# PX4FMUv2_4_6.net
KiCad netlist of a schematic drawn in EAGLE
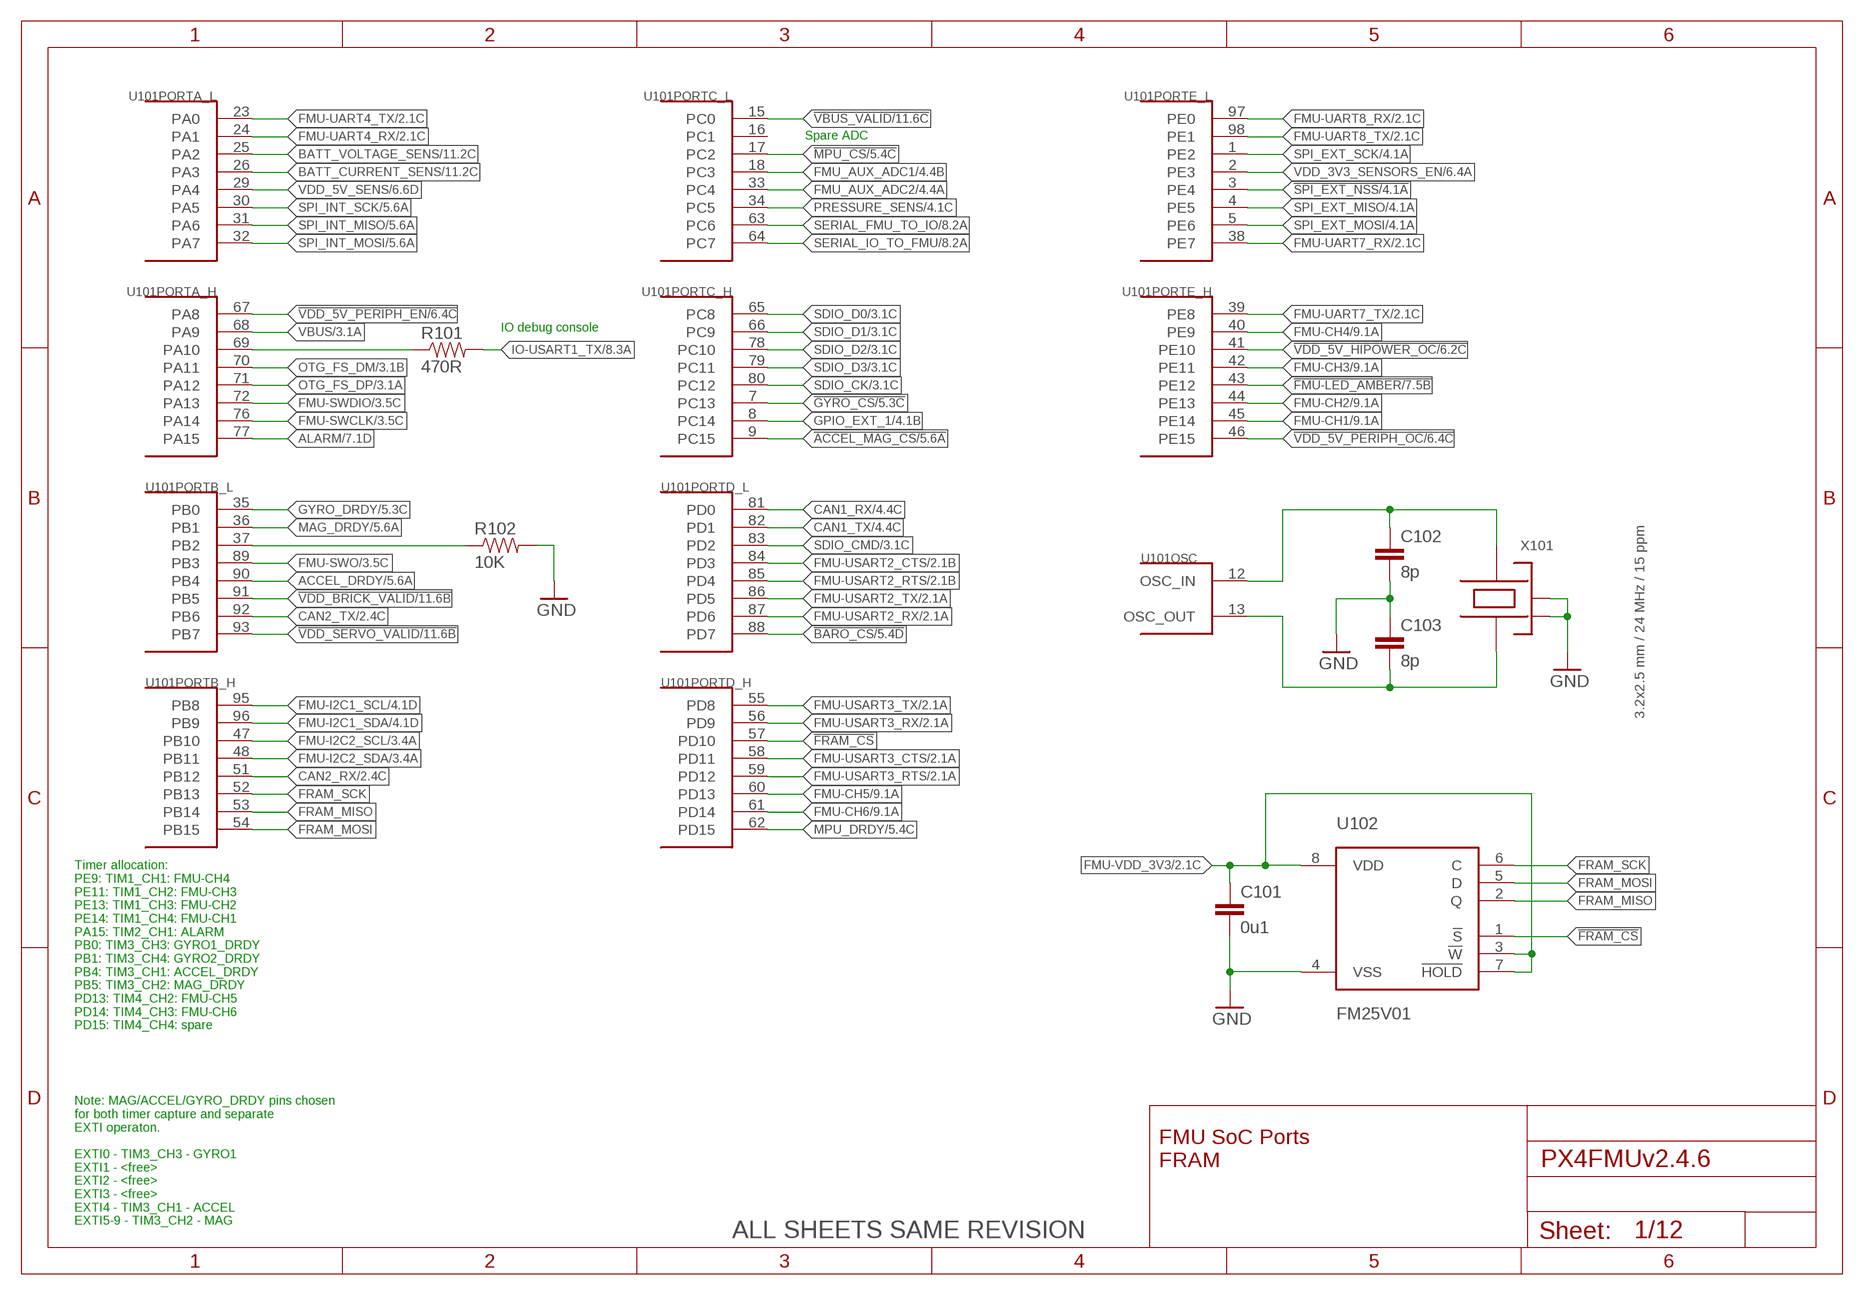
[diagram p0: schematic, sheet 1]
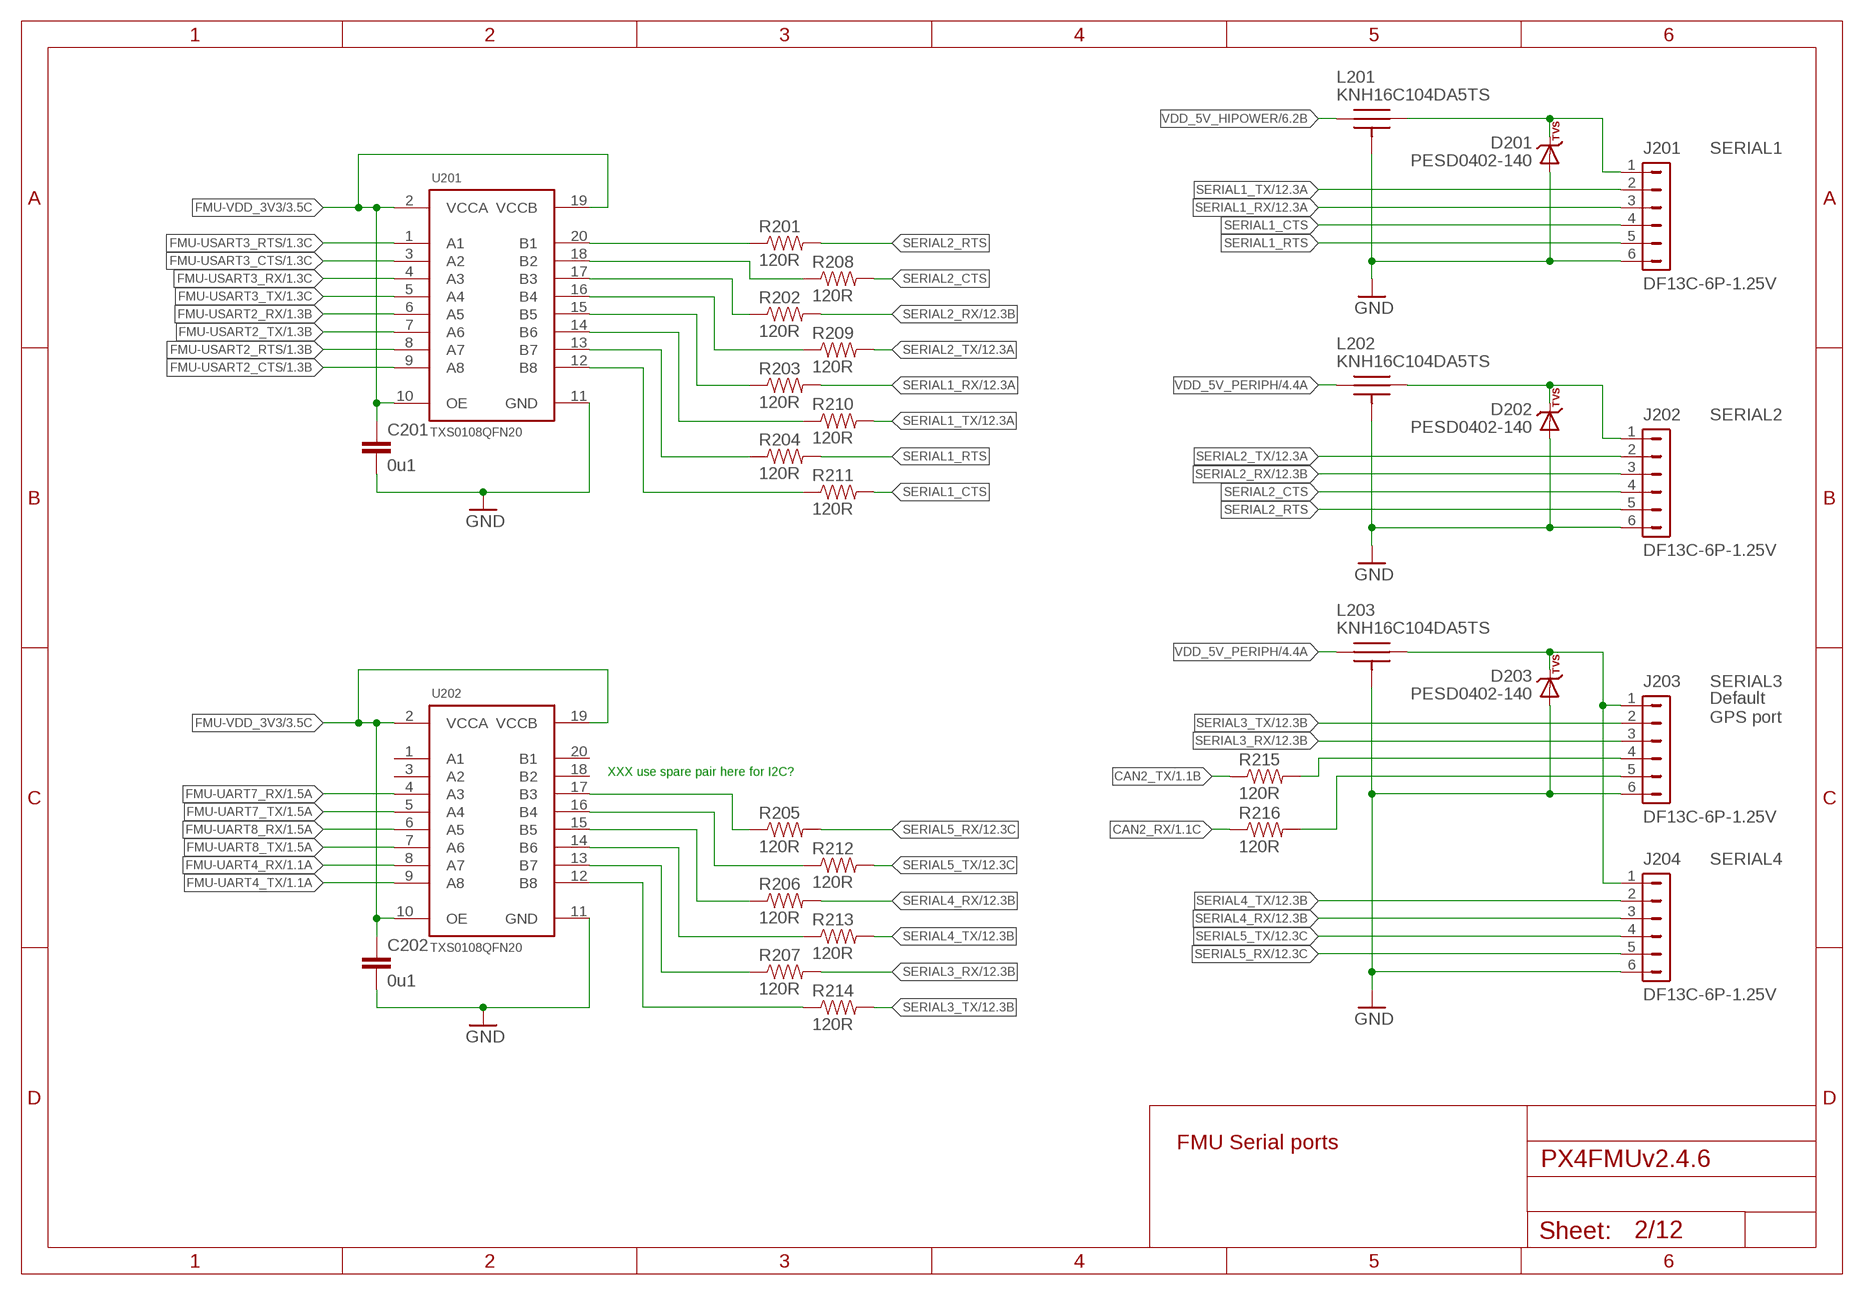
[diagram p1: schematic, sheet 2]
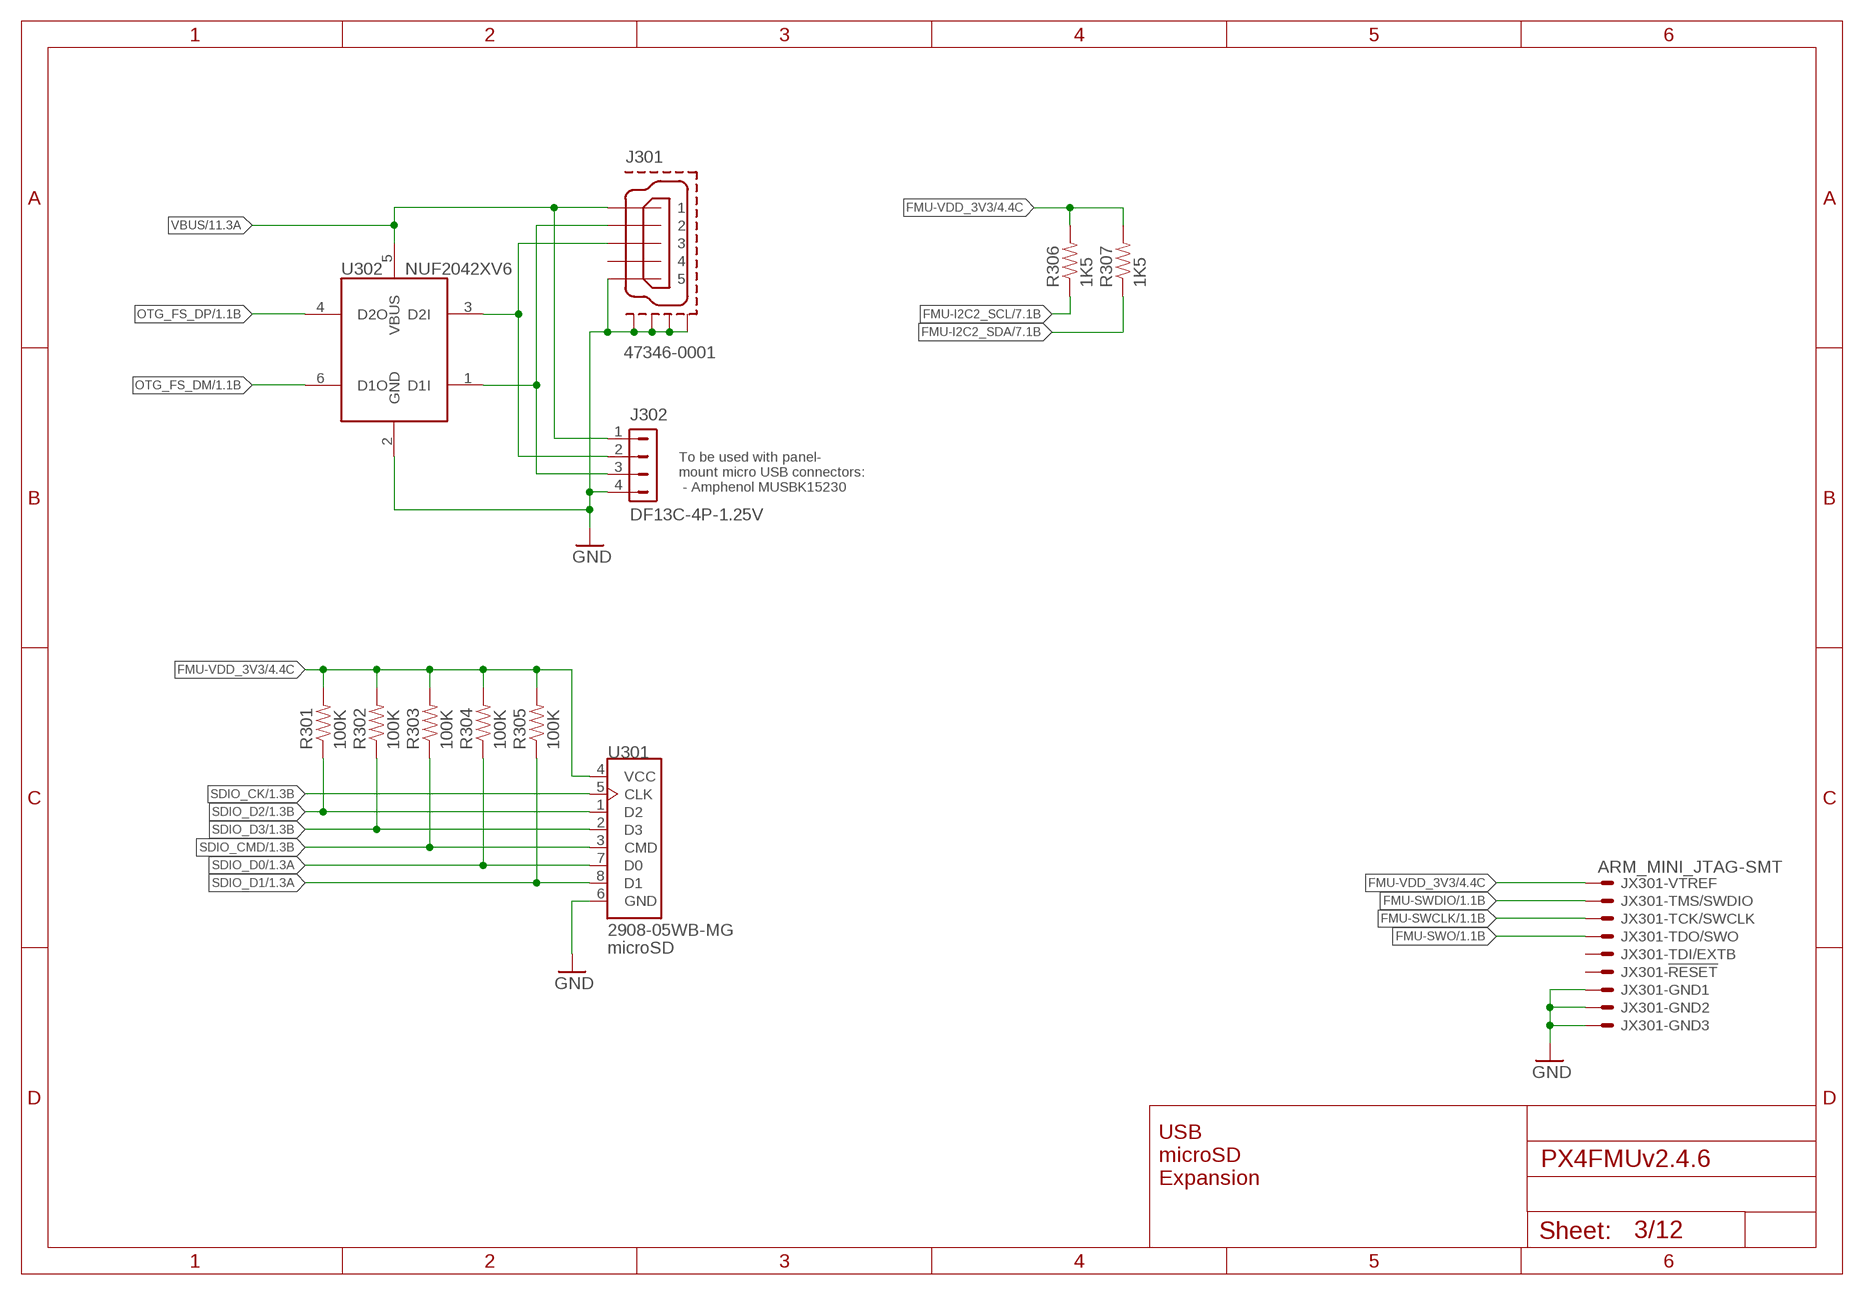
[diagram p2: schematic, sheet 3]
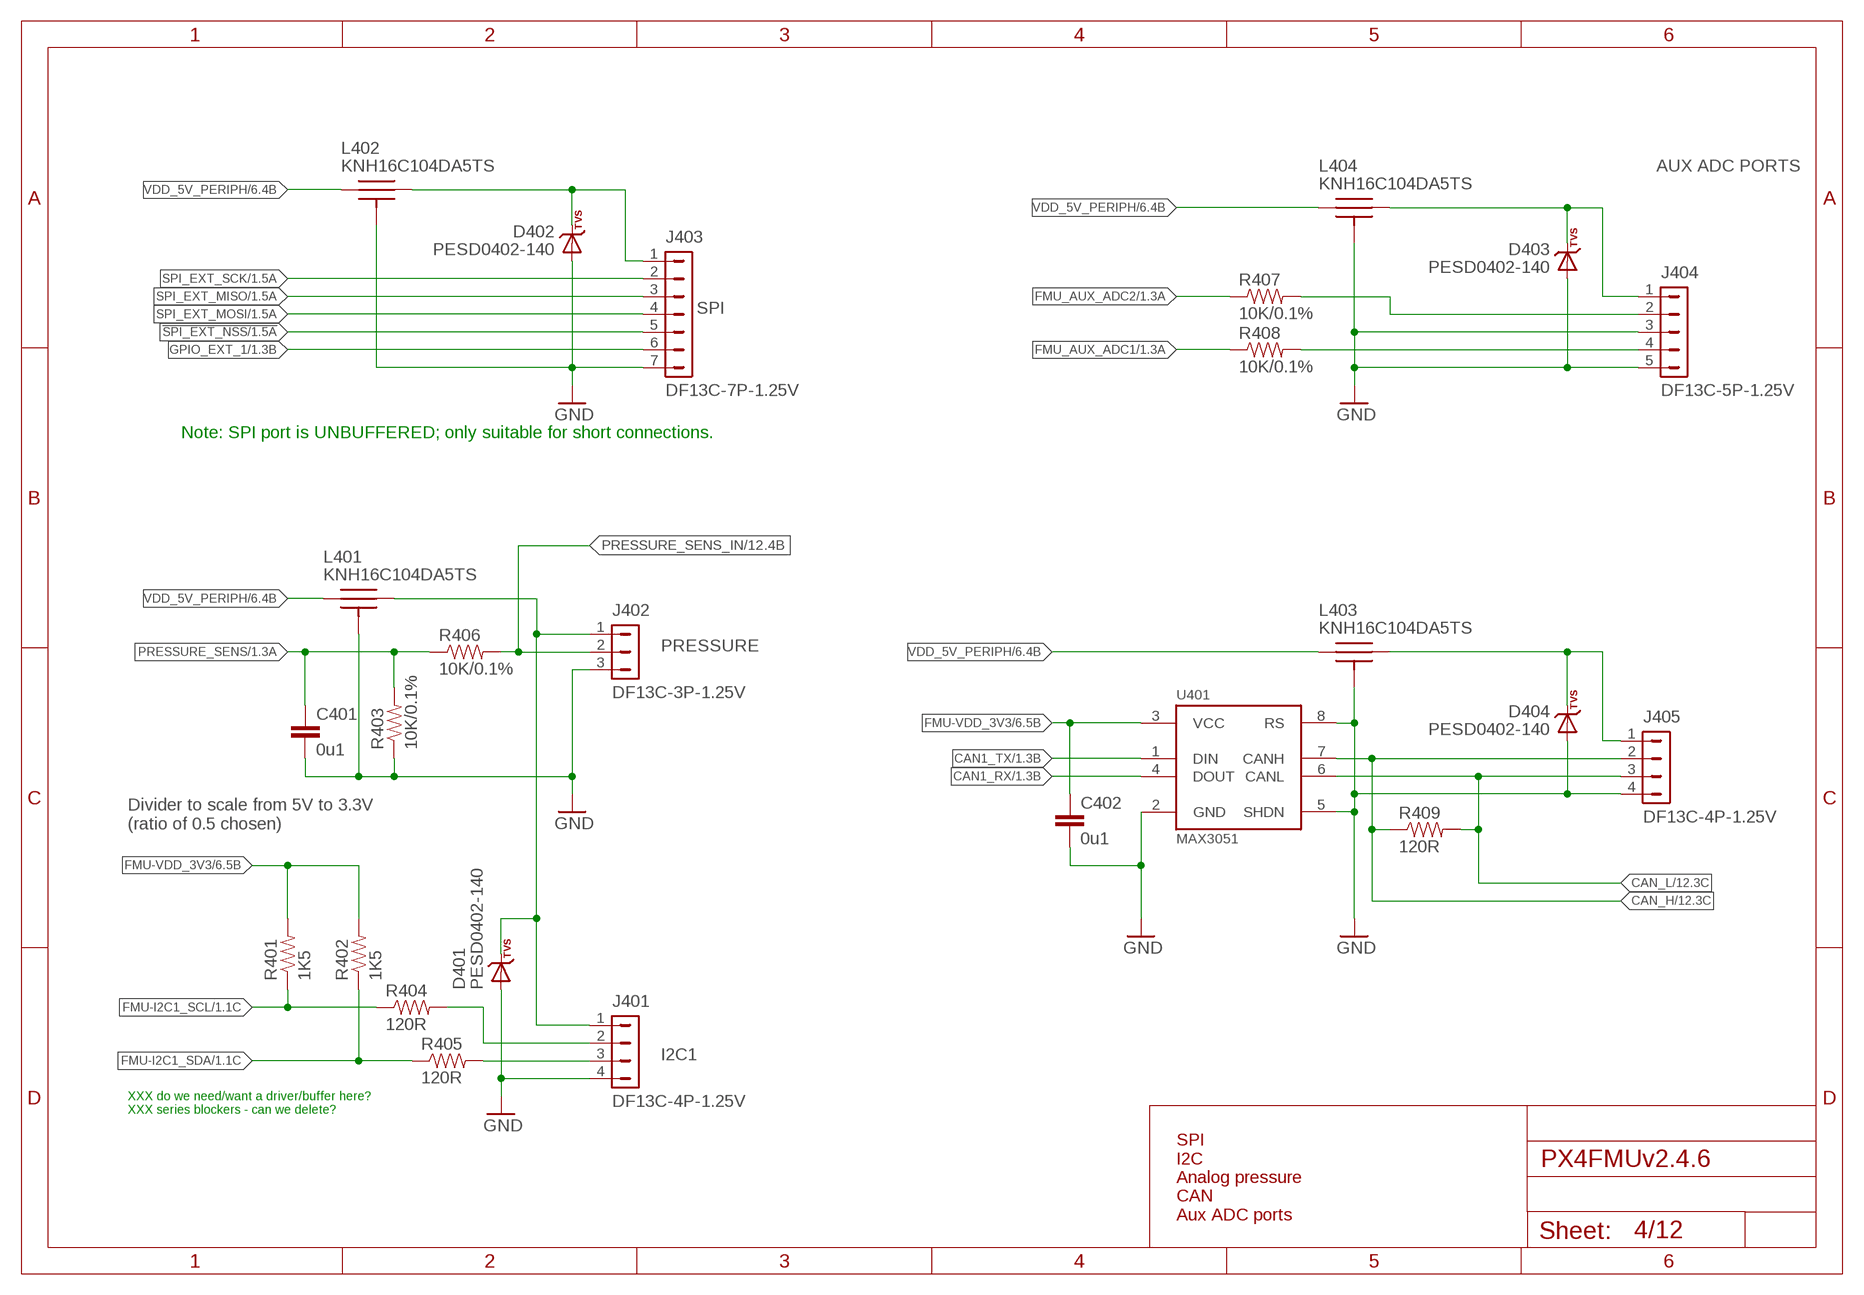
[diagram p3: schematic, sheet 4]
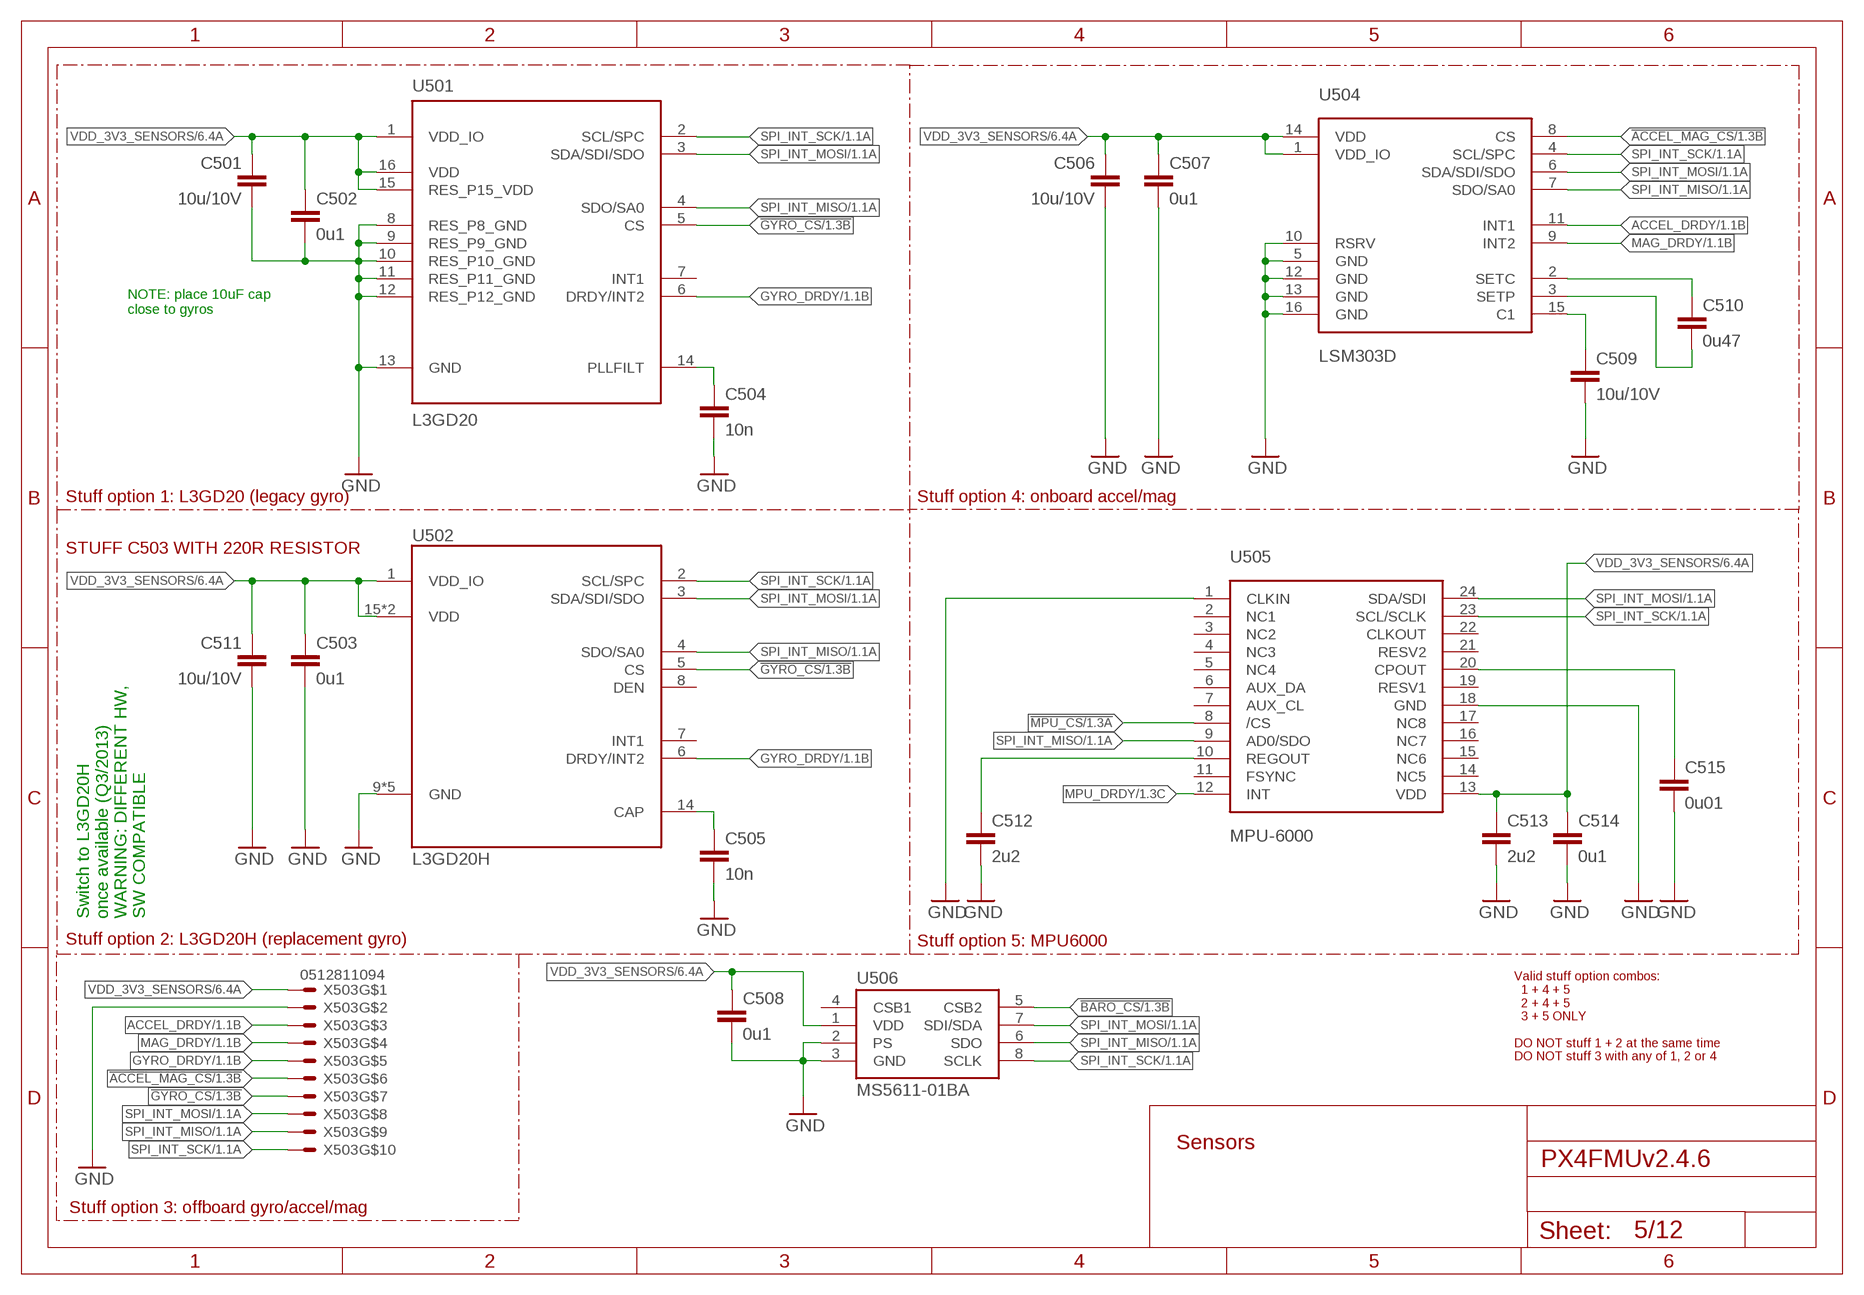
[diagram p4: schematic, sheet 5]
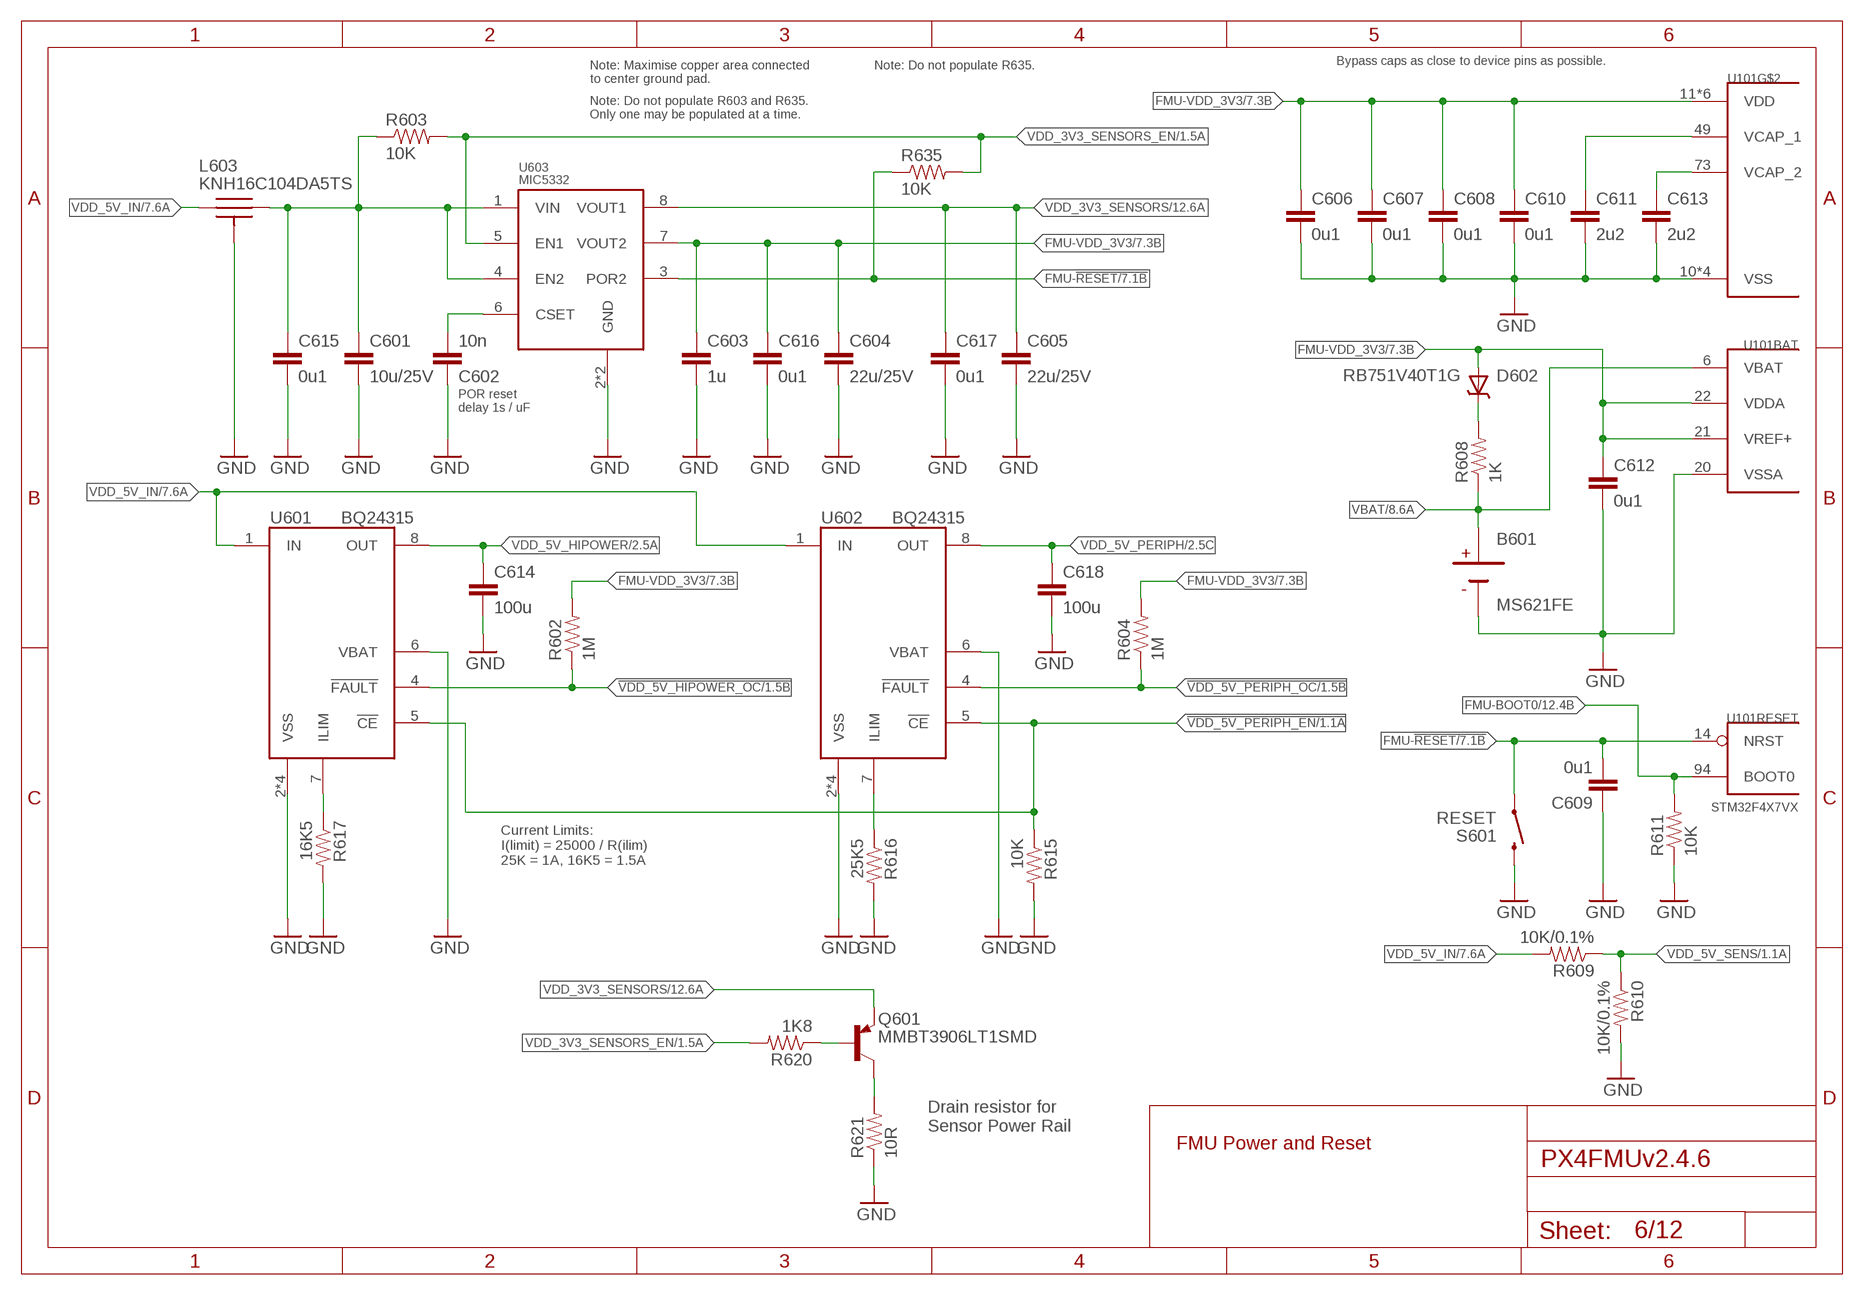
[diagram p5: schematic, sheet 6]
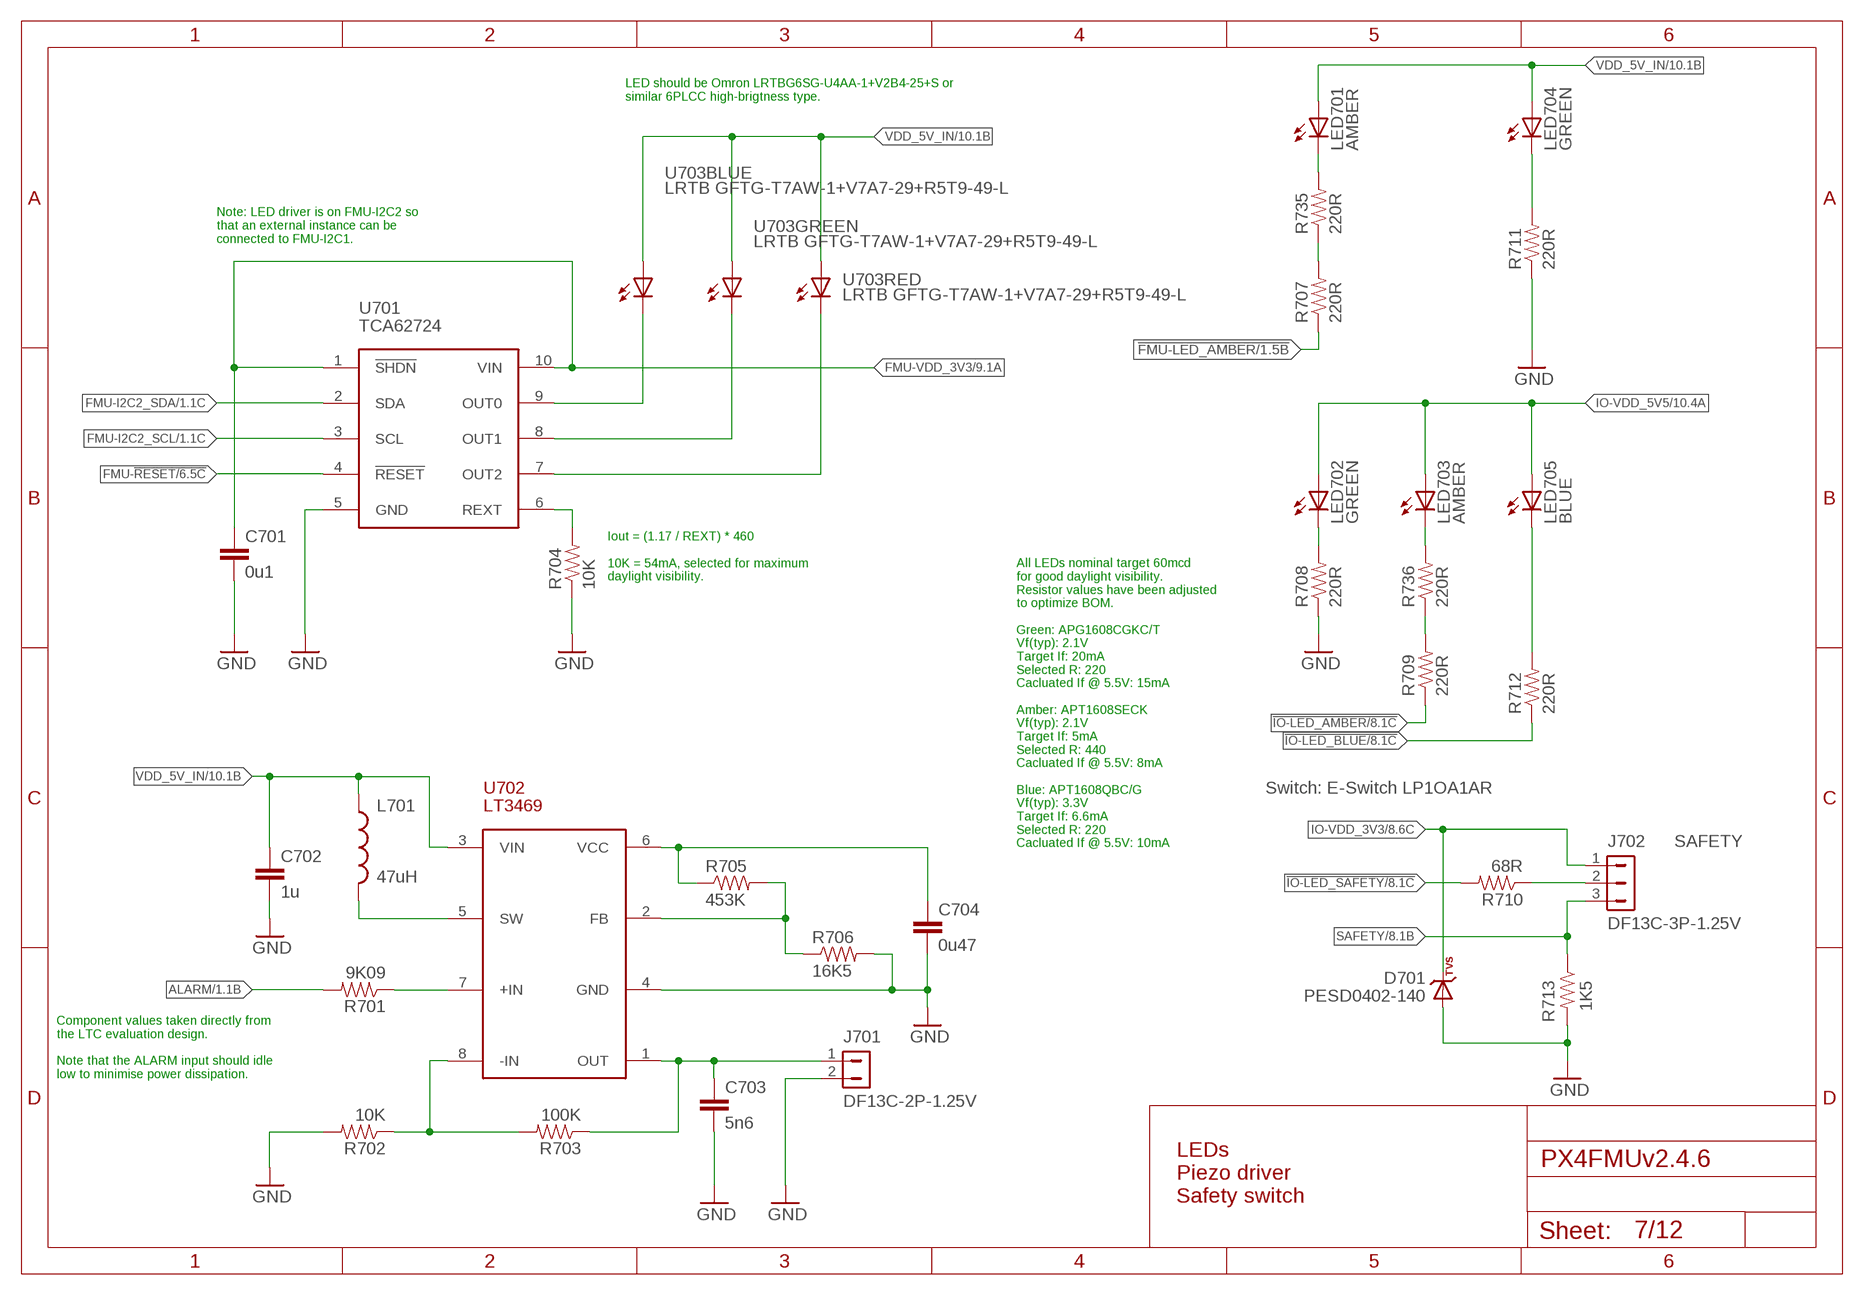
[diagram p6: schematic, sheet 7]
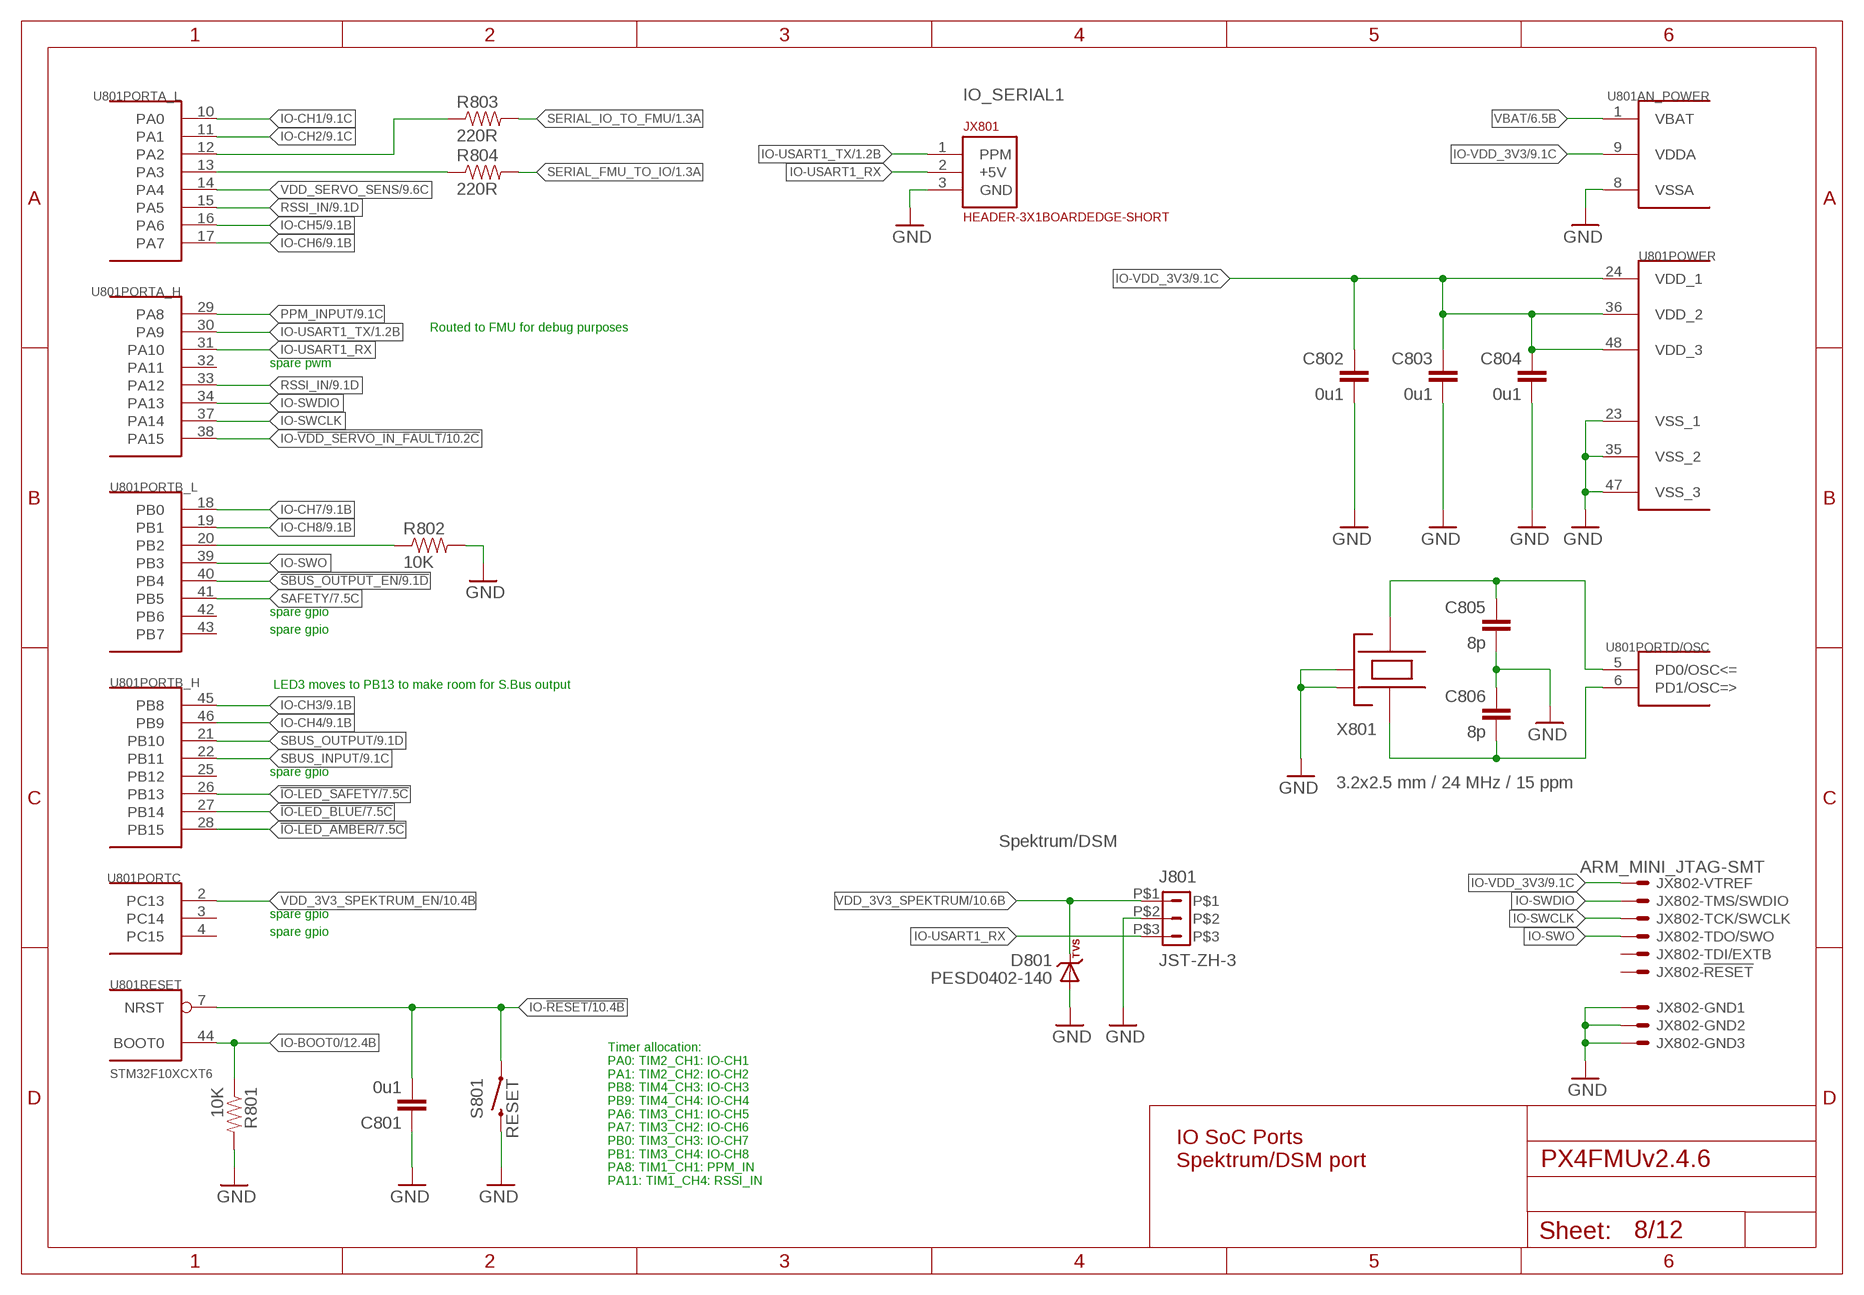
[diagram p7: schematic, sheet 8]
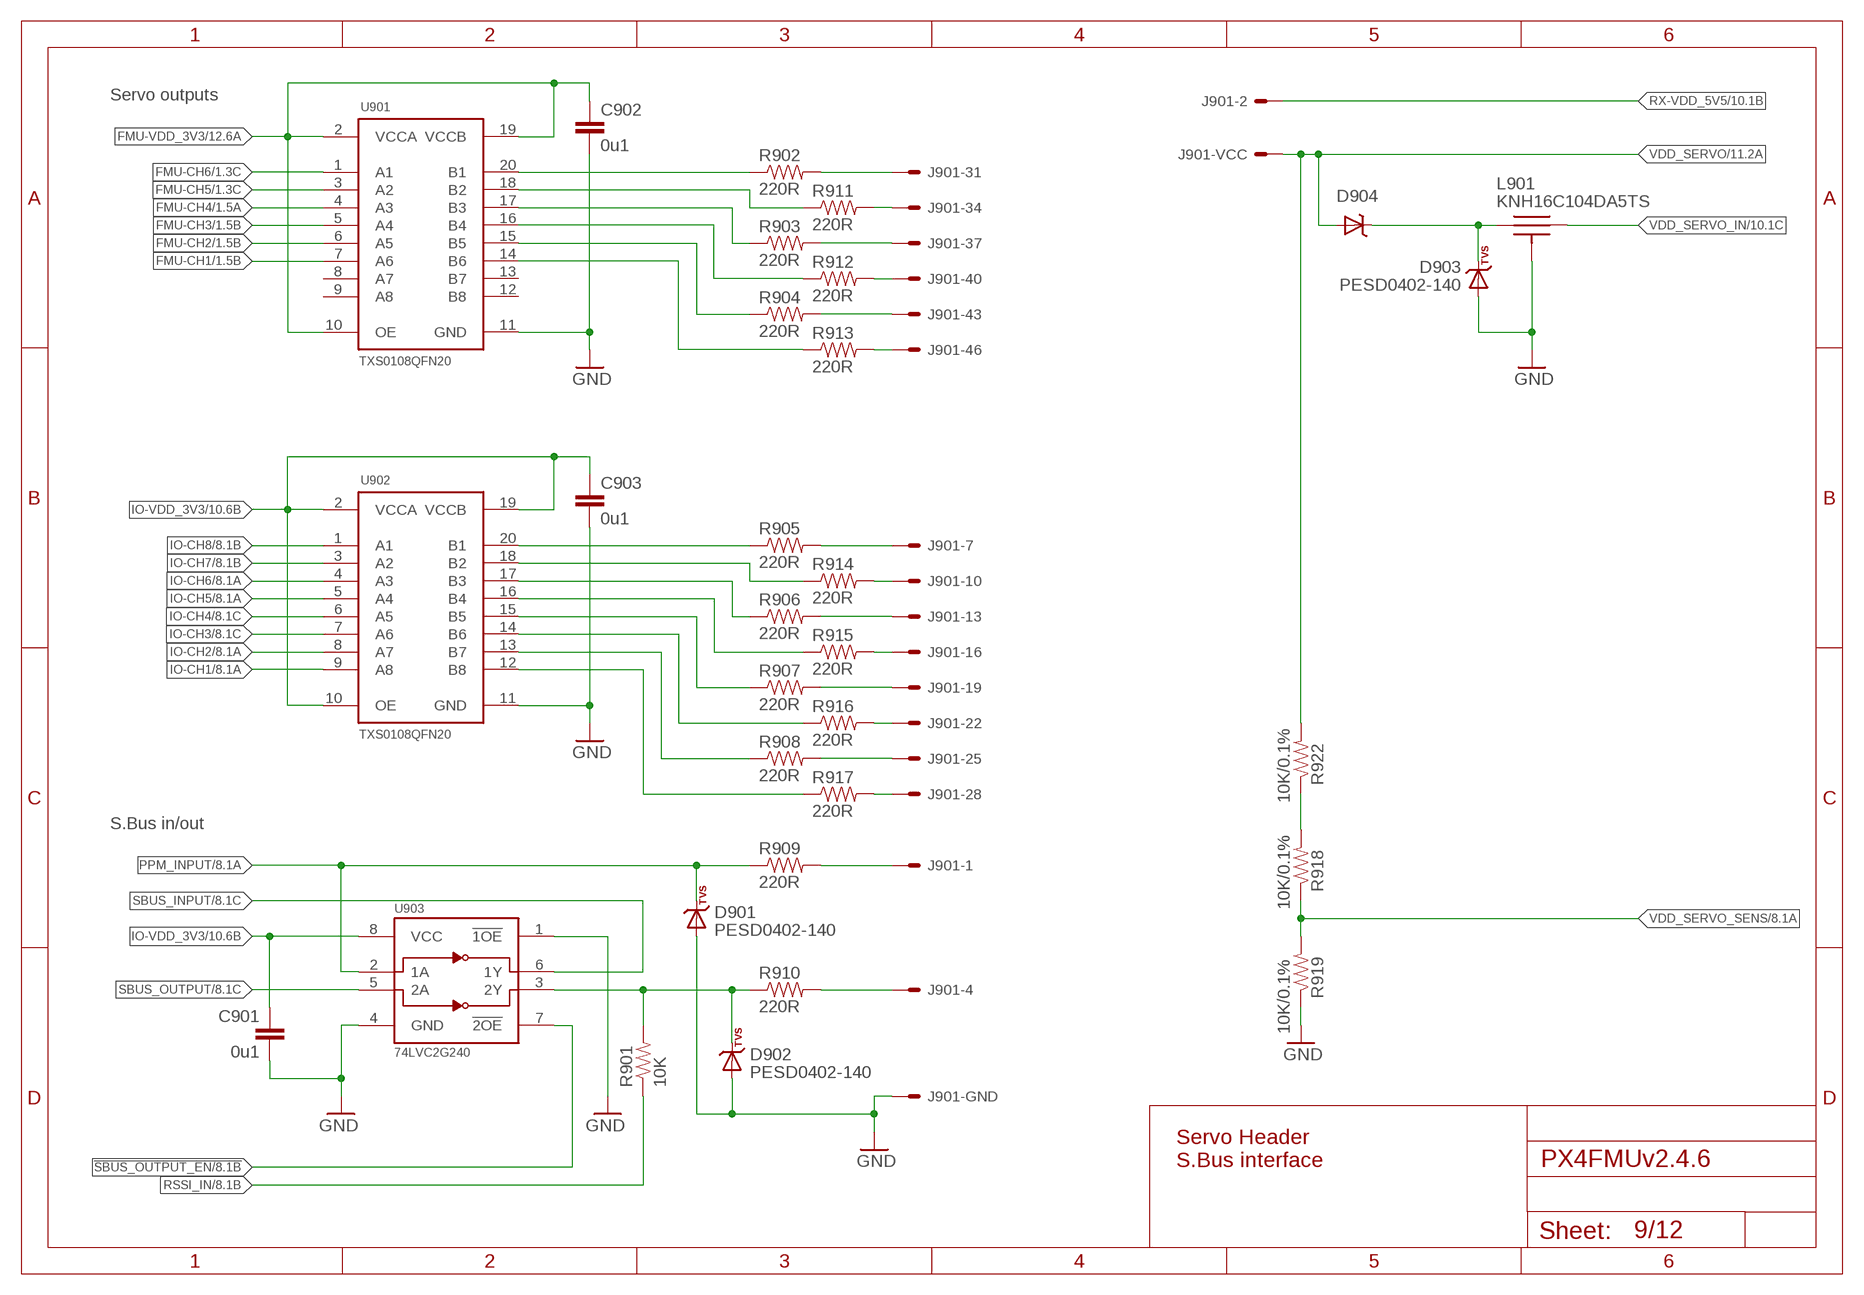
[diagram p8: schematic, sheet 9]
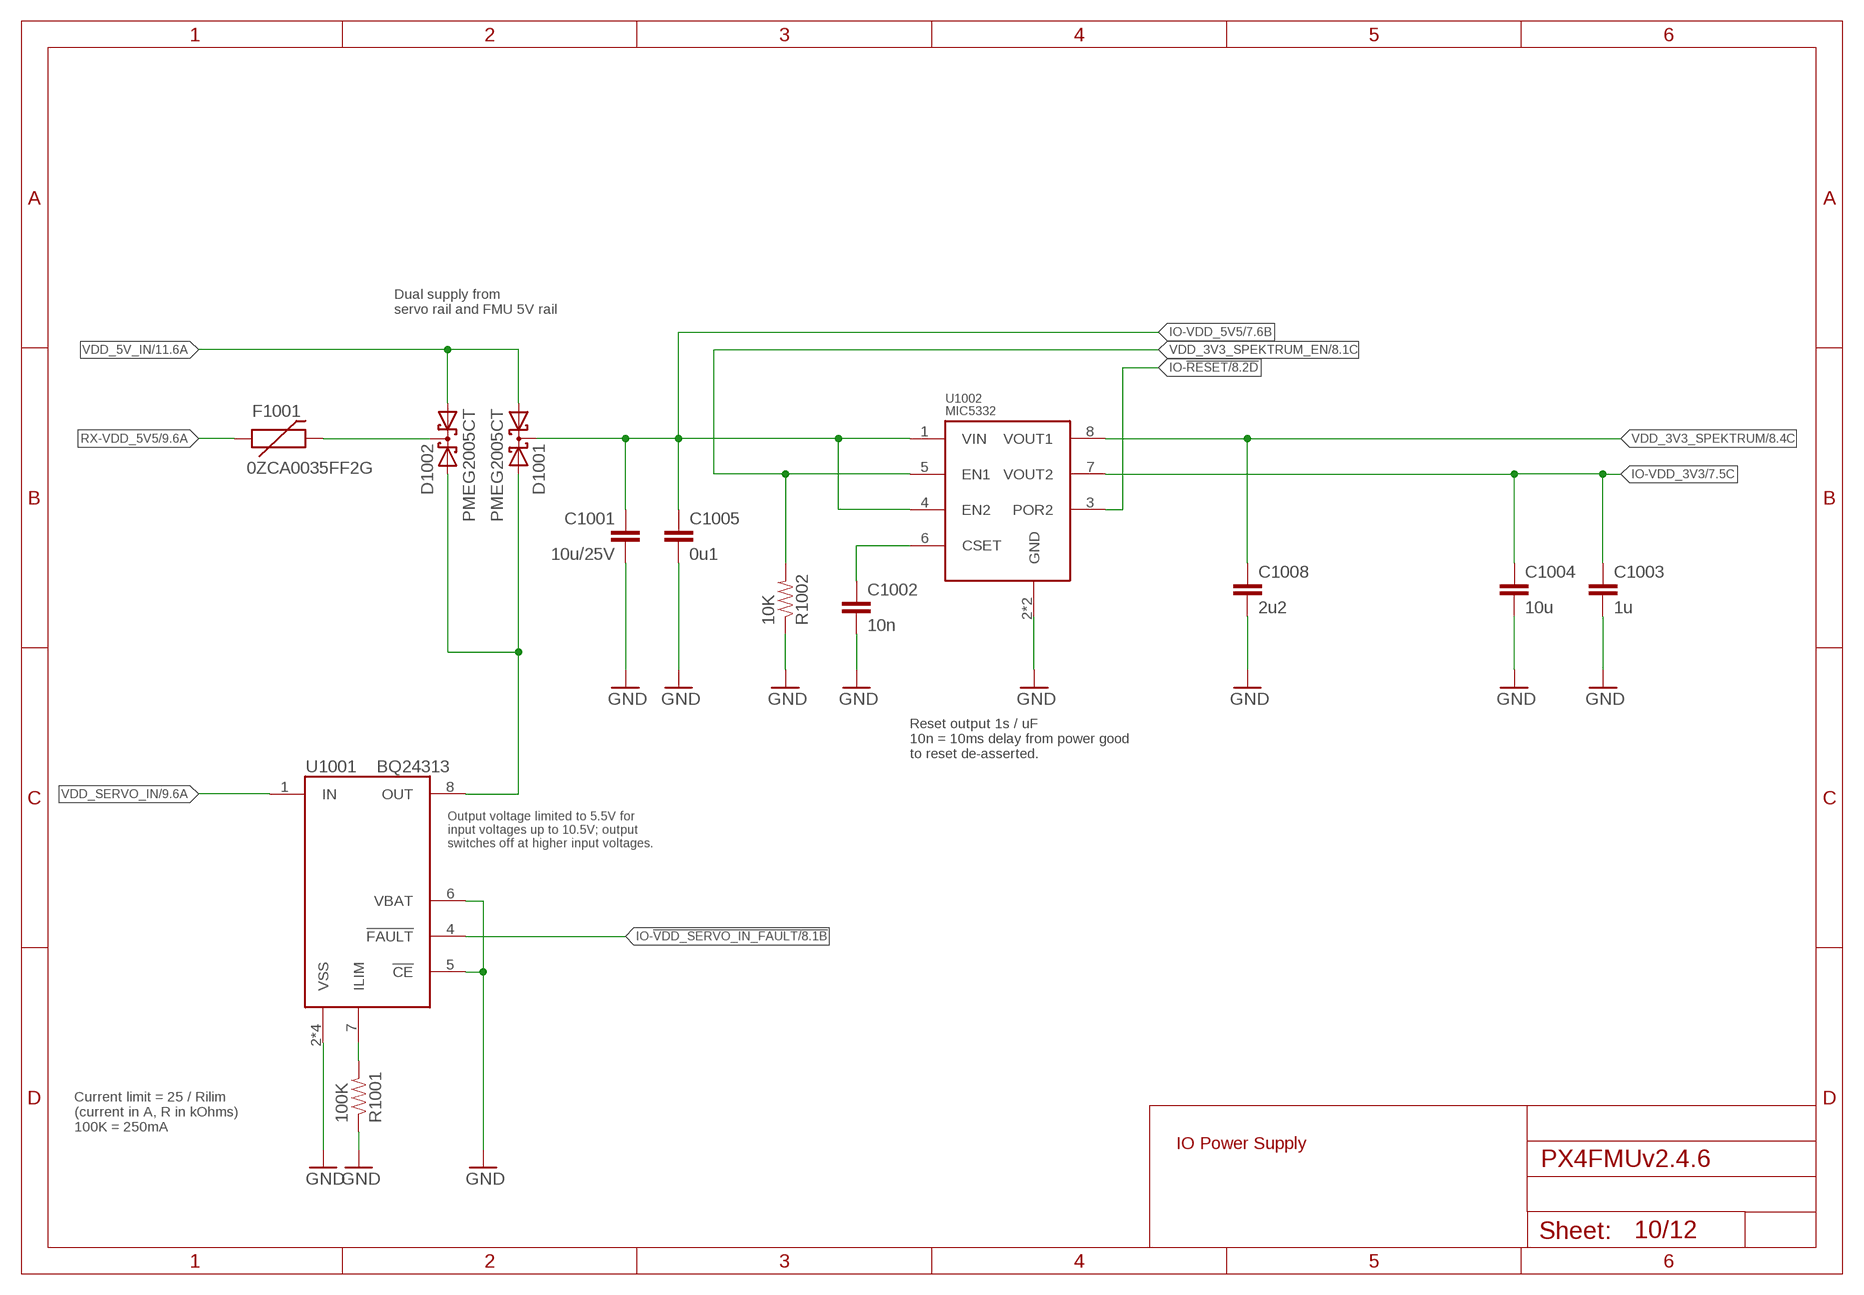
[diagram p9: schematic, sheet 10]
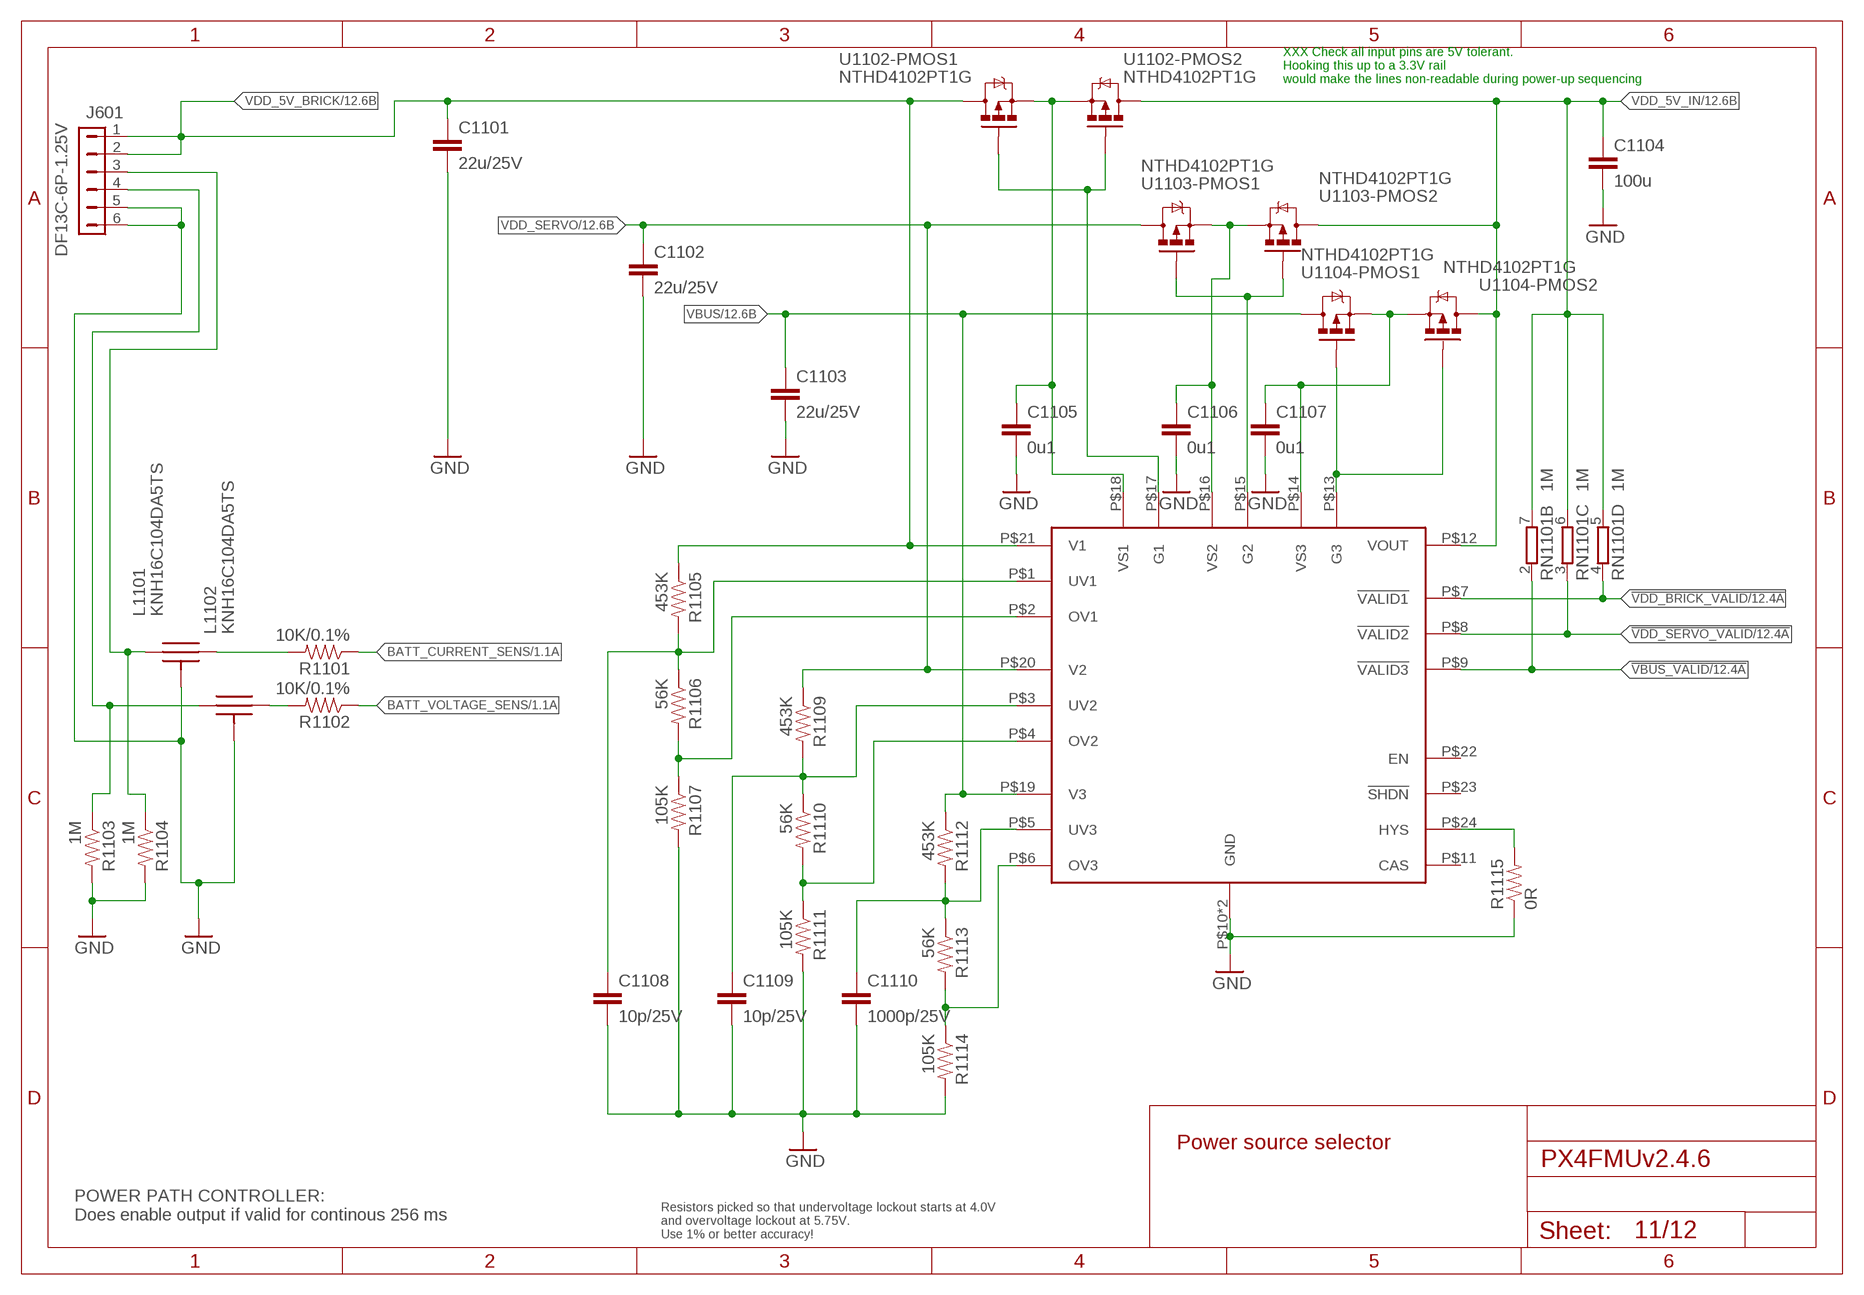
[diagram p10: schematic, sheet 11]
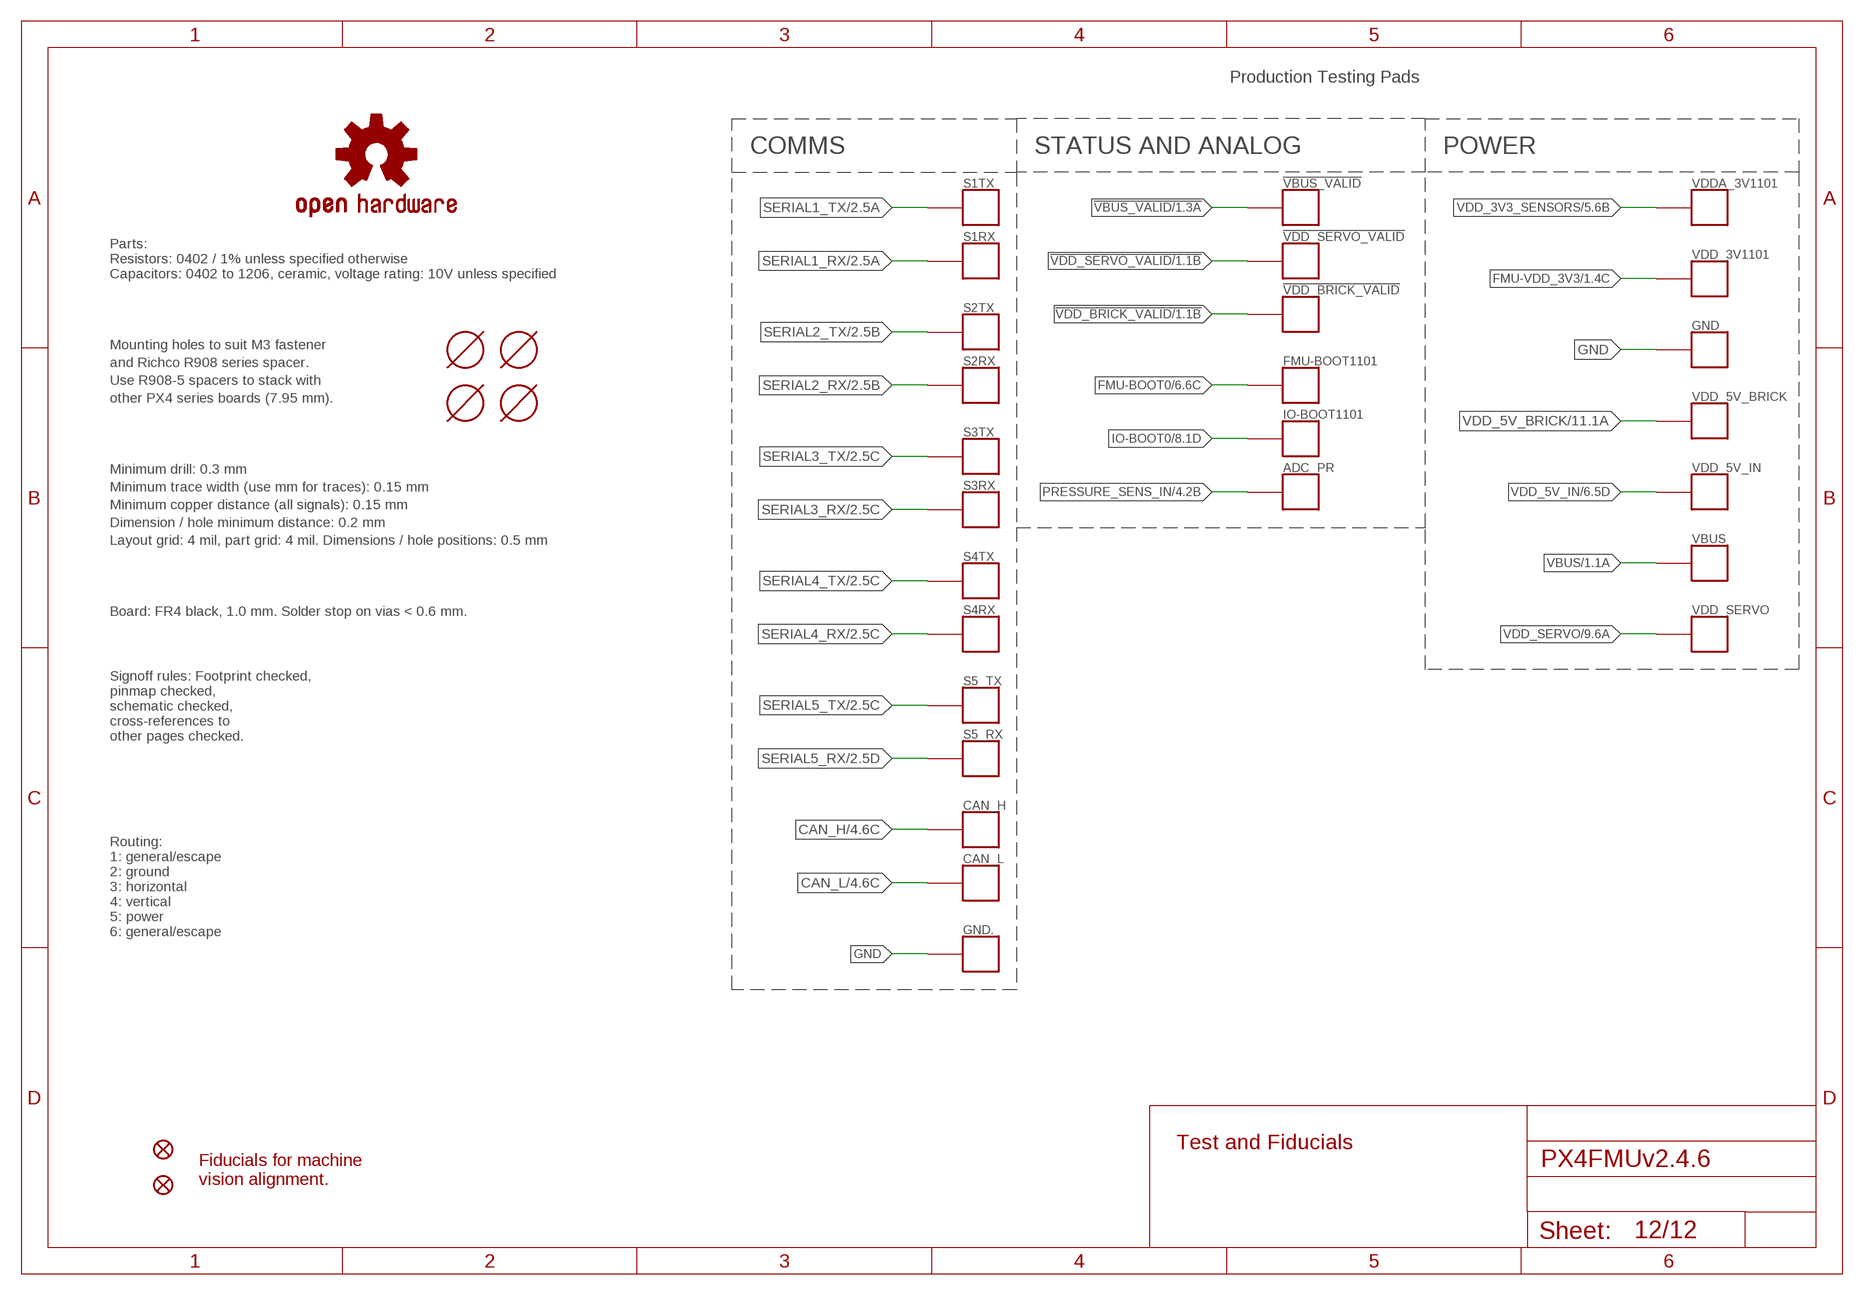
[diagram p11: schematic, sheet 12]

(export (version "E")
  (design (tool "Eeschema 10.0.6"))
  (components
    (comp (ref "B601")
      (value "MS621FE")
      (footprint "eagle-import:MS621FE")
      (fields (field (name "PARTNO") "MS621FE-FL11E"))
      (libsource (lib "eagle-import") (part "MS621FE"))
    )
    (comp (ref "C601")
      (value "10u/25V")
      (footprint "eagle-import:0805-CAP")
      (fields (field (name "PARTNO") "CL21A106KAYNNNE"))
      (libsource (lib "eagle-import") (part "CAP0805"))
    )
    (comp (ref "C602")
      (value "10n")
      (footprint "eagle-import:0402-CAP")
      (fields (field (name "PARTNO") "CC0402KRX7R7BB103"))
      (libsource (lib "eagle-import") (part "CAP0402"))
    )
    (comp (ref "C603")
      (value "1u")
      (footprint "eagle-import:0603-CAP")
      (fields (field (name "PARTNO") "CC0603ZRY5V7BB105"))
      (libsource (lib "eagle-import") (part "CAP0603"))
    )
    (comp (ref "C604")
      (value "22u/25V")
      (footprint "eagle-import:0805-CAP")
      (fields (field (name "PARTNO") "CL21A226MAQNNNE"))
      (libsource (lib "eagle-import") (part "CAP0805"))
    )
    (comp (ref "C605")
      (value "22u/25V")
      (footprint "eagle-import:0805-CAP")
      (fields (field (name "PARTNO") "CL21A226MAQNNNE"))
      (libsource (lib "eagle-import") (part "CAP0805"))
    )
    (comp (ref "C606")
      (value "0u1")
      (footprint "eagle-import:0402-CAP")
      (fields (field (name "PARTNO") "CC0402ZRY5V7BB104"))
      (libsource (lib "eagle-import") (part "CAP0402"))
    )
    (comp (ref "C607")
      (value "0u1")
      (footprint "eagle-import:0402-CAP")
      (fields (field (name "PARTNO") "CC0402ZRY5V7BB104"))
      (libsource (lib "eagle-import") (part "CAP0402"))
    )
    (comp (ref "C608")
      (value "0u1")
      (footprint "eagle-import:0402-CAP")
      (fields (field (name "PARTNO") "CC0402ZRY5V7BB104"))
      (libsource (lib "eagle-import") (part "CAP0402"))
    )
    (comp (ref "C609")
      (value "0u1")
      (footprint "eagle-import:0402-CAP")
      (fields (field (name "PARTNO") "CC0402ZRY5V7BB104"))
      (libsource (lib "eagle-import") (part "CAP0402"))
    )
    (comp (ref "C610")
      (value "0u1")
      (footprint "eagle-import:0402-CAP")
      (fields (field (name "PARTNO") "CC0402ZRY5V7BB104"))
      (libsource (lib "eagle-import") (part "CAP0402"))
    )
    (comp (ref "C611")
      (value "2u2")
      (footprint "eagle-import:0603-CAP")
      (fields (field (name "PARTNO") "C1608X6S1C225K080AC"))
      (libsource (lib "eagle-import") (part "CAP0603"))
    )
    (comp (ref "C612")
      (value "0u1")
      (footprint "eagle-import:0402-CAP")
      (fields (field (name "PARTNO") "CC0402ZRY5V7BB104"))
      (libsource (lib "eagle-import") (part "CAP0402"))
    )
    (comp (ref "C613")
      (value "2u2")
      (footprint "eagle-import:0603-CAP")
      (fields (field (name "PARTNO") "C1608X6S1C225K080AC"))
      (libsource (lib "eagle-import") (part "CAP0603"))
    )
    (comp (ref "C614")
      (value "100u")
      (footprint "eagle-import:1206-CAP")
      (fields (field (name "PARTNO") "C3216X5R1A107M160AC"))
      (libsource (lib "eagle-import") (part "CAP1206"))
    )
    (comp (ref "C615")
      (value "0u1")
      (footprint "eagle-import:0402-CAP")
      (fields (field (name "PARTNO") "CC0402ZRY5V7BB104"))
      (libsource (lib "eagle-import") (part "CAP0402"))
    )
    (comp (ref "C616")
      (value "0u1")
      (footprint "eagle-import:0402-CAP")
      (fields (field (name "PARTNO") "CC0402ZRY5V7BB104"))
      (libsource (lib "eagle-import") (part "CAP0402"))
    )
    (comp (ref "C617")
      (value "0u1")
      (footprint "eagle-import:0402-CAP")
      (fields (field (name "PARTNO") "CC0402ZRY5V7BB104"))
      (libsource (lib "eagle-import") (part "CAP0402"))
    )
    (comp (ref "C618")
      (value "100u")
      (footprint "eagle-import:1206-CAP")
      (fields (field (name "PARTNO") "C3216X5R1A107M160AC"))
      (libsource (lib "eagle-import") (part "CAP1206"))
    )
    (comp (ref "D602")
      (value "RB751V40T1G")
      (footprint "eagle-import:SOD323")
      (libsource (lib "eagle-import") (part "DIODE-SCHOTTKY_SOD323"))
    )
    (comp (ref "L603")
      (value "KNH16C104DA5TS")
      (footprint "eagle-import:KYOCERA-KNH16-DA")
      (libsource (lib "eagle-import") (part "KNH16C104DA5TS"))
    )
    (comp (ref "Q601")
      (value "MMBT3906LT1SMD")
      (footprint "eagle-import:SOT23-BEC")
      (fields (field (name "PARTNO") "MMBT 3906 LT1"))
      (libsource (lib "eagle-import") (part "MMBT3906SMDLT1"))
    )
    (comp (ref "R602")
      (value "1M")
      (footprint "eagle-import:0402-RES")
      (fields (field (name "PARTNO") "RC0402FR-071ML"))
      (libsource (lib "eagle-import") (part "RESISTOR0402-RES"))
    )
    (comp (ref "R603")
      (value "10K")
      (footprint "eagle-import:0402-RES")
      (fields (field (name "PARTNO") "RC0402FR-0710KL"))
      (libsource (lib "eagle-import") (part "RESISTOR0402-RES"))
    )
    (comp (ref "R604")
      (value "1M")
      (footprint "eagle-import:0402-RES")
      (fields (field (name "PARTNO") "RC0402FR-071ML"))
      (libsource (lib "eagle-import") (part "RESISTOR0402-RES"))
    )
    (comp (ref "R608")
      (value "1K")
      (footprint "eagle-import:0402-RES")
      (fields (field (name "PARTNO") "RC0402FR-071KL"))
      (libsource (lib "eagle-import") (part "RESISTOR0402-RES"))
    )
    (comp (ref "R609")
      (value "10K/0.1%")
      (footprint "eagle-import:0402-RES")
      (fields (field (name "PARTNO") "ERA-2AEB103X"))
      (libsource (lib "eagle-import") (part "RESISTOR0402-RES"))
    )
    (comp (ref "R610")
      (value "10K/0.1%")
      (footprint "eagle-import:0402-RES")
      (fields (field (name "PARTNO") "ERA-2AEB103X"))
      (libsource (lib "eagle-import") (part "RESISTOR0402-RES"))
    )
    (comp (ref "R611")
      (value "10K")
      (footprint "eagle-import:0402-RES")
      (fields (field (name "PARTNO") "RC0402FR-0710KL"))
      (libsource (lib "eagle-import") (part "RESISTOR0402-RES"))
    )
    (comp (ref "R615")
      (value "10K")
      (footprint "eagle-import:0402-RES")
      (fields (field (name "PARTNO") "RC0402FR-0710KL"))
      (libsource (lib "eagle-import") (part "RESISTOR0402-RES"))
    )
    (comp (ref "R616")
      (value "25K5")
      (footprint "eagle-import:0402-RES")
      (fields (field (name "PARTNO") "RMCF0402FT25K5"))
      (libsource (lib "eagle-import") (part "RESISTOR0402-RES"))
    )
    (comp (ref "R617")
      (value "16K5")
      (footprint "eagle-import:0402-RES")
      (fields (field (name "PARTNO") "RMCF0402FT16K5"))
      (libsource (lib "eagle-import") (part "RESISTOR0402-RES"))
    )
    (comp (ref "R620")
      (value "1K8")
      (footprint "eagle-import:0402-RES")
      (fields (field (name "PARTNO") "RC1005F182CS"))
      (libsource (lib "eagle-import") (part "RESISTOR0402-RES"))
    )
    (comp (ref "R621")
      (value "10R")
      (footprint "eagle-import:0603-RES")
      (fields (field (name "PARTNO") "RC1608J100CS"))
      (libsource (lib "eagle-import") (part "RESISTOR0603-RES"))
    )
    (comp (ref "R635")
      (value "10K")
      (footprint "eagle-import:0402-RES")
      (fields (field (name "PARTNO") "RC0402FR-0710KL"))
      (libsource (lib "eagle-import") (part "RESISTOR0402-RES"))
    )
    (comp (ref "S601")
      (value "RESET")
      (footprint "eagle-import:EVQP7J01K")
      (fields (field (name "PARTNO") "EVQ-P7J01P"))
      (libsource (lib "eagle-import") (part "SWITCH-MOMENTARY-2"))
    )
    (comp (ref "U101")
      (value "STM32F4X7VX")
      (footprint "eagle-import:TQFP100")
      (fields (field (name "PARTNO") "STM32F427VI"))
      (libsource (lib "eagle-import") (part "STM32F4X7VX"))
    )
    (comp (ref "U601")
      (value "BQ24315")
      (footprint "eagle-import:QFN8-DSG")
      (fields (field (name "PARTNO") "BQ24315DSGR"))
      (libsource (lib "eagle-import") (part "BQ24315"))
    )
    (comp (ref "U602")
      (value "BQ24315")
      (footprint "eagle-import:QFN8-DSG")
      (fields (field (name "PARTNO") "BQ24315DSGR"))
      (libsource (lib "eagle-import") (part "BQ24315"))
    )
    (comp (ref "U603")
      (value "MIC5332")
      (footprint "eagle-import:MLF-8-EPAD")
      (fields (field (name "PARTNO") "MIC5332-SSYMT"))
      (libsource (lib "eagle-import") (part "MIC5332"))
    )
    (comp (ref "J301")
      (value "47346-0001")
      (footprint "eagle-import:MOLEX-47346-0001")
      (libsource (lib "eagle-import") (part "MOLEX-47346-0001"))
    )
    (comp (ref "J302")
      (value "DF13C-4P-1.25V")
      (footprint "eagle-import:DF13C-4P-1.25V")
      (fields (field (name "PARTNO") "DF13C-4P-1.25V(20)"))
      (libsource (lib "eagle-import") (part "DF13-4P-1.25V"))
    )
    (comp (ref "JX301")
      (value "ARM_MINI_JTAG-SMT")
      (footprint "eagle-import:FTSH-105-01-XXX-DV-K")
      (fields (field (name "BOM") "EXCLUDE") (field (name "PARTNO") "M50-3900542"))
      (libsource (lib "eagle-import") (part "ARM_MINI_JTAG-SMT"))
    )
    (comp (ref "R301")
      (value "100K")
      (footprint "eagle-import:0402-RES")
      (fields (field (name "PARTNO") "RC0402FR-07100KL"))
      (libsource (lib "eagle-import") (part "RESISTOR0402-RES"))
    )
    (comp (ref "R302")
      (value "100K")
      (footprint "eagle-import:0402-RES")
      (fields (field (name "PARTNO") "RC0402FR-07100KL"))
      (libsource (lib "eagle-import") (part "RESISTOR0402-RES"))
    )
    (comp (ref "R303")
      (value "100K")
      (footprint "eagle-import:0402-RES")
      (fields (field (name "PARTNO") "RC0402FR-07100KL"))
      (libsource (lib "eagle-import") (part "RESISTOR0402-RES"))
    )
    (comp (ref "R304")
      (value "100K")
      (footprint "eagle-import:0402-RES")
      (fields (field (name "PARTNO") "RC0402FR-07100KL"))
      (libsource (lib "eagle-import") (part "RESISTOR0402-RES"))
    )
    (comp (ref "R305")
      (value "100K")
      (footprint "eagle-import:0402-RES")
      (fields (field (name "PARTNO") "RC0402FR-07100KL"))
      (libsource (lib "eagle-import") (part "RESISTOR0402-RES"))
    )
    (comp (ref "R306")
      (value "1K5")
      (footprint "eagle-import:0402-RES")
      (fields (field (name "PARTNO") "RC0402FR-071K5L"))
      (libsource (lib "eagle-import") (part "RESISTOR0402-RES"))
    )
    (comp (ref "R307")
      (value "1K5")
      (footprint "eagle-import:0402-RES")
      (fields (field (name "PARTNO") "RC0402FR-071K5L"))
      (libsource (lib "eagle-import") (part "RESISTOR0402-RES"))
    )
    (comp (ref "U301")
      (value "2908-05WB-MG")
      (footprint "eagle-import:MICROSD")
      (libsource (lib "eagle-import") (part "MICROSDSDI"))
    )
    (comp (ref "U302")
      (value "NUF2042XV6")
      (footprint "eagle-import:SOT563-6")
      (fields (field (name "PARTNO") "NUF2042XV6T1G"))
      (libsource (lib "eagle-import") (part "NUF2042XV6"))
    )
    (comp (ref "!VBUS_VALID")
      (value "PAD.04")
      (footprint "eagle-import:PAD.04X.04")
      (libsource (lib "eagle-import") (part "PAD.04"))
    )
    (comp (ref "!VDD_BRICK_VALID")
      (value "PAD.04")
      (footprint "eagle-import:PAD.04X.04")
      (libsource (lib "eagle-import") (part "PAD.04"))
    )
    (comp (ref "!VDD_SERVO_VALID")
      (value "PAD.04")
      (footprint "eagle-import:PAD.04X.04")
      (libsource (lib "eagle-import") (part "PAD.04"))
    )
    (comp (ref "ADC_PR")
      (value "PAD.04")
      (footprint "eagle-import:PAD.04X.04")
      (libsource (lib "eagle-import") (part "PAD.04"))
    )
    (comp (ref "CAN_H")
      (value "PAD.04")
      (footprint "eagle-import:PAD.04X.04")
      (libsource (lib "eagle-import") (part "PAD.04"))
    )
    (comp (ref "CAN_L")
      (value "PAD.04")
      (footprint "eagle-import:PAD.04X.04")
      (libsource (lib "eagle-import") (part "PAD.04"))
    )
    (comp (ref "FMU-BOOT1101")
      (value "PAD.04")
      (footprint "eagle-import:PAD.04X.04")
      (libsource (lib "eagle-import") (part "PAD.04"))
    )
    (comp (ref "GND")
      (value "PAD.04")
      (footprint "eagle-import:PAD.04X.04")
      (libsource (lib "eagle-import") (part "PAD.04"))
    )
    (comp (ref "GND.")
      (value "PAD.04")
      (footprint "eagle-import:PAD.04X.04")
      (libsource (lib "eagle-import") (part "PAD.04"))
    )
    (comp (ref "IO-BOOT1101")
      (value "PAD.04")
      (footprint "eagle-import:PAD.04X.04")
      (libsource (lib "eagle-import") (part "PAD.04"))
    )
    (comp (ref "JP1")
      (value "FIDUCIAL1.5X3")
      (footprint "eagle-import:FIDUCIAL-1.5X3")
      (libsource (lib "eagle-import") (part "FIDUCIAL1.5X3"))
    )
    (comp (ref "JP2")
      (value "FIDUCIAL1.5X3")
      (footprint "eagle-import:FIDUCIAL-1.5X3")
      (libsource (lib "eagle-import") (part "FIDUCIAL1.5X3"))
    )
    (comp (ref "M3_MOUNT1101")
      (value "MOUNT-HOLE3.1MM")
      (footprint "eagle-import:MOUNT-HOLE3.1")
      (libsource (lib "eagle-import") (part "MOUNT-HOLE3.1MM"))
    )
    (comp (ref "M3_MOUNT1102")
      (value "MOUNT-HOLE3.1MM")
      (footprint "eagle-import:MOUNT-HOLE3.1")
      (libsource (lib "eagle-import") (part "MOUNT-HOLE3.1MM"))
    )
    (comp (ref "M3_MOUNT1103")
      (value "MOUNT-HOLE3.1MM")
      (footprint "eagle-import:MOUNT-HOLE3.1")
      (libsource (lib "eagle-import") (part "MOUNT-HOLE3.1MM"))
    )
    (comp (ref "M3_MOUNT1104")
      (value "MOUNT-HOLE3.1MM")
      (footprint "eagle-import:MOUNT-HOLE3.1")
      (libsource (lib "eagle-import") (part "MOUNT-HOLE3.1MM"))
    )
    (comp (ref "OSHW_LOGO")
      (value "OSHW-LOGOS")
      (footprint "eagle-import:OSHW-LOGO-S")
      (libsource (lib "eagle-import") (part "OSHW-LOGOS"))
    )
    (comp (ref "S1RX")
      (value "PAD.04")
      (footprint "eagle-import:PAD.04X.04")
      (libsource (lib "eagle-import") (part "PAD.04"))
    )
    (comp (ref "S1TX")
      (value "PAD.04")
      (footprint "eagle-import:PAD.04X.04")
      (libsource (lib "eagle-import") (part "PAD.04"))
    )
    (comp (ref "S2RX")
      (value "PAD.04")
      (footprint "eagle-import:PAD.04X.04")
      (libsource (lib "eagle-import") (part "PAD.04"))
    )
    (comp (ref "S2TX")
      (value "PAD.04")
      (footprint "eagle-import:PAD.04X.04")
      (libsource (lib "eagle-import") (part "PAD.04"))
    )
    (comp (ref "S3RX")
      (value "PAD.04")
      (footprint "eagle-import:PAD.04X.04")
      (libsource (lib "eagle-import") (part "PAD.04"))
    )
    (comp (ref "S3TX")
      (value "PAD.04")
      (footprint "eagle-import:PAD.04X.04")
      (libsource (lib "eagle-import") (part "PAD.04"))
    )
    (comp (ref "S4RX")
      (value "PAD.04")
      (footprint "eagle-import:PAD.04X.04")
      (libsource (lib "eagle-import") (part "PAD.04"))
    )
    (comp (ref "S4TX")
      (value "PAD.04")
      (footprint "eagle-import:PAD.04X.04")
      (libsource (lib "eagle-import") (part "PAD.04"))
    )
    (comp (ref "S5_RX")
      (value "PAD.04")
      (footprint "eagle-import:PAD.04X.04")
      (libsource (lib "eagle-import") (part "PAD.04"))
    )
    (comp (ref "S5_TX")
      (value "PAD.04")
      (footprint "eagle-import:PAD.04X.04")
      (libsource (lib "eagle-import") (part "PAD.04"))
    )
    (comp (ref "VBUS")
      (value "PAD.04")
      (footprint "eagle-import:PAD.04X.04")
      (libsource (lib "eagle-import") (part "PAD.04"))
    )
    (comp (ref "VDDA_3V1101")
      (value "PAD.04")
      (footprint "eagle-import:PAD.04X.04")
      (libsource (lib "eagle-import") (part "PAD.04"))
    )
    (comp (ref "VDD_3V1101")
      (value "PAD.04")
      (footprint "eagle-import:PAD.04X.04")
      (libsource (lib "eagle-import") (part "PAD.04"))
    )
    (comp (ref "VDD_5V_BRICK")
      (value "PAD.04")
      (footprint "eagle-import:PAD.04X.04")
      (libsource (lib "eagle-import") (part "PAD.04"))
    )
    (comp (ref "VDD_5V_IN")
      (value "PAD.04")
      (footprint "eagle-import:PAD.04X.04")
      (libsource (lib "eagle-import") (part "PAD.04"))
    )
    (comp (ref "VDD_SERVO")
      (value "PAD.04")
      (footprint "eagle-import:PAD.04X.04")
      (libsource (lib "eagle-import") (part "PAD.04"))
    )
    (comp (ref "C101")
      (value "0u1")
      (footprint "eagle-import:0402-CAP")
      (fields (field (name "PARTNO") "CC0402ZRY5V7BB104"))
      (libsource (lib "eagle-import") (part "CAP0402"))
    )
    (comp (ref "C102")
      (value "8p")
      (footprint "eagle-import:0402-CAP")
      (fields (field (name "PARTNO") "C1005C0G1H080C"))
      (libsource (lib "eagle-import") (part "CAP0402"))
    )
    (comp (ref "C103")
      (value "8p")
      (footprint "eagle-import:0402-CAP")
      (fields (field (name "PARTNO") "C1005C0G1H080C"))
      (libsource (lib "eagle-import") (part "CAP0402"))
    )
    (comp (ref "R101")
      (value "470R")
      (footprint "eagle-import:0402-RES")
      (fields (field (name "PARTNO") "RC0402FR-07470RL"))
      (libsource (lib "eagle-import") (part "RESISTOR0402-RES"))
    )
    (comp (ref "R102")
      (value "10K")
      (footprint "eagle-import:0402-RES")
      (fields (field (name "PARTNO") "RC0402FR-0710KL"))
      (libsource (lib "eagle-import") (part "RESISTOR0402-RES"))
    )
    (comp (ref "U102")
      (value "FM25V01")
      (footprint "eagle-import:SO08")
      (fields (field (name "PARTNO") "FM25V01-G"))
      (libsource (lib "eagle-import") (part "FM25V01"))
    )
    (comp (ref "X101")
      (value "3.2x2.5 mm / 24 MHz / 15 ppm")
      (footprint "eagle-import:OSCILLATOR-3.2X2.5")
      (fields (field (name "PARTNO") "NX3225SA-24.000000MHZ"))
      (libsource (lib "eagle-import") (part "OSCILLATOR-3.2X2.5"))
    )
    (comp (ref "C1101")
      (value "22u/25V")
      (footprint "eagle-import:0805-CAP")
      (fields (field (name "PARTNO") "CL21A226MAQNNNE"))
      (libsource (lib "eagle-import") (part "CAP0805"))
    )
    (comp (ref "C1102")
      (value "22u/25V")
      (footprint "eagle-import:0805-CAP")
      (fields (field (name "PARTNO") "CL21A226MAQNNNE"))
      (libsource (lib "eagle-import") (part "CAP0805"))
    )
    (comp (ref "C1103")
      (value "22u/25V")
      (footprint "eagle-import:0805-CAP")
      (fields (field (name "PARTNO") "CL21A226MAQNNNE"))
      (libsource (lib "eagle-import") (part "CAP0805"))
    )
    (comp (ref "C1104")
      (value "100u")
      (footprint "eagle-import:1206-CAP")
      (fields (field (name "PARTNO") "C3216X5R1A107M160AC"))
      (libsource (lib "eagle-import") (part "CAP1206"))
    )
    (comp (ref "C1105")
      (value "0u1")
      (footprint "eagle-import:0402-CAP")
      (fields (field (name "PARTNO") "C1005X7R1E104K050BB"))
      (libsource (lib "eagle-import") (part "CAP0402"))
    )
    (comp (ref "C1106")
      (value "0u1")
      (footprint "eagle-import:0402-CAP")
      (fields (field (name "PARTNO") "C1005X7R1E104K050BB"))
      (libsource (lib "eagle-import") (part "CAP0402"))
    )
    (comp (ref "C1107")
      (value "0u1")
      (footprint "eagle-import:0402-CAP")
      (fields (field (name "PARTNO") "C1005X7R1E104K050BB"))
      (libsource (lib "eagle-import") (part "CAP0402"))
    )
    (comp (ref "C1108")
      (value "10p/25V")
      (footprint "eagle-import:0402-CAP")
      (fields (field (name "PARTNO") "C0402C100J3GACTU"))
      (libsource (lib "eagle-import") (part "CAP0402"))
    )
    (comp (ref "C1109")
      (value "10p/25V")
      (footprint "eagle-import:0402-CAP")
      (fields (field (name "PARTNO") "C0402C100J3GACTU"))
      (libsource (lib "eagle-import") (part "CAP0402"))
    )
    (comp (ref "C1110")
      (value "1000p/25V")
      (footprint "eagle-import:0402-CAP")
      (fields (field (name "PARTNO") "GRM1555C1E102JA01D"))
      (libsource (lib "eagle-import") (part "CAP0402"))
    )
    (comp (ref "J601")
      (value "DF13C-6P-1.25V")
      (footprint "eagle-import:DF13C-6P-1.25V")
      (fields (field (name "PARTNO") "DF13C-6P-1.25V(20)"))
      (libsource (lib "eagle-import") (part "DF13-6P-1.25V"))
    )
    (comp (ref "L1101")
      (value "KNH16C104DA5TS")
      (footprint "eagle-import:KYOCERA-KNH16-DA")
      (libsource (lib "eagle-import") (part "KNH16C104DA5TS"))
    )
    (comp (ref "L1102")
      (value "KNH16C104DA5TS")
      (footprint "eagle-import:KYOCERA-KNH16-DA")
      (libsource (lib "eagle-import") (part "KNH16C104DA5TS"))
    )
    (comp (ref "R1101")
      (value "10K/0.1%")
      (footprint "eagle-import:0402-RES")
      (fields (field (name "PARTNO") "ERA-2AEB103X"))
      (libsource (lib "eagle-import") (part "RESISTOR0402-RES"))
    )
    (comp (ref "R1102")
      (value "10K/0.1%")
      (footprint "eagle-import:0402-RES")
      (fields (field (name "PARTNO") "ERA-2AEB103X"))
      (libsource (lib "eagle-import") (part "RESISTOR0402-RES"))
    )
    (comp (ref "R1103")
      (value "1M")
      (footprint "eagle-import:0402-RES")
      (fields (field (name "PARTNO") "RC0402FR-071ML"))
      (libsource (lib "eagle-import") (part "RESISTOR0402-RES"))
    )
    (comp (ref "R1104")
      (value "1M")
      (footprint "eagle-import:0402-RES")
      (fields (field (name "PARTNO") "RC0402FR-071ML"))
      (libsource (lib "eagle-import") (part "RESISTOR0402-RES"))
    )
    (comp (ref "R1105")
      (value "453K")
      (footprint "eagle-import:0402-RES")
      (fields (field (name "PARTNO") "RMCF0402FT453K"))
      (libsource (lib "eagle-import") (part "RESISTOR0402-RES"))
    )
    (comp (ref "R1106")
      (value "56K")
      (footprint "eagle-import:0402-RES")
      (fields (field (name "PARTNO") "ERA-2AEB563X"))
      (libsource (lib "eagle-import") (part "RESISTOR0402-RES"))
    )
    (comp (ref "R1107")
      (value "105K")
      (footprint "eagle-import:0402-RES")
      (fields (field (name "PARTNO") "ERJ-2RKF1053X"))
      (libsource (lib "eagle-import") (part "RESISTOR0402-RES"))
    )
    (comp (ref "R1109")
      (value "453K")
      (footprint "eagle-import:0402-RES")
      (fields (field (name "PARTNO") "RMCF0402FT453K"))
      (libsource (lib "eagle-import") (part "RESISTOR0402-RES"))
    )
    (comp (ref "R1110")
      (value "56K")
      (footprint "eagle-import:0402-RES")
      (fields (field (name "PARTNO") "ERA-2AEB563X"))
      (libsource (lib "eagle-import") (part "RESISTOR0402-RES"))
    )
    (comp (ref "R1111")
      (value "105K")
      (footprint "eagle-import:0402-RES")
      (fields (field (name "PARTNO") "ERJ-2RKF1053X"))
      (libsource (lib "eagle-import") (part "RESISTOR0402-RES"))
    )
    (comp (ref "R1112")
      (value "453K")
      (footprint "eagle-import:0402-RES")
      (fields (field (name "PARTNO") "RMCF0402FT453K"))
      (libsource (lib "eagle-import") (part "RESISTOR0402-RES"))
    )
    (comp (ref "R1113")
      (value "56K")
      (footprint "eagle-import:0402-RES")
      (fields (field (name "PARTNO") "ERA-2AEB563X"))
      (libsource (lib "eagle-import") (part "RESISTOR0402-RES"))
    )
    (comp (ref "R1114")
      (value "105K")
      (footprint "eagle-import:0402-RES")
      (fields (field (name "PARTNO") "ERJ-2RKF1053X"))
      (libsource (lib "eagle-import") (part "RESISTOR0402-RES"))
    )
    (comp (ref "R1115")
      (value "0R")
      (footprint "eagle-import:0402-RES")
      (fields (field (name "PARTNO") "ERJ-2GE0R00X"))
      (libsource (lib "eagle-import") (part "RESISTOR0402-RES"))
    )
    (comp (ref "RN1101")
      (value "1M")
      (footprint "eagle-import:EXB28V")
      (fields (field (name "PARTNO") "EXB-28V105JX"))
      (libsource (lib "eagle-import") (part "4R-NEXB28V"))
    )
    (comp (ref "U1101")
      (value "LTC4417")
      (footprint "eagle-import:MO-220")
      (fields (field (name "PARTNO") "LTC4417IUF#PBF"))
      (libsource (lib "eagle-import") (part "LTC4117"))
    )
    (comp (ref "U1102")
      (value "NTHD4102PT1G")
      (footprint "eagle-import:1206-8")
      (fields (field (name "PARTNO") "NTHD4102PT1G"))
      (libsource (lib "eagle-import") (part "MOSFET-DUAL-PCHANNEL-CHIPFET"))
    )
    (comp (ref "U1103")
      (value "NTHD4102PT1G")
      (footprint "eagle-import:1206-8")
      (fields (field (name "PARTNO") "NTHD4102PT1G"))
      (libsource (lib "eagle-import") (part "MOSFET-DUAL-PCHANNEL-CHIPFET"))
    )
    (comp (ref "U1104")
      (value "NTHD4102PT1G")
      (footprint "eagle-import:1206-8")
      (fields (field (name "PARTNO") "NTHD4102PT1G"))
      (libsource (lib "eagle-import") (part "MOSFET-DUAL-PCHANNEL-CHIPFET"))
    )
    (comp (ref "C1001")
      (value "10u/25V")
      (footprint "eagle-import:0805-CAP")
      (fields (field (name "PARTNO") "CL21A106KAYNNNE"))
      (libsource (lib "eagle-import") (part "CAP0805"))
    )
    (comp (ref "C1002")
      (value "10n")
      (footprint "eagle-import:0402-CAP")
      (fields (field (name "PARTNO") "CC0402KRX7R7BB103"))
      (libsource (lib "eagle-import") (part "CAP0402"))
    )
    (comp (ref "C1003")
      (value "1u")
      (footprint "eagle-import:0603-CAP")
      (fields (field (name "PARTNO") "CC0603ZRY5V7BB105"))
      (libsource (lib "eagle-import") (part "CAP0603"))
    )
    (comp (ref "C1004")
      (value "10u")
      (footprint "eagle-import:0603-CAP")
      (fields (field (name "PARTNO") "C1608X5R1A106K080AC"))
      (libsource (lib "eagle-import") (part "CAP0603"))
    )
    (comp (ref "C1005")
      (value "0u1")
      (footprint "eagle-import:0402-CAP")
      (fields (field (name "PARTNO") "CC0402ZRY5V7BB104"))
      (libsource (lib "eagle-import") (part "CAP0402"))
    )
    (comp (ref "C1008")
      (value "2u2")
      (footprint "eagle-import:0402-CAP")
      (fields (field (name "PARTNO") "C1005X6S1C225K050BC"))
      (libsource (lib "eagle-import") (part "CAP0402"))
    )
    (comp (ref "D1001")
      (value "PMEG2005CT")
      (footprint "eagle-import:SOT23-3")
      (libsource (lib "eagle-import") (part "PMEG2005CT"))
    )
    (comp (ref "D1002")
      (value "PMEG2005CT")
      (footprint "eagle-import:SOT23-3")
      (libsource (lib "eagle-import") (part "PMEG2005CT"))
    )
    (comp (ref "F1001")
      (value "0ZCA0035FF2G")
      (footprint "eagle-import:PTC-1206")
      (libsource (lib "eagle-import") (part "PTCSMD"))
    )
    (comp (ref "R1001")
      (value "100K")
      (footprint "eagle-import:0402-RES")
      (fields (field (name "PARTNO") "RC0402FR-07100KL"))
      (libsource (lib "eagle-import") (part "RESISTOR0402-RES"))
    )
    (comp (ref "R1002")
      (value "10K")
      (footprint "eagle-import:0402-RES")
      (fields (field (name "PARTNO") "RC0402FR-0710KL"))
      (libsource (lib "eagle-import") (part "RESISTOR0402-RES"))
    )
    (comp (ref "U1001")
      (value "BQ24313")
      (footprint "eagle-import:QFN8-DSG")
      (fields (field (name "PARTNO") "BQ24313DSGT"))
      (libsource (lib "eagle-import") (part "BQ24313"))
    )
    (comp (ref "U1002")
      (value "MIC5332")
      (footprint "eagle-import:MLF-8-EPAD")
      (fields (field (name "PARTNO") "MIC5332-SSYMT"))
      (libsource (lib "eagle-import") (part "MIC5332"))
    )
    (comp (ref "C401")
      (value "0u1")
      (footprint "eagle-import:0402-CAP")
      (fields (field (name "PARTNO") "CC0402ZRY5V7BB104"))
      (libsource (lib "eagle-import") (part "CAP0402"))
    )
    (comp (ref "C402")
      (value "0u1")
      (footprint "eagle-import:0402-CAP")
      (fields (field (name "PARTNO") "CC0402ZRY5V7BB104"))
      (libsource (lib "eagle-import") (part "CAP0402"))
    )
    (comp (ref "D401")
      (value "PESD0402-140")
      (footprint "eagle-import:0402-TVS")
      (libsource (lib "eagle-import") (part "DIODE-TVS"))
    )
    (comp (ref "D402")
      (value "PESD0402-140")
      (footprint "eagle-import:0402-TVS")
      (libsource (lib "eagle-import") (part "DIODE-TVS"))
    )
    (comp (ref "D403")
      (value "PESD0402-140")
      (footprint "eagle-import:0402-TVS")
      (libsource (lib "eagle-import") (part "DIODE-TVS"))
    )
    (comp (ref "D404")
      (value "PESD0402-140")
      (footprint "eagle-import:0402-TVS")
      (libsource (lib "eagle-import") (part "DIODE-TVS"))
    )
    (comp (ref "J401")
      (value "DF13C-4P-1.25V")
      (footprint "eagle-import:DF13C-4P-1.25V")
      (fields (field (name "PARTNO") "DF13C-4P-1.25V(20)"))
      (libsource (lib "eagle-import") (part "DF13-4P-1.25V"))
    )
    (comp (ref "J402")
      (value "DF13C-3P-1.25V")
      (footprint "eagle-import:DF13C-3P-1.25V")
      (fields (field (name "PARTNO") "DF13C-3P-1.25V(20)"))
      (libsource (lib "eagle-import") (part "DF13-3P-1.25V"))
    )
    (comp (ref "J403")
      (value "DF13C-7P-1.25V")
      (footprint "eagle-import:DF13C-7P-1.25V")
      (fields (field (name "PARTNO") "DF13C-7P-1.25V(20)"))
      (libsource (lib "eagle-import") (part "DF13-7P-1.25V"))
    )
    (comp (ref "J404")
      (value "DF13C-5P-1.25V")
      (footprint "eagle-import:DF13C-5P-1.25V")
      (fields (field (name "PARTNO") "DF13C-5P-1.25V(20)"))
      (libsource (lib "eagle-import") (part "DF13-5P-1.25V"))
    )
    (comp (ref "J405")
      (value "DF13C-4P-1.25V")
      (footprint "eagle-import:DF13C-4P-1.25V")
      (fields (field (name "PARTNO") "DF13C-4P-1.25V(20)"))
      (libsource (lib "eagle-import") (part "DF13-4P-1.25V"))
    )
    (comp (ref "L401")
      (value "KNH16C104DA5TS")
      (footprint "eagle-import:KYOCERA-KNH16-DA")
      (libsource (lib "eagle-import") (part "KNH16C104DA5TS"))
    )
    (comp (ref "L402")
      (value "KNH16C104DA5TS")
      (footprint "eagle-import:KYOCERA-KNH16-DA")
      (libsource (lib "eagle-import") (part "KNH16C104DA5TS"))
    )
    (comp (ref "L403")
      (value "KNH16C104DA5TS")
      (footprint "eagle-import:KYOCERA-KNH16-DA")
      (libsource (lib "eagle-import") (part "KNH16C104DA5TS"))
    )
    (comp (ref "L404")
      (value "KNH16C104DA5TS")
      (footprint "eagle-import:KYOCERA-KNH16-DA")
      (libsource (lib "eagle-import") (part "KNH16C104DA5TS"))
    )
    (comp (ref "R401")
      (value "1K5")
      (footprint "eagle-import:0402-RES")
      (fields (field (name "PARTNO") "RC0402FR-071K5L"))
      (libsource (lib "eagle-import") (part "RESISTOR0402-RES"))
    )
    (comp (ref "R402")
      (value "1K5")
      (footprint "eagle-import:0402-RES")
      (fields (field (name "PARTNO") "RC0402FR-071K5L"))
      (libsource (lib "eagle-import") (part "RESISTOR0402-RES"))
    )
    (comp (ref "R403")
      (value "10K/0.1%")
      (footprint "eagle-import:0402-RES")
      (fields (field (name "PARTNO") "ERA-2AEB103X"))
      (libsource (lib "eagle-import") (part "RESISTOR0402-RES"))
    )
    (comp (ref "R404")
      (value "120R")
      (footprint "eagle-import:0402-RES")
      (fields (field (name "PARTNO") "RC0402FR-07120RL"))
      (libsource (lib "eagle-import") (part "RESISTOR0402-RES"))
    )
    (comp (ref "R405")
      (value "120R")
      (footprint "eagle-import:0402-RES")
      (fields (field (name "PARTNO") "RC0402FR-07120RL"))
      (libsource (lib "eagle-import") (part "RESISTOR0402-RES"))
    )
    (comp (ref "R406")
      (value "10K/0.1%")
      (footprint "eagle-import:0402-RES")
      (fields (field (name "PARTNO") "ERA-2AEB103X"))
      (libsource (lib "eagle-import") (part "RESISTOR0402-RES"))
    )
    (comp (ref "R407")
      (value "10K/0.1%")
      (footprint "eagle-import:0402-RES")
      (fields (field (name "PARTNO") "ERA-2AEB103X"))
      (libsource (lib "eagle-import") (part "RESISTOR0402-RES"))
    )
    (comp (ref "R408")
      (value "10K/0.1%")
      (footprint "eagle-import:0402-RES")
      (fields (field (name "PARTNO") "ERA-2AEB103X"))
      (libsource (lib "eagle-import") (part "RESISTOR0402-RES"))
    )
    (comp (ref "R409")
      (value "120R")
      (footprint "eagle-import:0402-RES")
      (fields (field (name "PARTNO") "RC0402FR-07120RL"))
      (libsource (lib "eagle-import") (part "RESISTOR0402-RES"))
    )
    (comp (ref "U401")
      (value "MAX3051")
      (footprint "eagle-import:SOT23-8")
      (fields (field (name "PARTNO") "MAX3051EKA"))
      (libsource (lib "eagle-import") (part "MAX3051MAX3051EKA"))
    )
    (comp (ref "C201")
      (value "0u1")
      (footprint "eagle-import:0402-CAP")
      (fields (field (name "PARTNO") "CC0402ZRY5V7BB104"))
      (libsource (lib "eagle-import") (part "CAP0402"))
    )
    (comp (ref "C202")
      (value "0u1")
      (footprint "eagle-import:0402-CAP")
      (fields (field (name "PARTNO") "CC0402ZRY5V7BB104"))
      (libsource (lib "eagle-import") (part "CAP0402"))
    )
    (comp (ref "D201")
      (value "PESD0402-140")
      (footprint "eagle-import:0402-TVS")
      (libsource (lib "eagle-import") (part "DIODE-TVS"))
    )
    (comp (ref "D202")
      (value "PESD0402-140")
      (footprint "eagle-import:0402-TVS")
      (libsource (lib "eagle-import") (part "DIODE-TVS"))
    )
    (comp (ref "D203")
      (value "PESD0402-140")
      (footprint "eagle-import:0402-TVS")
      (libsource (lib "eagle-import") (part "DIODE-TVS"))
    )
    (comp (ref "J201")
      (value "DF13C-6P-1.25V")
      (footprint "eagle-import:DF13C-6P-1.25V")
      (fields (field (name "PARTNO") "DF13C-6P-1.25V(20)"))
      (libsource (lib "eagle-import") (part "DF13-6P-1.25V"))
    )
    (comp (ref "J202")
      (value "DF13C-6P-1.25V")
      (footprint "eagle-import:DF13C-6P-1.25V")
      (fields (field (name "PARTNO") "DF13C-6P-1.25V(20)"))
      (libsource (lib "eagle-import") (part "DF13-6P-1.25V"))
    )
    (comp (ref "J203")
      (value "DF13C-6P-1.25V")
      (footprint "eagle-import:DF13C-6P-1.25V")
      (fields (field (name "PARTNO") "DF13C-6P-1.25V(20)"))
      (libsource (lib "eagle-import") (part "DF13-6P-1.25V"))
    )
    (comp (ref "J204")
      (value "DF13C-6P-1.25V")
      (footprint "eagle-import:DF13C-6P-1.25V")
      (fields (field (name "PARTNO") "DF13C-6P-1.25V(20)"))
      (libsource (lib "eagle-import") (part "DF13-6P-1.25V"))
    )
    (comp (ref "L201")
      (value "KNH16C104DA5TS")
      (footprint "eagle-import:KYOCERA-KNH16-DA")
      (libsource (lib "eagle-import") (part "KNH16C104DA5TS"))
    )
    (comp (ref "L202")
      (value "KNH16C104DA5TS")
      (footprint "eagle-import:KYOCERA-KNH16-DA")
      (libsource (lib "eagle-import") (part "KNH16C104DA5TS"))
    )
    (comp (ref "L203")
      (value "KNH16C104DA5TS")
      (footprint "eagle-import:KYOCERA-KNH16-DA")
      (libsource (lib "eagle-import") (part "KNH16C104DA5TS"))
    )
    (comp (ref "R201")
      (value "120R")
      (footprint "eagle-import:0402-RES")
      (fields (field (name "PARTNO") "RC0402FR-07120RL"))
      (libsource (lib "eagle-import") (part "RESISTOR0402-RES"))
    )
    (comp (ref "R202")
      (value "120R")
      (footprint "eagle-import:0402-RES")
      (fields (field (name "PARTNO") "RC0402FR-07120RL"))
      (libsource (lib "eagle-import") (part "RESISTOR0402-RES"))
    )
    (comp (ref "R203")
      (value "120R")
      (footprint "eagle-import:0402-RES")
      (fields (field (name "PARTNO") "RC0402FR-07120RL"))
      (libsource (lib "eagle-import") (part "RESISTOR0402-RES"))
    )
    (comp (ref "R204")
      (value "120R")
      (footprint "eagle-import:0402-RES")
      (fields (field (name "PARTNO") "RC0402FR-07120RL"))
      (libsource (lib "eagle-import") (part "RESISTOR0402-RES"))
    )
    (comp (ref "R205")
      (value "120R")
      (footprint "eagle-import:0402-RES")
      (fields (field (name "PARTNO") "RC0402FR-07120RL"))
      (libsource (lib "eagle-import") (part "RESISTOR0402-RES"))
    )
    (comp (ref "R206")
      (value "120R")
      (footprint "eagle-import:0402-RES")
      (fields (field (name "PARTNO") "RC0402FR-07120RL"))
      (libsource (lib "eagle-import") (part "RESISTOR0402-RES"))
    )
    (comp (ref "R207")
      (value "120R")
      (footprint "eagle-import:0402-RES")
      (fields (field (name "PARTNO") "RC0402FR-07120RL"))
      (libsource (lib "eagle-import") (part "RESISTOR0402-RES"))
    )
    (comp (ref "R208")
      (value "120R")
      (footprint "eagle-import:0402-RES")
      (fields (field (name "PARTNO") "RC0402FR-07120RL"))
      (libsource (lib "eagle-import") (part "RESISTOR0402-RES"))
    )
    (comp (ref "R209")
      (value "120R")
      (footprint "eagle-import:0402-RES")
      (fields (field (name "PARTNO") "RC0402FR-07120RL"))
      (libsource (lib "eagle-import") (part "RESISTOR0402-RES"))
    )
    (comp (ref "R210")
      (value "120R")
      (footprint "eagle-import:0402-RES")
      (fields (field (name "PARTNO") "RC0402FR-07120RL"))
      (libsource (lib "eagle-import") (part "RESISTOR0402-RES"))
    )
    (comp (ref "R211")
      (value "120R")
      (footprint "eagle-import:0402-RES")
      (fields (field (name "PARTNO") "RC0402FR-07120RL"))
      (libsource (lib "eagle-import") (part "RESISTOR0402-RES"))
    )
    (comp (ref "R212")
      (value "120R")
      (footprint "eagle-import:0402-RES")
      (fields (field (name "PARTNO") "RC0402FR-07120RL"))
      (libsource (lib "eagle-import") (part "RESISTOR0402-RES"))
    )
    (comp (ref "R213")
      (value "120R")
      (footprint "eagle-import:0402-RES")
      (fields (field (name "PARTNO") "RC0402FR-07120RL"))
      (libsource (lib "eagle-import") (part "RESISTOR0402-RES"))
    )
    (comp (ref "R214")
      (value "120R")
      (footprint "eagle-import:0402-RES")
      (fields (field (name "PARTNO") "RC0402FR-07120RL"))
      (libsource (lib "eagle-import") (part "RESISTOR0402-RES"))
    )
    (comp (ref "R215")
      (value "120R")
      (footprint "eagle-import:0402-RES")
      (fields (field (name "PARTNO") "RC0402FR-07120RL"))
      (libsource (lib "eagle-import") (part "RESISTOR0402-RES"))
    )
    (comp (ref "R216")
      (value "120R")
      (footprint "eagle-import:0402-RES")
      (fields (field (name "PARTNO") "RC0402FR-07120RL"))
      (libsource (lib "eagle-import") (part "RESISTOR0402-RES"))
    )
    (comp (ref "U201")
      (value "TXS0108QFN20")
      (footprint "eagle-import:QFN20-RGY")
      (fields (field (name "PARTNO") "TXS0108ERGYR"))
      (libsource (lib "eagle-import") (part "TXS0108QFN20"))
    )
    (comp (ref "U202")
      (value "TXS0108QFN20")
      (footprint "eagle-import:QFN20-RGY")
      (fields (field (name "PARTNO") "TXS0108ERGYR"))
      (libsource (lib "eagle-import") (part "TXS0108QFN20"))
    )
    (comp (ref "C901")
      (value "0u1")
      (footprint "eagle-import:0402-CAP")
      (fields (field (name "PARTNO") "CC0402ZRY5V7BB104"))
      (libsource (lib "eagle-import") (part "CAP0402"))
    )
    (comp (ref "C902")
      (value "0u1")
      (footprint "eagle-import:0402-CAP")
      (fields (field (name "PARTNO") "CC0402ZRY5V7BB104"))
      (libsource (lib "eagle-import") (part "CAP0402"))
    )
    (comp (ref "C903")
      (value "0u1")
      (footprint "eagle-import:0402-CAP")
      (fields (field (name "PARTNO") "CC0402ZRY5V7BB104"))
      (libsource (lib "eagle-import") (part "CAP0402"))
    )
    (comp (ref "D901")
      (value "PESD0402-140")
      (footprint "eagle-import:0402-TVS")
      (libsource (lib "eagle-import") (part "DIODE-TVS"))
    )
    (comp (ref "D902")
      (value "PESD0402-140")
      (footprint "eagle-import:0402-TVS")
      (libsource (lib "eagle-import") (part "DIODE-TVS"))
    )
    (comp (ref "D903")
      (value "PESD0402-140")
      (footprint "eagle-import:0402-TVS")
      (libsource (lib "eagle-import") (part "DIODE-TVS"))
    )
    (comp (ref "D904")
      (value "MSS1P4-M3")
      (footprint "eagle-import:MICROSMP")
      (fields (field (name "PARTNO") "MSS1P4-M3/89A"))
      (libsource (lib "eagle-import") (part "DIODE-SCHOTTKY_MSMP"))
    )
    (comp (ref "J901")
      (value "HEADER-3X163X16RA")
      (footprint "eagle-import:3X16RA")
      (fields (field (name "BOM") "EXCLUDE"))
      (libsource (lib "eagle-import") (part "HEADER-3X163X16RA"))
    )
    (comp (ref "L901")
      (value "KNH16C104DA5TS")
      (footprint "eagle-import:KYOCERA-KNH16-DA")
      (libsource (lib "eagle-import") (part "KNH16C104DA5TS"))
    )
    (comp (ref "R901")
      (value "10K")
      (footprint "eagle-import:0402-RES")
      (fields (field (name "PARTNO") "RC0402FR-0710KL"))
      (libsource (lib "eagle-import") (part "RESISTOR0402-RES"))
    )
    (comp (ref "R902")
      (value "220R")
      (footprint "eagle-import:0402-RES")
      (fields (field (name "PARTNO") "RC0402FR-07220RL"))
      (libsource (lib "eagle-import") (part "RESISTOR0402-RES"))
    )
    (comp (ref "R903")
      (value "220R")
      (footprint "eagle-import:0402-RES")
      (fields (field (name "PARTNO") "RC0402FR-07220RL"))
      (libsource (lib "eagle-import") (part "RESISTOR0402-RES"))
    )
    (comp (ref "R904")
      (value "220R")
      (footprint "eagle-import:0402-RES")
      (fields (field (name "PARTNO") "RC0402FR-07220RL"))
      (libsource (lib "eagle-import") (part "RESISTOR0402-RES"))
    )
    (comp (ref "R905")
      (value "220R")
      (footprint "eagle-import:0402-RES")
      (fields (field (name "PARTNO") "RC0402FR-07220RL"))
      (libsource (lib "eagle-import") (part "RESISTOR0402-RES"))
    )
    (comp (ref "R906")
      (value "220R")
      (footprint "eagle-import:0402-RES")
      (fields (field (name "PARTNO") "RC0402FR-07220RL"))
      (libsource (lib "eagle-import") (part "RESISTOR0402-RES"))
    )
    (comp (ref "R907")
      (value "220R")
      (footprint "eagle-import:0402-RES")
      (fields (field (name "PARTNO") "RC0402FR-07220RL"))
      (libsource (lib "eagle-import") (part "RESISTOR0402-RES"))
    )
    (comp (ref "R908")
      (value "220R")
      (footprint "eagle-import:0402-RES")
      (fields (field (name "PARTNO") "RC0402FR-07220RL"))
      (libsource (lib "eagle-import") (part "RESISTOR0402-RES"))
    )
    (comp (ref "R909")
      (value "220R")
      (footprint "eagle-import:0402-RES")
      (fields (field (name "PARTNO") "RC0402FR-07220RL"))
      (libsource (lib "eagle-import") (part "RESISTOR0402-RES"))
    )
    (comp (ref "R910")
      (value "220R")
      (footprint "eagle-import:0402-RES")
      (fields (field (name "PARTNO") "RC0402FR-07220RL"))
      (libsource (lib "eagle-import") (part "RESISTOR0402-RES"))
    )
    (comp (ref "R911")
      (value "220R")
      (footprint "eagle-import:0402-RES")
      (fields (field (name "PARTNO") "RC0402FR-07220RL"))
      (libsource (lib "eagle-import") (part "RESISTOR0402-RES"))
    )
    (comp (ref "R912")
      (value "220R")
      (footprint "eagle-import:0402-RES")
      (fields (field (name "PARTNO") "RC0402FR-07220RL"))
      (libsource (lib "eagle-import") (part "RESISTOR0402-RES"))
    )
    (comp (ref "R913")
      (value "220R")
      (footprint "eagle-import:0402-RES")
      (fields (field (name "PARTNO") "RC0402FR-07220RL"))
      (libsource (lib "eagle-import") (part "RESISTOR0402-RES"))
    )
    (comp (ref "R914")
      (value "220R")
      (footprint "eagle-import:0402-RES")
      (fields (field (name "PARTNO") "RC0402FR-07220RL"))
      (libsource (lib "eagle-import") (part "RESISTOR0402-RES"))
    )
    (comp (ref "R915")
      (value "220R")
      (footprint "eagle-import:0402-RES")
      (fields (field (name "PARTNO") "RC0402FR-07220RL"))
      (libsource (lib "eagle-import") (part "RESISTOR0402-RES"))
    )
    (comp (ref "R916")
      (value "220R")
      (footprint "eagle-import:0402-RES")
      (fields (field (name "PARTNO") "RC0402FR-07220RL"))
      (libsource (lib "eagle-import") (part "RESISTOR0402-RES"))
    )
    (comp (ref "R917")
      (value "220R")
      (footprint "eagle-import:0402-RES")
      (fields (field (name "PARTNO") "RC0402FR-07220RL"))
      (libsource (lib "eagle-import") (part "RESISTOR0402-RES"))
    )
    (comp (ref "R918")
      (value "10K/0.1%")
      (footprint "eagle-import:0402-RES")
      (fields (field (name "PARTNO") "ERA-2AEB103X"))
      (libsource (lib "eagle-import") (part "RESISTOR0402-RES"))
    )
    (comp (ref "R919")
      (value "10K/0.1%")
      (footprint "eagle-import:0402-RES")
      (fields (field (name "PARTNO") "ERA-2AEB103X"))
      (libsource (lib "eagle-import") (part "RESISTOR0402-RES"))
    )
    (comp (ref "R922")
      (value "10K/0.1%")
      (footprint "eagle-import:0402-RES")
      (fields (field (name "PARTNO") "ERA-2AEB103X"))
      (libsource (lib "eagle-import") (part "RESISTOR0402-RES"))
    )
    (comp (ref "U901")
      (value "TXS0108QFN20")
      (footprint "eagle-import:QFN20-RGY")
      (fields (field (name "PARTNO") "TXS0108ERGYR"))
      (libsource (lib "eagle-import") (part "TXS0108QFN20"))
    )
    (comp (ref "U902")
      (value "TXS0108QFN20")
      (footprint "eagle-import:QFN20-RGY")
      (fields (field (name "PARTNO") "TXS0108ERGYR"))
      (libsource (lib "eagle-import") (part "TXS0108QFN20"))
    )
    (comp (ref "U903")
      (value "74LVC2G240")
      (footprint "eagle-import:TSSOP8_SOT505-2")
      (fields (field (name "PARTNO") "74LVC2G240DP,125"))
      (libsource (lib "eagle-import") (part "74LVC2G240-TSSOP-8"))
    )
    (comp (ref "C801")
      (value "0u1")
      (footprint "eagle-import:0402-CAP")
      (fields (field (name "PARTNO") "CC0402ZRY5V7BB104"))
      (libsource (lib "eagle-import") (part "CAP0402"))
    )
    (comp (ref "C802")
      (value "0u1")
      (footprint "eagle-import:0402-CAP")
      (fields (field (name "PARTNO") "CC0402ZRY5V7BB104"))
      (libsource (lib "eagle-import") (part "CAP0402"))
    )
    (comp (ref "C803")
      (value "0u1")
      (footprint "eagle-import:0402-CAP")
      (fields (field (name "PARTNO") "CC0402ZRY5V7BB104"))
      (libsource (lib "eagle-import") (part "CAP0402"))
    )
    (comp (ref "C804")
      (value "0u1")
      (footprint "eagle-import:0402-CAP")
      (fields (field (name "PARTNO") "CC0402ZRY5V7BB104"))
      (libsource (lib "eagle-import") (part "CAP0402"))
    )
    (comp (ref "C805")
      (value "8p")
      (footprint "eagle-import:0402-CAP")
      (fields (field (name "PARTNO") "C1005C0G1H080C"))
      (libsource (lib "eagle-import") (part "CAP0402"))
    )
    (comp (ref "C806")
      (value "8p")
      (footprint "eagle-import:0402-CAP")
      (fields (field (name "PARTNO") "C1005C0G1H080C"))
      (libsource (lib "eagle-import") (part "CAP0402"))
    )
    (comp (ref "D801")
      (value "PESD0402-140")
      (footprint "eagle-import:0402-TVS")
      (libsource (lib "eagle-import") (part "DIODE-TVS"))
    )
    (comp (ref "J801")
      (value "JST-ZH-3")
      (footprint "eagle-import:JST-ZH-SMT-VERTICAL")
      (fields (field (name "PARTNO") "B3B-ZR-SM4-TF (LF)(SN)(P)"))
      (libsource (lib "eagle-import") (part "JST-ZH-3"))
    )
    (comp (ref "JX801")
      (value "HEADER-3X1BOARDEDGE-SHORT")
      (footprint "eagle-import:HEADER_3X01_SMD_H_BOARD_EDGE_SHORT")
      (libsource (lib "eagle-import") (part "HEADER-3X1BOARDEDGE-SHORT"))
    )
    (comp (ref "JX802")
      (value "ARM_MINI_JTAG-SMT")
      (footprint "eagle-import:FTSH-105-01-XXX-DV-K")
      (fields (field (name "BOM") "EXCLUDE") (field (name "PARTNO") "M50-3900542"))
      (libsource (lib "eagle-import") (part "ARM_MINI_JTAG-SMT"))
    )
    (comp (ref "R801")
      (value "10K")
      (footprint "eagle-import:0402-RES")
      (fields (field (name "PARTNO") "RC0402FR-0710KL"))
      (libsource (lib "eagle-import") (part "RESISTOR0402-RES"))
    )
    (comp (ref "R802")
      (value "10K")
      (footprint "eagle-import:0402-RES")
      (fields (field (name "PARTNO") "RC0402FR-0710KL"))
      (libsource (lib "eagle-import") (part "RESISTOR0402-RES"))
    )
    (comp (ref "R803")
      (value "220R")
      (footprint "eagle-import:0402-RES")
      (fields (field (name "PARTNO") "RC0402FR-07220RL"))
      (libsource (lib "eagle-import") (part "RESISTOR0402-RES"))
    )
    (comp (ref "R804")
      (value "220R")
      (footprint "eagle-import:0402-RES")
      (fields (field (name "PARTNO") "RC0402FR-07220RL"))
      (libsource (lib "eagle-import") (part "RESISTOR0402-RES"))
    )
    (comp (ref "S801")
      (value "RESET")
      (footprint "eagle-import:EVQP7J01K")
      (fields (field (name "PARTNO") "EVQ-P7J01P"))
      (libsource (lib "eagle-import") (part "SWITCH-MOMENTARY-2"))
    )
    (comp (ref "U801")
      (value "STM32F10XCXT6")
      (footprint "eagle-import:TQFP48")
      (fields (field (name "PARTNO") "STM32F100C8T6B"))
      (libsource (lib "eagle-import") (part "STM32F10XCXT6"))
    )
    (comp (ref "X801")
      (value "3.2x2.5 mm / 24 MHz / 15 ppm")
      (footprint "eagle-import:OSCILLATOR-3.2X2.5")
      (fields (field (name "PARTNO") "NX3225SA-24.000000MHZ"))
      (libsource (lib "eagle-import") (part "OSCILLATOR-3.2X2.5"))
    )
    (comp (ref "C501")
      (value "10u/10V")
      (footprint "eagle-import:0805-CAP")
      (fields (field (name "PARTNO") "CC0805ZKY5V6BB106"))
      (libsource (lib "eagle-import") (part "CAP0805"))
    )
    (comp (ref "C502")
      (value "0u1")
      (footprint "eagle-import:0402-CAP")
      (fields (field (name "PARTNO") "CC0402ZRY5V7BB104"))
      (libsource (lib "eagle-import") (part "CAP0402"))
    )
    (comp (ref "C503")
      (value "0u1")
      (footprint "eagle-import:0402-CAP")
      (fields (field (name "PARTNO") "CC0402ZRY5V7BB104"))
      (libsource (lib "eagle-import") (part "CAP0402"))
    )
    (comp (ref "C504")
      (value "10n")
      (footprint "eagle-import:0402-CAP")
      (fields (field (name "PARTNO") "CC0402KRX7R7BB103"))
      (libsource (lib "eagle-import") (part "CAP0402"))
    )
    (comp (ref "C505")
      (value "10n")
      (footprint "eagle-import:0402-CAP")
      (fields (field (name "PARTNO") "CC0402KRX7R7BB103"))
      (libsource (lib "eagle-import") (part "CAP0402"))
    )
    (comp (ref "C506")
      (value "10u/10V")
      (footprint "eagle-import:0805-CAP")
      (fields (field (name "PARTNO") "CC0805ZKY5V6BB106"))
      (libsource (lib "eagle-import") (part "CAP0805"))
    )
    (comp (ref "C507")
      (value "0u1")
      (footprint "eagle-import:0402-CAP")
      (fields (field (name "PARTNO") "CC0402ZRY5V7BB104"))
      (libsource (lib "eagle-import") (part "CAP0402"))
    )
    (comp (ref "C508")
      (value "0u1")
      (footprint "eagle-import:0402-CAP")
      (fields (field (name "PARTNO") "CC0402ZRY5V7BB104"))
      (libsource (lib "eagle-import") (part "CAP0402"))
    )
    (comp (ref "C509")
      (value "10u/10V")
      (footprint "eagle-import:0805-CAP")
      (fields (field (name "PARTNO") "CC0805ZKY5V6BB106"))
      (libsource (lib "eagle-import") (part "CAP0805"))
    )
    (comp (ref "C510")
      (value "0u47")
      (footprint "eagle-import:0402-CAP")
      (fields (field (name "PARTNO") "C1005X5R1C474K050BC"))
      (libsource (lib "eagle-import") (part "CAP0402"))
    )
    (comp (ref "C511")
      (value "10u/10V")
      (footprint "eagle-import:0805-CAP")
      (fields (field (name "PARTNO") "CC0805ZKY5V6BB106"))
      (libsource (lib "eagle-import") (part "CAP0805"))
    )
    (comp (ref "C512")
      (value "2u2")
      (footprint "eagle-import:0603-CAP")
      (fields (field (name "PARTNO") "C1608X6S1C225K080AC"))
      (libsource (lib "eagle-import") (part "CAP0603"))
    )
    (comp (ref "C513")
      (value "2u2")
      (footprint "eagle-import:0603-CAP")
      (fields (field (name "PARTNO") "C1608X6S1C225K080AC"))
      (libsource (lib "eagle-import") (part "CAP0603"))
    )
    (comp (ref "C514")
      (value "0u1")
      (footprint "eagle-import:0402-CAP")
      (fields (field (name "PARTNO") "CC0402ZRY5V7BB104"))
      (libsource (lib "eagle-import") (part "CAP0402"))
    )
    (comp (ref "C515")
      (value "0u01")
      (footprint "eagle-import:0603-CAP")
      (fields (field (name "PARTNO") "06033C103JAT2A"))
      (libsource (lib "eagle-import") (part "CAP0603"))
    )
    (comp (ref "U501")
      (value "L3GD20")
      (footprint "eagle-import:L3G4200DH-MAN")
      (libsource (lib "eagle-import") (part "L3G4200DH-LL"))
    )
    (comp (ref "U502")
      (value "L3GD20H")
      (footprint "eagle-import:LGA-16L")
      (libsource (lib "eagle-import") (part "L3GD20H"))
    )
    (comp (ref "U504")
      (value "LSM303D")
      (footprint "eagle-import:LGA-16L")
      (libsource (lib "eagle-import") (part "LSM303D"))
    )
    (comp (ref "U505")
      (value "MPU-6000")
      (footprint "eagle-import:QFN-24")
      (libsource (lib "eagle-import") (part "MPU-6000"))
    )
    (comp (ref "U506")
      (value "MS5611-01BA")
      (footprint "eagle-import:MS5611-01BA")
      (libsource (lib "eagle-import") (part "MS5611-01BA"))
    )
    (comp (ref "X503")
      (value "0512811094")
      (footprint "eagle-import:51281-1094")
      (fields (field (name "BOM") "EXCLUDE") (field (name "PARTNO") "0781191109"))
      (libsource (lib "eagle-import") (part "CONN_FPC_10RA"))
    )
    (comp (ref "C701")
      (value "0u1")
      (footprint "eagle-import:0402-CAP")
      (fields (field (name "PARTNO") "CC0402ZRY5V7BB104"))
      (libsource (lib "eagle-import") (part "CAP0402"))
    )
    (comp (ref "C702")
      (value "1u")
      (footprint "eagle-import:0603-CAP")
      (fields (field (name "PARTNO") "CC0603ZRY5V7BB105"))
      (libsource (lib "eagle-import") (part "CAP0603"))
    )
    (comp (ref "C703")
      (value "5n6")
      (footprint "eagle-import:0402-CAP")
      (fields (field (name "PARTNO") "C0402C562K5RACTU"))
      (libsource (lib "eagle-import") (part "CAP0402"))
    )
    (comp (ref "C704")
      (value "0u47")
      (footprint "eagle-import:0402-CAP")
      (fields (field (name "PARTNO") "C1005X5R1C474K050BC"))
      (libsource (lib "eagle-import") (part "CAP0402"))
    )
    (comp (ref "D701")
      (value "PESD0402-140")
      (footprint "eagle-import:0402-TVS")
      (libsource (lib "eagle-import") (part "DIODE-TVS"))
    )
    (comp (ref "J701")
      (value "DF13C-2P-1.25V")
      (footprint "eagle-import:DF13C-2P-1.25V")
      (fields (field (name "PARTNO") "DF13C-2P-1.25V(20)"))
      (libsource (lib "eagle-import") (part "DF13-2P-1.25V"))
    )
    (comp (ref "J702")
      (value "DF13C-3P-1.25V")
      (footprint "eagle-import:DF13C-3P-1.25V")
      (fields (field (name "PARTNO") "DF13C-3P-1.25V(20)"))
      (libsource (lib "eagle-import") (part "DF13-3P-1.25V"))
    )
    (comp (ref "L701")
      (value "47uH")
      (footprint "eagle-import:0805-IND")
      (fields (field (name "PARTNO") "MLZ2012M470W"))
      (libsource (lib "eagle-import") (part "INDUCTOR0805"))
    )
    (comp (ref "LED701")
      (value "AMBER")
      (footprint "eagle-import:0603-LED")
      (fields (field (name "PARTNO") "APTD1608SECK"))
      (libsource (lib "eagle-import") (part "LED0603"))
    )
    (comp (ref "LED702")
      (value "GREEN")
      (footprint "eagle-import:0603-LED")
      (fields (field (name "PARTNO") "APTD1608CGCK"))
      (libsource (lib "eagle-import") (part "LED0603"))
    )
    (comp (ref "LED703")
      (value "AMBER")
      (footprint "eagle-import:0603-LED")
      (fields (field (name "PARTNO") "APTD1608SECK"))
      (libsource (lib "eagle-import") (part "LED0603"))
    )
    (comp (ref "LED704")
      (value "GREEN")
      (footprint "eagle-import:0603-LED")
      (fields (field (name "PARTNO") "APTD1608CGCK"))
      (libsource (lib "eagle-import") (part "LED0603"))
    )
    (comp (ref "LED705")
      (value "BLUE")
      (footprint "eagle-import:0603-LED")
      (fields (field (name "PARTNO") "APTD1608QBC/D"))
      (libsource (lib "eagle-import") (part "LED0603"))
    )
    (comp (ref "R701")
      (value "9K09")
      (footprint "eagle-import:0402-RES")
      (fields (field (name "PARTNO") "RMCF0402FT9K09"))
      (libsource (lib "eagle-import") (part "RESISTOR0402-RES"))
    )
    (comp (ref "R702")
      (value "10K")
      (footprint "eagle-import:0402-RES")
      (fields (field (name "PARTNO") "RC0402FR-0710KL"))
      (libsource (lib "eagle-import") (part "RESISTOR0402-RES"))
    )
    (comp (ref "R703")
      (value "100K")
      (footprint "eagle-import:0402-RES")
      (fields (field (name "PARTNO") "RC0402FR-07100KL"))
      (libsource (lib "eagle-import") (part "RESISTOR0402-RES"))
    )
    (comp (ref "R704")
      (value "10K")
      (footprint "eagle-import:0402-RES")
      (fields (field (name "PARTNO") "RC0402FR-0710KL"))
      (libsource (lib "eagle-import") (part "RESISTOR0402-RES"))
    )
    (comp (ref "R705")
      (value "453K")
      (footprint "eagle-import:0402-RES")
      (fields (field (name "PARTNO") "RMCF0402FT453K"))
      (libsource (lib "eagle-import") (part "RESISTOR0402-RES"))
    )
    (comp (ref "R706")
      (value "16K5")
      (footprint "eagle-import:0402-RES")
      (fields (field (name "PARTNO") "RMCF0402FT16K5"))
      (libsource (lib "eagle-import") (part "RESISTOR0402-RES"))
    )
    (comp (ref "R707")
      (value "220R")
      (footprint "eagle-import:0402-RES")
      (fields (field (name "PARTNO") "RC0402FR-07220RL"))
      (libsource (lib "eagle-import") (part "RESISTOR0402-RES"))
    )
    (comp (ref "R708")
      (value "220R")
      (footprint "eagle-import:0402-RES")
      (fields (field (name "PARTNO") "RC0402FR-07220RL"))
      (libsource (lib "eagle-import") (part "RESISTOR0402-RES"))
    )
    (comp (ref "R709")
      (value "220R")
      (footprint "eagle-import:0402-RES")
      (fields (field (name "PARTNO") "RC0402FR-07220RL"))
      (libsource (lib "eagle-import") (part "RESISTOR0402-RES"))
    )
    (comp (ref "R710")
      (value "68R")
      (footprint "eagle-import:0402-RES")
      (fields (field (name "PARTNO") "ERJ-2GEJ680X"))
      (libsource (lib "eagle-import") (part "RESISTOR0402-RES"))
    )
    (comp (ref "R711")
      (value "220R")
      (footprint "eagle-import:0402-RES")
      (fields (field (name "PARTNO") "RC0402FR-07220RL"))
      (libsource (lib "eagle-import") (part "RESISTOR0402-RES"))
    )
    (comp (ref "R712")
      (value "220R")
      (footprint "eagle-import:0402-RES")
      (fields (field (name "PARTNO") "RC0402FR-07220RL"))
      (libsource (lib "eagle-import") (part "RESISTOR0402-RES"))
    )
    (comp (ref "R713")
      (value "1K5")
      (footprint "eagle-import:0402-RES")
      (fields (field (name "PARTNO") "RC0402FR-071K5L"))
      (libsource (lib "eagle-import") (part "RESISTOR0402-RES"))
    )
    (comp (ref "R735")
      (value "220R")
      (footprint "eagle-import:0402-RES")
      (fields (field (name "PARTNO") "RC0402FR-07220RL"))
      (libsource (lib "eagle-import") (part "RESISTOR0402-RES"))
    )
    (comp (ref "R736")
      (value "220R")
      (footprint "eagle-import:0402-RES")
      (fields (field (name "PARTNO") "RC0402FR-07220RL"))
      (libsource (lib "eagle-import") (part "RESISTOR0402-RES"))
    )
    (comp (ref "U701")
      (value "TCA62724FMG")
      (footprint "eagle-import:SON10")
      (libsource (lib "eagle-import") (part "TCA62724FMG"))
    )
    (comp (ref "U702")
      (value "LT3469")
      (footprint "eagle-import:SOT23-8")
      (fields (field (name "PARTNO") "LT3469ETS8"))
      (libsource (lib "eagle-import") (part "LT3469"))
    )
    (comp (ref "U703")
      (value "LRTB GFTG-T7AW-1+V7A7-29+R5T9-49-L")
      (footprint "eagle-import:6-PLCC")
      (fields (field (name "PARTNO") "LRTB GFTG-T7AW-1+V7A7-29+R5T9-49-L"))
      (libsource (lib "eagle-import") (part "RGB-LED6-PLCC"))
    )
  )
  (nets
    (net (code "1") (name "ACCEL_DRDY") (class "Default")
      (node (ref "U101") (pin "90") (pinfunction "PB4_90") (pintype "bidirectional"))
      (node (ref "U504") (pin "11") (pinfunction "INT1_11") (pintype "bidirectional"))
      (node (ref "X503") (pin "3") (pinfunction "S_3") (pintype "passive"))
    )
    (net (code "2") (name "ALARM") (class "Default")
      (node (ref "R701") (pin "P$2") (pinfunction "2_P$2") (pintype "passive"))
      (node (ref "U101") (pin "77") (pinfunction "PA15_77") (pintype "bidirectional"))
    )
    (net (code "3") (name "BATT_CURRENT_SENS") (class "Default")
      (node (ref "R1101") (pin "P$1") (pinfunction "1_P$1") (pintype "passive"))
      (node (ref "U101") (pin "26") (pinfunction "PA3_26") (pintype "bidirectional"))
    )
    (net (code "4") (name "BATT_VOLTAGE_SENS") (class "Default")
      (node (ref "R1102") (pin "P$1") (pinfunction "1_P$1") (pintype "passive"))
      (node (ref "U101") (pin "25") (pinfunction "PA2_25") (pintype "bidirectional"))
    )
    (net (code "5") (name "CAN1_RX") (class "Default")
      (node (ref "U101") (pin "81") (pinfunction "PD0_81") (pintype "bidirectional"))
      (node (ref "U401") (pin "4") (pinfunction "DOUT_4") (pintype "output"))
    )
    (net (code "6") (name "CAN1_TX") (class "Default")
      (node (ref "U101") (pin "82") (pinfunction "PD1_82") (pintype "bidirectional"))
      (node (ref "U401") (pin "1") (pinfunction "DIN_1") (pintype "input"))
    )
    (net (code "7") (name "CAN2_RX") (class "Default")
      (node (ref "R216") (pin "P$1") (pinfunction "1_P$1") (pintype "passive"))
      (node (ref "U101") (pin "51") (pinfunction "PB12_51") (pintype "bidirectional"))
    )
    (net (code "8") (name "CAN2_TX") (class "Default")
      (node (ref "R215") (pin "P$1") (pinfunction "1_P$1") (pintype "passive"))
      (node (ref "U101") (pin "92") (pinfunction "PB6_92") (pintype "bidirectional"))
    )
    (net (code "9") (name "CAN_H") (class "Default")
      (node (ref "CAN_H") (pin "P$1") (pinfunction "P$1_P$1") (pintype "passive"))
      (node (ref "J405") (pin "2") (pinfunction "2_2") (pintype "passive"))
      (node (ref "R409") (pin "P$1") (pinfunction "1_P$1") (pintype "passive"))
      (node (ref "U401") (pin "7") (pinfunction "CANH_7") (pintype "bidirectional"))
    )
    (net (code "10") (name "CAN_L") (class "Default")
      (node (ref "CAN_L") (pin "P$1") (pinfunction "P$1_P$1") (pintype "passive"))
      (node (ref "J405") (pin "3") (pinfunction "3_3") (pintype "passive"))
      (node (ref "R409") (pin "P$2") (pinfunction "2_P$2") (pintype "passive"))
      (node (ref "U401") (pin "6") (pinfunction "CANL_6") (pintype "bidirectional"))
    )
    (net (code "11") (name "FMU-BOOT0") (class "Default")
      (node (ref "FMU-BOOT1101") (pin "P$1") (pinfunction "P$1_P$1") (pintype "passive"))
      (node (ref "R611") (pin "P$2") (pinfunction "2_P$2") (pintype "passive"))
      (node (ref "U101") (pin "94") (pinfunction "BOOT0_94") (pintype "input"))
    )
    (net (code "12") (name "FMU-CH1") (class "Default")
      (node (ref "U101") (pin "45") (pinfunction "PE14_45") (pintype "bidirectional"))
      (node (ref "U901") (pin "7") (pinfunction "A6_7") (pintype "bidirectional"))
    )
    (net (code "13") (name "FMU-CH2") (class "Default")
      (node (ref "U101") (pin "44") (pinfunction "PE13_44") (pintype "bidirectional"))
      (node (ref "U901") (pin "6") (pinfunction "A5_6") (pintype "bidirectional"))
    )
    (net (code "14") (name "FMU-CH3") (class "Default")
      (node (ref "U101") (pin "42") (pinfunction "PE11_42") (pintype "bidirectional"))
      (node (ref "U901") (pin "5") (pinfunction "A4_5") (pintype "bidirectional"))
    )
    (net (code "15") (name "FMU-CH4") (class "Default")
      (node (ref "U101") (pin "40") (pinfunction "PE9_40") (pintype "bidirectional"))
      (node (ref "U901") (pin "4") (pinfunction "A3_4") (pintype "bidirectional"))
    )
    (net (code "16") (name "FMU-CH5") (class "Default")
      (node (ref "U101") (pin "60") (pinfunction "PD13_60") (pintype "bidirectional"))
      (node (ref "U901") (pin "3") (pinfunction "A2_3") (pintype "bidirectional"))
    )
    (net (code "17") (name "FMU-CH6") (class "Default")
      (node (ref "U101") (pin "61") (pinfunction "PD14_61") (pintype "bidirectional"))
      (node (ref "U901") (pin "1") (pinfunction "A1_1") (pintype "bidirectional"))
    )
    (net (code "18") (name "FMU-I2C1_SCL") (class "Default")
      (node (ref "R401") (pin "P$1") (pinfunction "1_P$1") (pintype "passive"))
      (node (ref "R404") (pin "P$1") (pinfunction "1_P$1") (pintype "passive"))
      (node (ref "U101") (pin "95") (pinfunction "PB8_95") (pintype "bidirectional"))
    )
    (net (code "19") (name "FMU-I2C1_SDA") (class "Default")
      (node (ref "R402") (pin "P$1") (pinfunction "1_P$1") (pintype "passive"))
      (node (ref "R405") (pin "P$1") (pinfunction "1_P$1") (pintype "passive"))
      (node (ref "U101") (pin "96") (pinfunction "PB9_96") (pintype "bidirectional"))
    )
    (net (code "20") (name "FMU-I2C2_SCL") (class "Default")
      (node (ref "R306") (pin "P$1") (pinfunction "1_P$1") (pintype "passive"))
      (node (ref "U101") (pin "47") (pinfunction "PB10_47") (pintype "bidirectional"))
      (node (ref "U701") (pin "3") (pinfunction "SCL_3") (pintype "bidirectional"))
    )
    (net (code "21") (name "FMU-I2C2_SDA") (class "Default")
      (node (ref "R307") (pin "P$1") (pinfunction "1_P$1") (pintype "passive"))
      (node (ref "U101") (pin "48") (pinfunction "PB11_48") (pintype "bidirectional"))
      (node (ref "U701") (pin "2") (pinfunction "SDA_2") (pintype "bidirectional"))
    )
    (net (code "22") (name "FMU-SWCLK") (class "Default")
      (node (ref "JX301") (pin "4") (pinfunction "S_4") (pintype "passive"))
      (node (ref "U101") (pin "76") (pinfunction "PA14_76") (pintype "bidirectional"))
    )
    (net (code "23") (name "FMU-SWDIO") (class "Default")
      (node (ref "JX301") (pin "2") (pinfunction "S_2") (pintype "passive"))
      (node (ref "U101") (pin "72") (pinfunction "PA13_72") (pintype "bidirectional"))
    )
    (net (code "24") (name "FMU-SWO") (class "Default")
      (node (ref "JX301") (pin "6") (pinfunction "S_6") (pintype "passive"))
      (node (ref "U101") (pin "89") (pinfunction "PB3_89") (pintype "bidirectional"))
    )
    (net (code "25") (name "FMU-UART4_RX") (class "Default")
      (node (ref "U101") (pin "24") (pinfunction "PA1_24") (pintype "bidirectional"))
      (node (ref "U202") (pin "8") (pinfunction "A7_8") (pintype "bidirectional"))
    )
    (net (code "26") (name "FMU-UART4_TX") (class "Default")
      (node (ref "U101") (pin "23") (pinfunction "PA0_23") (pintype "bidirectional"))
      (node (ref "U202") (pin "9") (pinfunction "A8_9") (pintype "bidirectional"))
    )
    (net (code "27") (name "FMU-UART7_RX") (class "Default")
      (node (ref "U101") (pin "38") (pinfunction "PE7_38") (pintype "bidirectional"))
      (node (ref "U202") (pin "4") (pinfunction "A3_4") (pintype "bidirectional"))
    )
    (net (code "28") (name "FMU-UART7_TX") (class "Default")
      (node (ref "U101") (pin "39") (pinfunction "PE8_39") (pintype "bidirectional"))
      (node (ref "U202") (pin "5") (pinfunction "A4_5") (pintype "bidirectional"))
    )
    (net (code "29") (name "FMU-UART8_RX") (class "Default")
      (node (ref "U101") (pin "97") (pinfunction "PE0_97") (pintype "bidirectional"))
      (node (ref "U202") (pin "6") (pinfunction "A5_6") (pintype "bidirectional"))
    )
    (net (code "30") (name "FMU-UART8_TX") (class "Default")
      (node (ref "U101") (pin "98") (pinfunction "PE1_98") (pintype "bidirectional"))
      (node (ref "U202") (pin "7") (pinfunction "A6_7") (pintype "bidirectional"))
    )
    (net (code "31") (name "FMU-USART2_CTS") (class "Default")
      (node (ref "U101") (pin "84") (pinfunction "PD3_84") (pintype "bidirectional"))
      (node (ref "U201") (pin "9") (pinfunction "A8_9") (pintype "bidirectional"))
    )
    (net (code "32") (name "FMU-USART2_RTS") (class "Default")
      (node (ref "U101") (pin "85") (pinfunction "PD4_85") (pintype "bidirectional"))
      (node (ref "U201") (pin "8") (pinfunction "A7_8") (pintype "bidirectional"))
    )
    (net (code "33") (name "FMU-USART2_RX") (class "Default")
      (node (ref "U101") (pin "87") (pinfunction "PD6_87") (pintype "bidirectional"))
      (node (ref "U201") (pin "6") (pinfunction "A5_6") (pintype "bidirectional"))
    )
    (net (code "34") (name "FMU-USART2_TX") (class "Default")
      (node (ref "U101") (pin "86") (pinfunction "PD5_86") (pintype "bidirectional"))
      (node (ref "U201") (pin "7") (pinfunction "A6_7") (pintype "bidirectional"))
    )
    (net (code "35") (name "FMU-USART3_CTS") (class "Default")
      (node (ref "U101") (pin "58") (pinfunction "PD11_58") (pintype "bidirectional"))
      (node (ref "U201") (pin "3") (pinfunction "A2_3") (pintype "bidirectional"))
    )
    (net (code "36") (name "FMU-USART3_RTS") (class "Default")
      (node (ref "U101") (pin "59") (pinfunction "PD12_59") (pintype "bidirectional"))
      (node (ref "U201") (pin "1") (pinfunction "A1_1") (pintype "bidirectional"))
    )
    (net (code "37") (name "FMU-USART3_RX") (class "Default")
      (node (ref "U101") (pin "56") (pinfunction "PD9_56") (pintype "bidirectional"))
      (node (ref "U201") (pin "4") (pinfunction "A3_4") (pintype "bidirectional"))
    )
    (net (code "38") (name "FMU-USART3_TX") (class "Default")
      (node (ref "U101") (pin "55") (pinfunction "PD8_55") (pintype "bidirectional"))
      (node (ref "U201") (pin "5") (pinfunction "A4_5") (pintype "bidirectional"))
    )
    (net (code "39") (name "FMU-VDD_3V3") (class "Default")
      (node (ref "C101") (pin "P$1") (pinfunction "1_P$1") (pintype "passive"))
      (node (ref "C201") (pin "P$1") (pinfunction "1_P$1") (pintype "passive"))
      (node (ref "C202") (pin "P$1") (pinfunction "1_P$1") (pintype "passive"))
      (node (ref "C402") (pin "P$1") (pinfunction "1_P$1") (pintype "passive"))
      (node (ref "C603") (pin "P$1") (pinfunction "1_P$1") (pintype "passive"))
      (node (ref "C604") (pin "P$1") (pinfunction "1_P$1") (pintype "passive"))
      (node (ref "C606") (pin "P$1") (pinfunction "1_P$1") (pintype "passive"))
      (node (ref "C607") (pin "P$1") (pinfunction "1_P$1") (pintype "passive"))
      (node (ref "C608") (pin "P$1") (pinfunction "1_P$1") (pintype "passive"))
      (node (ref "C610") (pin "P$1") (pinfunction "1_P$1") (pintype "passive"))
      (node (ref "C612") (pin "P$1") (pinfunction "1_P$1") (pintype "passive"))
      (node (ref "C616") (pin "P$1") (pinfunction "1_P$1") (pintype "passive"))
      (node (ref "C701") (pin "P$1") (pinfunction "1_P$1") (pintype "passive"))
      (node (ref "C902") (pin "P$1") (pinfunction "1_P$1") (pintype "passive"))
      (node (ref "D602") (pin "A") (pinfunction "A_A") (pintype "passive"))
      (node (ref "JX301") (pin "1") (pinfunction "S_1") (pintype "passive"))
      (node (ref "R301") (pin "P$2") (pinfunction "2_P$2") (pintype "passive"))
      (node (ref "R302") (pin "P$2") (pinfunction "2_P$2") (pintype "passive"))
      (node (ref "R303") (pin "P$2") (pinfunction "2_P$2") (pintype "passive"))
      (node (ref "R304") (pin "P$2") (pinfunction "2_P$2") (pintype "passive"))
      (node (ref "R305") (pin "P$2") (pinfunction "2_P$2") (pintype "passive"))
      (node (ref "R306") (pin "P$2") (pinfunction "2_P$2") (pintype "passive"))
      (node (ref "R307") (pin "P$2") (pinfunction "2_P$2") (pintype "passive"))
      (node (ref "R401") (pin "P$2") (pinfunction "2_P$2") (pintype "passive"))
      (node (ref "R402") (pin "P$2") (pinfunction "2_P$2") (pintype "passive"))
      (node (ref "R602") (pin "P$2") (pinfunction "2_P$2") (pintype "passive"))
      (node (ref "R604") (pin "P$2") (pinfunction "2_P$2") (pintype "passive"))
      (node (ref "U101") (pin "100") (pinfunction "VDD_100") (pintype "power_in"))
      (node (ref "U101") (pin "11") (pinfunction "VDD_11") (pintype "power_in"))
      (node (ref "U101") (pin "19") (pinfunction "VDD_19") (pintype "power_in"))
      (node (ref "U101") (pin "21") (pinfunction "VREF+_21") (pintype "input"))
      (node (ref "U101") (pin "22") (pinfunction "VDDA_22") (pintype "power_in"))
      (node (ref "U101") (pin "28") (pinfunction "VDD_28") (pintype "power_in"))
      (node (ref "U101") (pin "50") (pinfunction "VDD_50") (pintype "power_in"))
      (node (ref "U101") (pin "75") (pinfunction "VDD_75") (pintype "power_in"))
      (node (ref "U102") (pin "3") (pinfunction "~{W}_3") (pintype "bidirectional"))
      (node (ref "U102") (pin "7") (pinfunction "~{HOLD}_7") (pintype "bidirectional"))
      (node (ref "U102") (pin "8") (pinfunction "VDD_8") (pintype "bidirectional"))
      (node (ref "U201") (pin "10") (pinfunction "OE_10") (pintype "input"))
      (node (ref "U201") (pin "19") (pinfunction "VCCB_19") (pintype "input"))
      (node (ref "U201") (pin "2") (pinfunction "VCCA_2") (pintype "input"))
      (node (ref "U202") (pin "10") (pinfunction "OE_10") (pintype "input"))
      (node (ref "U202") (pin "19") (pinfunction "VCCB_19") (pintype "input"))
      (node (ref "U202") (pin "2") (pinfunction "VCCA_2") (pintype "input"))
      (node (ref "U301") (pin "4") (pinfunction "VCC_4") (pintype "passive"))
      (node (ref "U401") (pin "3") (pinfunction "VCC_3") (pintype "input"))
      (node (ref "U603") (pin "7") (pinfunction "VOUT2_7") (pintype "bidirectional"))
      (node (ref "U701") (pin "1") (pinfunction "~{SHDN}_1") (pintype "input"))
      (node (ref "U701") (pin "10") (pinfunction "VIN_10") (pintype "power_in"))
      (node (ref "U901") (pin "10") (pinfunction "OE_10") (pintype "input"))
      (node (ref "U901") (pin "19") (pinfunction "VCCB_19") (pintype "input"))
      (node (ref "U901") (pin "2") (pinfunction "VCCA_2") (pintype "input"))
      (node (ref "VDD_3V1101") (pin "P$1") (pinfunction "P$1_P$1") (pintype "passive"))
    )
    (net (code "40") (name "FMU-~{RESET}") (class "Default")
      (node (ref "C609") (pin "P$2") (pinfunction "2_P$2") (pintype "passive"))
      (node (ref "R635") (pin "P$1") (pinfunction "1_P$1") (pintype "passive"))
      (node (ref "S601") (pin "A1") (pinfunction "1_A1") (pintype "passive"))
      (node (ref "U101") (pin "14") (pinfunction "NRST_14") (pintype "input"))
      (node (ref "U603") (pin "3") (pinfunction "POR2_3") (pintype "bidirectional"))
      (node (ref "U701") (pin "4") (pinfunction "~{RESET}_4") (pintype "input"))
    )
    (net (code "41") (name "FMU_AUX_ADC1") (class "Default")
      (node (ref "R408") (pin "P$1") (pinfunction "1_P$1") (pintype "passive"))
      (node (ref "U101") (pin "18") (pinfunction "PC3_18") (pintype "bidirectional"))
    )
    (net (code "42") (name "FMU_AUX_ADC2") (class "Default")
      (node (ref "R407") (pin "P$1") (pinfunction "1_P$1") (pintype "passive"))
      (node (ref "U101") (pin "33") (pinfunction "PC4_33") (pintype "bidirectional"))
    )
    (net (code "43") (name "FRAM_MISO") (class "Default")
      (node (ref "U101") (pin "53") (pinfunction "PB14_53") (pintype "bidirectional"))
      (node (ref "U102") (pin "2") (pinfunction "Q_2") (pintype "bidirectional"))
    )
    (net (code "44") (name "FRAM_MOSI") (class "Default")
      (node (ref "U101") (pin "54") (pinfunction "PB15_54") (pintype "bidirectional"))
      (node (ref "U102") (pin "5") (pinfunction "D_5") (pintype "bidirectional"))
    )
    (net (code "45") (name "FRAM_SCK") (class "Default")
      (node (ref "U101") (pin "52") (pinfunction "PB13_52") (pintype "bidirectional"))
      (node (ref "U102") (pin "6") (pinfunction "C_6") (pintype "bidirectional"))
    )
    (net (code "46") (name "GND") (class "Default")
      (node (ref "B601") (pin "2") (pinfunction "NEG_2") (pintype "bidirectional"))
      (node (ref "C1001") (pin "P$2") (pinfunction "2_P$2") (pintype "passive"))
      (node (ref "C1002") (pin "P$2") (pinfunction "2_P$2") (pintype "passive"))
      (node (ref "C1003") (pin "P$2") (pinfunction "2_P$2") (pintype "passive"))
      (node (ref "C1004") (pin "P$2") (pinfunction "2_P$2") (pintype "passive"))
      (node (ref "C1005") (pin "P$2") (pinfunction "2_P$2") (pintype "passive"))
      (node (ref "C1008") (pin "P$2") (pinfunction "2_P$2") (pintype "passive"))
      (node (ref "C101") (pin "P$2") (pinfunction "2_P$2") (pintype "passive"))
      (node (ref "C102") (pin "P$2") (pinfunction "2_P$2") (pintype "passive"))
      (node (ref "C103") (pin "P$1") (pinfunction "1_P$1") (pintype "passive"))
      (node (ref "C1101") (pin "P$2") (pinfunction "2_P$2") (pintype "passive"))
      (node (ref "C1102") (pin "P$2") (pinfunction "2_P$2") (pintype "passive"))
      (node (ref "C1103") (pin "P$2") (pinfunction "2_P$2") (pintype "passive"))
      (node (ref "C1104") (pin "P$2") (pinfunction "2_P$2") (pintype "passive"))
      (node (ref "C1105") (pin "P$2") (pinfunction "2_P$2") (pintype "passive"))
      (node (ref "C1106") (pin "P$2") (pinfunction "2_P$2") (pintype "passive"))
      (node (ref "C1107") (pin "P$2") (pinfunction "2_P$2") (pintype "passive"))
      (node (ref "C1108") (pin "P$2") (pinfunction "2_P$2") (pintype "passive"))
      (node (ref "C1109") (pin "P$2") (pinfunction "2_P$2") (pintype "passive"))
      (node (ref "C1110") (pin "P$2") (pinfunction "2_P$2") (pintype "passive"))
      (node (ref "C201") (pin "P$2") (pinfunction "2_P$2") (pintype "passive"))
      (node (ref "C202") (pin "P$2") (pinfunction "2_P$2") (pintype "passive"))
      (node (ref "C401") (pin "P$2") (pinfunction "2_P$2") (pintype "passive"))
      (node (ref "C402") (pin "P$2") (pinfunction "2_P$2") (pintype "passive"))
      (node (ref "C501") (pin "P$2") (pinfunction "2_P$2") (pintype "passive"))
      (node (ref "C502") (pin "P$2") (pinfunction "2_P$2") (pintype "passive"))
      (node (ref "C503") (pin "P$2") (pinfunction "2_P$2") (pintype "passive"))
      (node (ref "C504") (pin "P$2") (pinfunction "2_P$2") (pintype "passive"))
      (node (ref "C505") (pin "P$2") (pinfunction "2_P$2") (pintype "passive"))
      (node (ref "C506") (pin "P$2") (pinfunction "2_P$2") (pintype "passive"))
      (node (ref "C507") (pin "P$2") (pinfunction "2_P$2") (pintype "passive"))
      (node (ref "C508") (pin "P$2") (pinfunction "2_P$2") (pintype "passive"))
      (node (ref "C509") (pin "P$2") (pinfunction "2_P$2") (pintype "passive"))
      (node (ref "C511") (pin "P$2") (pinfunction "2_P$2") (pintype "passive"))
      (node (ref "C512") (pin "P$2") (pinfunction "2_P$2") (pintype "passive"))
      (node (ref "C513") (pin "P$2") (pinfunction "2_P$2") (pintype "passive"))
      (node (ref "C514") (pin "P$2") (pinfunction "2_P$2") (pintype "passive"))
      (node (ref "C515") (pin "P$2") (pinfunction "2_P$2") (pintype "passive"))
      (node (ref "C601") (pin "P$2") (pinfunction "2_P$2") (pintype "passive"))
      (node (ref "C602") (pin "P$1") (pinfunction "1_P$1") (pintype "passive"))
      (node (ref "C603") (pin "P$2") (pinfunction "2_P$2") (pintype "passive"))
      (node (ref "C604") (pin "P$2") (pinfunction "2_P$2") (pintype "passive"))
      (node (ref "C605") (pin "P$2") (pinfunction "2_P$2") (pintype "passive"))
      (node (ref "C606") (pin "P$2") (pinfunction "2_P$2") (pintype "passive"))
      (node (ref "C607") (pin "P$2") (pinfunction "2_P$2") (pintype "passive"))
      (node (ref "C608") (pin "P$2") (pinfunction "2_P$2") (pintype "passive"))
      (node (ref "C609") (pin "P$1") (pinfunction "1_P$1") (pintype "passive"))
      (node (ref "C610") (pin "P$2") (pinfunction "2_P$2") (pintype "passive"))
      (node (ref "C611") (pin "P$2") (pinfunction "2_P$2") (pintype "passive"))
      (node (ref "C612") (pin "P$2") (pinfunction "2_P$2") (pintype "passive"))
      (node (ref "C613") (pin "P$2") (pinfunction "2_P$2") (pintype "passive"))
      (node (ref "C614") (pin "P$2") (pinfunction "2_P$2") (pintype "passive"))
      (node (ref "C615") (pin "P$2") (pinfunction "2_P$2") (pintype "passive"))
      (node (ref "C616") (pin "P$2") (pinfunction "2_P$2") (pintype "passive"))
      (node (ref "C617") (pin "P$2") (pinfunction "2_P$2") (pintype "passive"))
      (node (ref "C618") (pin "P$2") (pinfunction "2_P$2") (pintype "passive"))
      (node (ref "C701") (pin "P$2") (pinfunction "2_P$2") (pintype "passive"))
      (node (ref "C702") (pin "P$2") (pinfunction "2_P$2") (pintype "passive"))
      (node (ref "C703") (pin "P$2") (pinfunction "2_P$2") (pintype "passive"))
      (node (ref "C704") (pin "P$2") (pinfunction "2_P$2") (pintype "passive"))
      (node (ref "C801") (pin "P$1") (pinfunction "1_P$1") (pintype "passive"))
      (node (ref "C802") (pin "P$2") (pinfunction "2_P$2") (pintype "passive"))
      (node (ref "C803") (pin "P$2") (pinfunction "2_P$2") (pintype "passive"))
      (node (ref "C804") (pin "P$2") (pinfunction "2_P$2") (pintype "passive"))
      (node (ref "C805") (pin "P$2") (pinfunction "2_P$2") (pintype "passive"))
      (node (ref "C806") (pin "P$1") (pinfunction "1_P$1") (pintype "passive"))
      (node (ref "C901") (pin "P$2") (pinfunction "2_P$2") (pintype "passive"))
      (node (ref "C902") (pin "P$2") (pinfunction "2_P$2") (pintype "passive"))
      (node (ref "C903") (pin "P$2") (pinfunction "2_P$2") (pintype "passive"))
      (node (ref "D201") (pin "A") (pinfunction "A_A") (pintype "passive"))
      (node (ref "D202") (pin "A") (pinfunction "A_A") (pintype "passive"))
      (node (ref "D203") (pin "A") (pinfunction "A_A") (pintype "passive"))
      (node (ref "D401") (pin "A") (pinfunction "A_A") (pintype "passive"))
      (node (ref "D402") (pin "A") (pinfunction "A_A") (pintype "passive"))
      (node (ref "D403") (pin "A") (pinfunction "A_A") (pintype "passive"))
      (node (ref "D404") (pin "A") (pinfunction "A_A") (pintype "passive"))
      (node (ref "D701") (pin "A") (pinfunction "A_A") (pintype "passive"))
      (node (ref "D801") (pin "A") (pinfunction "A_A") (pintype "passive"))
      (node (ref "D901") (pin "A") (pinfunction "A_A") (pintype "passive"))
      (node (ref "D902") (pin "A") (pinfunction "A_A") (pintype "passive"))
      (node (ref "D903") (pin "A") (pinfunction "A_A") (pintype "passive"))
      (node (ref "GND") (pin "P$1") (pinfunction "P$1_P$1") (pintype "passive"))
      (node (ref "GND.") (pin "P$1") (pinfunction "P$1_P$1") (pintype "passive"))
      (node (ref "J201") (pin "6") (pinfunction "6_6") (pintype "passive"))
      (node (ref "J202") (pin "6") (pinfunction "6_6") (pintype "passive"))
      (node (ref "J203") (pin "6") (pinfunction "6_6") (pintype "passive"))
      (node (ref "J204") (pin "6") (pinfunction "6_6") (pintype "passive"))
      (node (ref "J301") (pin "GND") (pinfunction "5_GND") (pintype "power_in"))
      (node (ref "J301") (pin "GND1") (pinfunction "GND1_GND1") (pintype "bidirectional"))
      (node (ref "J301") (pin "GND2") (pinfunction "GND2_GND2") (pintype "bidirectional"))
      (node (ref "J301") (pin "GND3") (pinfunction "GND3_GND3") (pintype "bidirectional"))
      (node (ref "J301") (pin "GND4") (pinfunction "GND4_GND4") (pintype "bidirectional"))
      (node (ref "J302") (pin "4") (pinfunction "4_4") (pintype "passive"))
      (node (ref "J401") (pin "4") (pinfunction "4_4") (pintype "passive"))
      (node (ref "J402") (pin "3") (pinfunction "3_3") (pintype "passive"))
      (node (ref "J403") (pin "7") (pinfunction "7_7") (pintype "passive"))
      (node (ref "J404") (pin "3") (pinfunction "3_3") (pintype "passive"))
      (node (ref "J404") (pin "5") (pinfunction "5_5") (pintype "passive"))
      (node (ref "J405") (pin "4") (pinfunction "4_4") (pintype "passive"))
      (node (ref "J601") (pin "5") (pinfunction "5_5") (pintype "passive"))
      (node (ref "J601") (pin "6") (pinfunction "6_6") (pintype "passive"))
      (node (ref "J701") (pin "2") (pinfunction "2_2") (pintype "passive"))
      (node (ref "J801") (pin "P$2") (pinfunction "P$2_P$2") (pintype "bidirectional"))
      (node (ref "J901") (pin "12") (pinfunction "S_12") (pintype "passive"))
      (node (ref "J901") (pin "15") (pinfunction "S_15") (pintype "passive"))
      (node (ref "J901") (pin "18") (pinfunction "S_18") (pintype "passive"))
      (node (ref "J901") (pin "21") (pinfunction "S_21") (pintype "passive"))
      (node (ref "J901") (pin "24") (pinfunction "S_24") (pintype "passive"))
      (node (ref "J901") (pin "27") (pinfunction "S_27") (pintype "passive"))
      (node (ref "J901") (pin "3") (pinfunction "S_3") (pintype "passive"))
      (node (ref "J901") (pin "30") (pinfunction "S_30") (pintype "passive"))
      (node (ref "J901") (pin "33") (pinfunction "S_33") (pintype "passive"))
      (node (ref "J901") (pin "36") (pinfunction "S_36") (pintype "passive"))
      (node (ref "J901") (pin "39") (pinfunction "S_39") (pintype "passive"))
      (node (ref "J901") (pin "42") (pinfunction "S_42") (pintype "passive"))
      (node (ref "J901") (pin "45") (pinfunction "S_45") (pintype "passive"))
      (node (ref "J901") (pin "48") (pinfunction "S_48") (pintype "passive"))
      (node (ref "J901") (pin "6") (pinfunction "S_6") (pintype "passive"))
      (node (ref "J901") (pin "9") (pinfunction "S_9") (pintype "passive"))
      (node (ref "JX301") (pin "3") (pinfunction "S_3") (pintype "passive"))
      (node (ref "JX301") (pin "5") (pinfunction "S_5") (pintype "passive"))
      (node (ref "JX301") (pin "9") (pinfunction "S_9") (pintype "passive"))
      (node (ref "JX801") (pin "3") (pinfunction "GND_3") (pintype "bidirectional"))
      (node (ref "JX802") (pin "3") (pinfunction "S_3") (pintype "passive"))
      (node (ref "JX802") (pin "5") (pinfunction "S_5") (pintype "passive"))
      (node (ref "JX802") (pin "9") (pinfunction "S_9") (pintype "passive"))
      (node (ref "L1101") (pin "P$3") (pinfunction "P$3_P$3") (pintype "bidirectional"))
      (node (ref "L1101") (pin "P$4") (pinfunction "P$3_P$4") (pintype "bidirectional"))
      (node (ref "L1101") (pin "P$5") (pinfunction "P$3_P$5") (pintype "bidirectional"))
      (node (ref "L1102") (pin "P$3") (pinfunction "P$3_P$3") (pintype "bidirectional"))
      (node (ref "L1102") (pin "P$4") (pinfunction "P$3_P$4") (pintype "bidirectional"))
      (node (ref "L1102") (pin "P$5") (pinfunction "P$3_P$5") (pintype "bidirectional"))
      (node (ref "L201") (pin "P$3") (pinfunction "P$3_P$3") (pintype "bidirectional"))
      (node (ref "L201") (pin "P$4") (pinfunction "P$3_P$4") (pintype "bidirectional"))
      (node (ref "L201") (pin "P$5") (pinfunction "P$3_P$5") (pintype "bidirectional"))
      (node (ref "L202") (pin "P$3") (pinfunction "P$3_P$3") (pintype "bidirectional"))
      (node (ref "L202") (pin "P$4") (pinfunction "P$3_P$4") (pintype "bidirectional"))
      (node (ref "L202") (pin "P$5") (pinfunction "P$3_P$5") (pintype "bidirectional"))
      (node (ref "L203") (pin "P$3") (pinfunction "P$3_P$3") (pintype "bidirectional"))
      (node (ref "L203") (pin "P$4") (pinfunction "P$3_P$4") (pintype "bidirectional"))
      (node (ref "L203") (pin "P$5") (pinfunction "P$3_P$5") (pintype "bidirectional"))
      (node (ref "L401") (pin "P$3") (pinfunction "P$3_P$3") (pintype "bidirectional"))
      (node (ref "L401") (pin "P$4") (pinfunction "P$3_P$4") (pintype "bidirectional"))
      (node (ref "L401") (pin "P$5") (pinfunction "P$3_P$5") (pintype "bidirectional"))
      (node (ref "L402") (pin "P$3") (pinfunction "P$3_P$3") (pintype "bidirectional"))
      (node (ref "L402") (pin "P$4") (pinfunction "P$3_P$4") (pintype "bidirectional"))
      (node (ref "L402") (pin "P$5") (pinfunction "P$3_P$5") (pintype "bidirectional"))
      (node (ref "L403") (pin "P$3") (pinfunction "P$3_P$3") (pintype "bidirectional"))
      (node (ref "L403") (pin "P$4") (pinfunction "P$3_P$4") (pintype "bidirectional"))
      (node (ref "L403") (pin "P$5") (pinfunction "P$3_P$5") (pintype "bidirectional"))
      (node (ref "L404") (pin "P$3") (pinfunction "P$3_P$3") (pintype "bidirectional"))
      (node (ref "L404") (pin "P$4") (pinfunction "P$3_P$4") (pintype "bidirectional"))
      (node (ref "L404") (pin "P$5") (pinfunction "P$3_P$5") (pintype "bidirectional"))
      (node (ref "L603") (pin "P$3") (pinfunction "P$3_P$3") (pintype "bidirectional"))
      (node (ref "L603") (pin "P$4") (pinfunction "P$3_P$4") (pintype "bidirectional"))
      (node (ref "L603") (pin "P$5") (pinfunction "P$3_P$5") (pintype "bidirectional"))
      (node (ref "L901") (pin "P$3") (pinfunction "P$3_P$3") (pintype "bidirectional"))
      (node (ref "L901") (pin "P$4") (pinfunction "P$3_P$4") (pintype "bidirectional"))
      (node (ref "L901") (pin "P$5") (pinfunction "P$3_P$5") (pintype "bidirectional"))
      (node (ref "R1001") (pin "P$1") (pinfunction "1_P$1") (pintype "passive"))
      (node (ref "R1002") (pin "P$1") (pinfunction "1_P$1") (pintype "passive"))
      (node (ref "R102") (pin "P$2") (pinfunction "2_P$2") (pintype "passive"))
      (node (ref "R1103") (pin "P$2") (pinfunction "2_P$2") (pintype "passive"))
      (node (ref "R1104") (pin "P$2") (pinfunction "2_P$2") (pintype "passive"))
      (node (ref "R1107") (pin "P$2") (pinfunction "2_P$2") (pintype "passive"))
      (node (ref "R1111") (pin "P$2") (pinfunction "2_P$2") (pintype "passive"))
      (node (ref "R1114") (pin "P$2") (pinfunction "2_P$2") (pintype "passive"))
      (node (ref "R1115") (pin "P$1") (pinfunction "1_P$1") (pintype "passive"))
      (node (ref "R403") (pin "P$1") (pinfunction "1_P$1") (pintype "passive"))
      (node (ref "R610") (pin "P$2") (pinfunction "2_P$2") (pintype "passive"))
      (node (ref "R611") (pin "P$1") (pinfunction "1_P$1") (pintype "passive"))
      (node (ref "R615") (pin "P$2") (pinfunction "2_P$2") (pintype "passive"))
      (node (ref "R616") (pin "P$2") (pinfunction "2_P$2") (pintype "passive"))
      (node (ref "R617") (pin "P$2") (pinfunction "2_P$2") (pintype "passive"))
      (node (ref "R621") (pin "1") (pinfunction "1_1") (pintype "passive"))
      (node (ref "R702") (pin "P$2") (pinfunction "2_P$2") (pintype "passive"))
      (node (ref "R704") (pin "P$1") (pinfunction "1_P$1") (pintype "passive"))
      (node (ref "R706") (pin "P$2") (pinfunction "2_P$2") (pintype "passive"))
      (node (ref "R708") (pin "P$1") (pinfunction "1_P$1") (pintype "passive"))
      (node (ref "R711") (pin "P$1") (pinfunction "1_P$1") (pintype "passive"))
      (node (ref "R713") (pin "P$2") (pinfunction "2_P$2") (pintype "passive"))
      (node (ref "R801") (pin "P$2") (pinfunction "2_P$2") (pintype "passive"))
      (node (ref "R802") (pin "P$2") (pinfunction "2_P$2") (pintype "passive"))
      (node (ref "R919") (pin "P$1") (pinfunction "1_P$1") (pintype "passive"))
      (node (ref "S601") (pin "B3") (pinfunction "2_B3") (pintype "passive"))
      (node (ref "S801") (pin "B3") (pinfunction "2_B3") (pintype "passive"))
      (node (ref "U1001") (pin "2") (pinfunction "VSS_2") (pintype "bidirectional"))
      (node (ref "U1001") (pin "5") (pinfunction "~{CE}_5") (pintype "bidirectional"))
      (node (ref "U1001") (pin "6") (pinfunction "VBAT_6") (pintype "bidirectional"))
      (node (ref "U1001") (pin "GND") (pinfunction "VSS_GND") (pintype "bidirectional"))
      (node (ref "U1001") (pin "P$2") (pinfunction "VSS_P$2") (pintype "bidirectional"))
      (node (ref "U1001") (pin "P$3") (pinfunction "VSS_P$3") (pintype "bidirectional"))
      (node (ref "U1002") (pin "2") (pinfunction "GND_2") (pintype "bidirectional"))
      (node (ref "U1002") (pin "GND") (pinfunction "GND_GND") (pintype "bidirectional"))
      (node (ref "U101") (pin "10") (pinfunction "VSS_10") (pintype "power_in"))
      (node (ref "U101") (pin "20") (pinfunction "VSSA_20") (pintype "power_in"))
      (node (ref "U101") (pin "27") (pinfunction "VSS_27") (pintype "power_in"))
      (node (ref "U101") (pin "74") (pinfunction "VSS_74") (pintype "power_in"))
      (node (ref "U101") (pin "99") (pinfunction "VSS_99") (pintype "power_in"))
      (node (ref "U102") (pin "4") (pinfunction "VSS_4") (pintype "bidirectional"))
      (node (ref "U1101") (pin "P$10") (pinfunction "GND_P$10") (pintype "bidirectional"))
      (node (ref "U1101") (pin "P$25") (pinfunction "GND_P$25") (pintype "bidirectional"))
      (node (ref "U201") (pin "11") (pinfunction "GND_11") (pintype "power_in"))
      (node (ref "U202") (pin "11") (pinfunction "GND_11") (pintype "power_in"))
      (node (ref "U301") (pin "6") (pinfunction "GND_6") (pintype "power_in"))
      (node (ref "U302") (pin "2") (pinfunction "GND_2") (pintype "bidirectional"))
      (node (ref "U401") (pin "2") (pinfunction "GND_2") (pintype "power_in"))
      (node (ref "U401") (pin "5") (pinfunction "SHDN_5") (pintype "input"))
      (node (ref "U401") (pin "8") (pinfunction "RS_8") (pintype "input"))
      (node (ref "U501") (pin "10") (pinfunction "RES_P10_GND_10") (pintype "bidirectional"))
      (node (ref "U501") (pin "11") (pinfunction "RES_P11_GND_11") (pintype "bidirectional"))
      (node (ref "U501") (pin "12") (pinfunction "RES_P12_GND_12") (pintype "bidirectional"))
      (node (ref "U501") (pin "13") (pinfunction "GND_13") (pintype "bidirectional"))
      (node (ref "U501") (pin "8") (pinfunction "RES_P8_GND_8") (pintype "bidirectional"))
      (node (ref "U501") (pin "9") (pinfunction "RES_P9_GND_9") (pintype "bidirectional"))
      (node (ref "U502") (pin "10") (pinfunction "GND_10") (pintype "bidirectional"))
      (node (ref "U502") (pin "11") (pinfunction "GND_11") (pintype "bidirectional"))
      (node (ref "U502") (pin "12") (pinfunction "GND_12") (pintype "bidirectional"))
      (node (ref "U502") (pin "13") (pinfunction "GND_13") (pintype "bidirectional"))
      (node (ref "U502") (pin "9") (pinfunction "GND_9") (pintype "bidirectional"))
      (node (ref "U504") (pin "10") (pinfunction "RSRV_10") (pintype "bidirectional"))
      (node (ref "U504") (pin "12") (pinfunction "GND_12") (pintype "bidirectional"))
      (node (ref "U504") (pin "13") (pinfunction "GND_13") (pintype "bidirectional"))
      (node (ref "U504") (pin "16") (pinfunction "GND_16") (pintype "bidirectional"))
      (node (ref "U504") (pin "5") (pinfunction "GND_5") (pintype "bidirectional"))
      (node (ref "U505") (pin "1") (pinfunction "CLKIN_1") (pintype "bidirectional"))
      (node (ref "U505") (pin "18") (pinfunction "GND_18") (pintype "bidirectional"))
      (node (ref "U506") (pin "2") (pinfunction "PS_2") (pintype "bidirectional"))
      (node (ref "U506") (pin "3") (pinfunction "GND_3") (pintype "bidirectional"))
      (node (ref "U601") (pin "2") (pinfunction "VSS_2") (pintype "bidirectional"))
      (node (ref "U601") (pin "6") (pinfunction "VBAT_6") (pintype "bidirectional"))
      (node (ref "U601") (pin "GND") (pinfunction "VSS_GND") (pintype "bidirectional"))
      (node (ref "U601") (pin "P$2") (pinfunction "VSS_P$2") (pintype "bidirectional"))
      (node (ref "U601") (pin "P$3") (pinfunction "VSS_P$3") (pintype "bidirectional"))
      (node (ref "U602") (pin "2") (pinfunction "VSS_2") (pintype "bidirectional"))
      (node (ref "U602") (pin "6") (pinfunction "VBAT_6") (pintype "bidirectional"))
      (node (ref "U602") (pin "GND") (pinfunction "VSS_GND") (pintype "bidirectional"))
      (node (ref "U602") (pin "P$2") (pinfunction "VSS_P$2") (pintype "bidirectional"))
      (node (ref "U602") (pin "P$3") (pinfunction "VSS_P$3") (pintype "bidirectional"))
      (node (ref "U603") (pin "2") (pinfunction "GND_2") (pintype "bidirectional"))
      (node (ref "U603") (pin "GND") (pinfunction "GND_GND") (pintype "bidirectional"))
      (node (ref "U701") (pin "5") (pinfunction "GND_5") (pintype "power_in"))
      (node (ref "U702") (pin "4") (pinfunction "GND_4") (pintype "power_in"))
      (node (ref "U801") (pin "23") (pinfunction "VSS_1_23") (pintype "power_in"))
      (node (ref "U801") (pin "35") (pinfunction "VSS_2_35") (pintype "power_in"))
      (node (ref "U801") (pin "47") (pinfunction "VSS_3_47") (pintype "power_in"))
      (node (ref "U801") (pin "8") (pinfunction "VSSA_8") (pintype "power_in"))
      (node (ref "U901") (pin "11") (pinfunction "GND_11") (pintype "power_in"))
      (node (ref "U902") (pin "11") (pinfunction "GND_11") (pintype "power_in"))
      (node (ref "U903") (pin "1") (pinfunction "~{1OE}_1") (pintype "input"))
      (node (ref "U903") (pin "4") (pinfunction "GND_4") (pintype "power_in"))
      (node (ref "X101") (pin "2") (pinfunction "NC_2_2") (pintype "power_in"))
      (node (ref "X101") (pin "4") (pinfunction "NC_4_4") (pintype "power_in"))
      (node (ref "X503") (pin "2") (pinfunction "S_2") (pintype "passive"))
      (node (ref "X801") (pin "2") (pinfunction "NC_2_2") (pintype "power_in"))
      (node (ref "X801") (pin "4") (pinfunction "NC_4_4") (pintype "power_in"))
    )
    (net (code "47") (name "GPIO_EXT_1") (class "Default")
      (node (ref "J403") (pin "6") (pinfunction "6_6") (pintype "passive"))
      (node (ref "U101") (pin "8") (pinfunction "PC14_8") (pintype "bidirectional"))
    )
    (net (code "48") (name "GYRO_DRDY") (class "Default")
      (node (ref "U101") (pin "35") (pinfunction "PB0_35") (pintype "bidirectional"))
      (node (ref "U501") (pin "6") (pinfunction "DRDY/INT2_6") (pintype "output"))
      (node (ref "U502") (pin "6") (pinfunction "DRDY/INT2_6") (pintype "bidirectional"))
      (node (ref "X503") (pin "5") (pinfunction "S_5") (pintype "passive"))
    )
    (net (code "49") (name "IO-BOOT0") (class "Default")
      (node (ref "IO-BOOT1101") (pin "P$1") (pinfunction "P$1_P$1") (pintype "passive"))
      (node (ref "R801") (pin "P$1") (pinfunction "1_P$1") (pintype "passive"))
      (node (ref "U801") (pin "44") (pinfunction "BOOT0_44") (pintype "input"))
    )
    (net (code "50") (name "IO-CH1") (class "Default")
      (node (ref "U801") (pin "10") (pinfunction "PA0_10") (pintype "bidirectional"))
      (node (ref "U902") (pin "9") (pinfunction "A8_9") (pintype "bidirectional"))
    )
    (net (code "51") (name "IO-CH2") (class "Default")
      (node (ref "U801") (pin "11") (pinfunction "PA1_11") (pintype "bidirectional"))
      (node (ref "U902") (pin "8") (pinfunction "A7_8") (pintype "bidirectional"))
    )
    (net (code "52") (name "IO-CH3") (class "Default")
      (node (ref "U801") (pin "45") (pinfunction "PB8_45") (pintype "bidirectional"))
      (node (ref "U902") (pin "7") (pinfunction "A6_7") (pintype "bidirectional"))
    )
    (net (code "53") (name "IO-CH4") (class "Default")
      (node (ref "U801") (pin "46") (pinfunction "PB9_46") (pintype "bidirectional"))
      (node (ref "U902") (pin "6") (pinfunction "A5_6") (pintype "bidirectional"))
    )
    (net (code "54") (name "IO-CH5") (class "Default")
      (node (ref "U801") (pin "16") (pinfunction "PA6_16") (pintype "bidirectional"))
      (node (ref "U902") (pin "5") (pinfunction "A4_5") (pintype "bidirectional"))
    )
    (net (code "55") (name "IO-CH6") (class "Default")
      (node (ref "U801") (pin "17") (pinfunction "PA7_17") (pintype "bidirectional"))
      (node (ref "U902") (pin "4") (pinfunction "A3_4") (pintype "bidirectional"))
    )
    (net (code "56") (name "IO-CH7") (class "Default")
      (node (ref "U801") (pin "18") (pinfunction "PB0_18") (pintype "bidirectional"))
      (node (ref "U902") (pin "3") (pinfunction "A2_3") (pintype "bidirectional"))
    )
    (net (code "57") (name "IO-CH8") (class "Default")
      (node (ref "U801") (pin "19") (pinfunction "PB1_19") (pintype "bidirectional"))
      (node (ref "U902") (pin "1") (pinfunction "A1_1") (pintype "bidirectional"))
    )
    (net (code "58") (name "IO-SWCLK") (class "Default")
      (node (ref "JX802") (pin "4") (pinfunction "S_4") (pintype "passive"))
      (node (ref "U801") (pin "37") (pinfunction "PA14_37") (pintype "bidirectional"))
    )
    (net (code "59") (name "IO-SWDIO") (class "Default")
      (node (ref "JX802") (pin "2") (pinfunction "S_2") (pintype "passive"))
      (node (ref "U801") (pin "34") (pinfunction "PA13_34") (pintype "bidirectional"))
    )
    (net (code "60") (name "IO-SWO") (class "Default")
      (node (ref "JX802") (pin "6") (pinfunction "S_6") (pintype "passive"))
      (node (ref "U801") (pin "39") (pinfunction "PB3_39") (pintype "bidirectional"))
    )
    (net (code "61") (name "IO-USART1_RX") (class "Default")
      (node (ref "J801") (pin "P$3") (pinfunction "P$3_P$3") (pintype "bidirectional"))
      (node (ref "JX801") (pin "2") (pinfunction "+5V_2") (pintype "bidirectional"))
      (node (ref "U801") (pin "31") (pinfunction "PA10_31") (pintype "bidirectional"))
    )
    (net (code "62") (name "IO-USART1_TX") (class "Default")
      (node (ref "JX801") (pin "1") (pinfunction "PPM_1") (pintype "bidirectional"))
      (node (ref "R101") (pin "P$2") (pinfunction "2_P$2") (pintype "passive"))
      (node (ref "U801") (pin "30") (pinfunction "PA9_30") (pintype "bidirectional"))
    )
    (net (code "63") (name "IO-VDD_3V3") (class "Default")
      (node (ref "C1003") (pin "P$1") (pinfunction "1_P$1") (pintype "passive"))
      (node (ref "C1004") (pin "P$1") (pinfunction "1_P$1") (pintype "passive"))
      (node (ref "C802") (pin "P$1") (pinfunction "1_P$1") (pintype "passive"))
      (node (ref "C803") (pin "P$1") (pinfunction "1_P$1") (pintype "passive"))
      (node (ref "C804") (pin "P$1") (pinfunction "1_P$1") (pintype "passive"))
      (node (ref "C901") (pin "P$1") (pinfunction "1_P$1") (pintype "passive"))
      (node (ref "C903") (pin "P$1") (pinfunction "1_P$1") (pintype "passive"))
      (node (ref "D701") (pin "C") (pinfunction "C_C") (pintype "passive"))
      (node (ref "J702") (pin "1") (pinfunction "1_1") (pintype "passive"))
      (node (ref "JX802") (pin "1") (pinfunction "S_1") (pintype "passive"))
      (node (ref "U1002") (pin "7") (pinfunction "VOUT2_7") (pintype "bidirectional"))
      (node (ref "U801") (pin "24") (pinfunction "VDD_1_24") (pintype "power_in"))
      (node (ref "U801") (pin "36") (pinfunction "VDD_2_36") (pintype "power_in"))
      (node (ref "U801") (pin "48") (pinfunction "VDD_3_48") (pintype "power_in"))
      (node (ref "U801") (pin "9") (pinfunction "VDDA_9") (pintype "power_in"))
      (node (ref "U902") (pin "10") (pinfunction "OE_10") (pintype "input"))
      (node (ref "U902") (pin "19") (pinfunction "VCCB_19") (pintype "input"))
      (node (ref "U902") (pin "2") (pinfunction "VCCA_2") (pintype "input"))
      (node (ref "U903") (pin "8") (pinfunction "VCC_8") (pintype "power_in"))
    )
    (net (code "64") (name "IO-VDD_5V5") (class "Default")
      (node (ref "C1001") (pin "P$1") (pinfunction "1_P$1") (pintype "passive"))
      (node (ref "C1005") (pin "P$1") (pinfunction "1_P$1") (pintype "passive"))
      (node (ref "D1001") (pin "3") (pinfunction "CC_3") (pintype "passive"))
      (node (ref "LED702") (pin "A") (pinfunction "A_A") (pintype "passive"))
      (node (ref "LED703") (pin "A") (pinfunction "A_A") (pintype "passive"))
      (node (ref "LED705") (pin "A") (pinfunction "A_A") (pintype "passive"))
      (node (ref "U1002") (pin "1") (pinfunction "VIN_1") (pintype "bidirectional"))
      (node (ref "U1002") (pin "4") (pinfunction "EN2_4") (pintype "bidirectional"))
    )
    (net (code "65") (name "IO-~{RESET}") (class "Default")
      (node (ref "C801") (pin "P$2") (pinfunction "2_P$2") (pintype "passive"))
      (node (ref "S801") (pin "A1") (pinfunction "1_A1") (pintype "passive"))
      (node (ref "U1002") (pin "3") (pinfunction "POR2_3") (pintype "bidirectional"))
      (node (ref "U801") (pin "7") (pinfunction "NRST_7") (pintype "input"))
    )
    (net (code "66") (name "IO-~{VDD_SERVO_IN_FAULT}") (class "Default")
      (node (ref "U1001") (pin "4") (pinfunction "~{FAULT}_4") (pintype "bidirectional"))
      (node (ref "U801") (pin "38") (pinfunction "PA15_38") (pintype "bidirectional"))
    )
    (net (code "67") (name "MAG_DRDY") (class "Default")
      (node (ref "U101") (pin "36") (pinfunction "PB1_36") (pintype "bidirectional"))
      (node (ref "U504") (pin "9") (pinfunction "INT2_9") (pintype "bidirectional"))
      (node (ref "X503") (pin "4") (pinfunction "S_4") (pintype "passive"))
    )
    (net (code "68") (name "MPU_DRDY") (class "Default")
      (node (ref "U101") (pin "62") (pinfunction "PD15_62") (pintype "bidirectional"))
      (node (ref "U505") (pin "12") (pinfunction "INT_12") (pintype "bidirectional"))
    )
    (net (code "69") (name "Net-(C102-1)") (class "Default")
      (node (ref "C102") (pin "P$1") (pinfunction "1_P$1") (pintype "passive"))
      (node (ref "U101") (pin "12") (pinfunction "OSC_IN_12") (pintype "input"))
      (node (ref "X101") (pin "3") (pinfunction "3_3") (pintype "bidirectional"))
    )
    (net (code "70") (name "Net-(C103-2)") (class "Default")
      (node (ref "C103") (pin "P$2") (pinfunction "2_P$2") (pintype "passive"))
      (node (ref "U101") (pin "13") (pinfunction "OSC_OUT_13") (pintype "output"))
      (node (ref "X101") (pin "1") (pinfunction "1_1") (pintype "bidirectional"))
    )
    (net (code "71") (name "Net-(C504-1)") (class "Default")
      (node (ref "C504") (pin "P$1") (pinfunction "1_P$1") (pintype "passive"))
      (node (ref "U501") (pin "14") (pinfunction "PLLFILT_14") (pintype "bidirectional"))
    )
    (net (code "72") (name "Net-(C505-1)") (class "Default")
      (node (ref "C505") (pin "P$1") (pinfunction "1_P$1") (pintype "passive"))
      (node (ref "U502") (pin "14") (pinfunction "CAP_14") (pintype "bidirectional"))
    )
    (net (code "73") (name "Net-(C509-1)") (class "Default")
      (node (ref "C509") (pin "P$1") (pinfunction "1_P$1") (pintype "passive"))
      (node (ref "U504") (pin "15") (pinfunction "C1_15") (pintype "bidirectional"))
    )
    (net (code "74") (name "Net-(C510-1)") (class "Default")
      (node (ref "C510") (pin "P$1") (pinfunction "1_P$1") (pintype "passive"))
      (node (ref "U504") (pin "2") (pinfunction "SETC_2") (pintype "bidirectional"))
    )
    (net (code "75") (name "Net-(C510-2)") (class "Default")
      (node (ref "C510") (pin "P$2") (pinfunction "2_P$2") (pintype "passive"))
      (node (ref "U504") (pin "3") (pinfunction "SETP_3") (pintype "bidirectional"))
    )
    (net (code "76") (name "Net-(C512-1)") (class "Default")
      (node (ref "C512") (pin "P$1") (pinfunction "1_P$1") (pintype "passive"))
      (node (ref "U505") (pin "10") (pinfunction "REGOUT_10") (pintype "bidirectional"))
    )
    (net (code "77") (name "Net-(C515-1)") (class "Default")
      (node (ref "C515") (pin "P$1") (pinfunction "1_P$1") (pintype "passive"))
      (node (ref "U505") (pin "20") (pinfunction "CPOUT_20") (pintype "bidirectional"))
    )
    (net (code "78") (name "Net-(C601-1)") (class "Default")
      (node (ref "C601") (pin "P$1") (pinfunction "1_P$1") (pintype "passive"))
      (node (ref "C615") (pin "P$1") (pinfunction "1_P$1") (pintype "passive"))
      (node (ref "L603") (pin "P$2") (pinfunction "P$2_P$2") (pintype "bidirectional"))
      (node (ref "R603") (pin "P$1") (pinfunction "1_P$1") (pintype "passive"))
      (node (ref "U603") (pin "1") (pinfunction "VIN_1") (pintype "bidirectional"))
      (node (ref "U603") (pin "4") (pinfunction "EN2_4") (pintype "bidirectional"))
    )
    (net (code "79") (name "Net-(C602-2)") (class "Default")
      (node (ref "C602") (pin "P$2") (pinfunction "2_P$2") (pintype "passive"))
      (node (ref "U603") (pin "6") (pinfunction "CSET_6") (pintype "bidirectional"))
    )
    (net (code "80") (name "Net-(C611-1)") (class "Default")
      (node (ref "C611") (pin "P$1") (pinfunction "1_P$1") (pintype "passive"))
      (node (ref "U101") (pin "49") (pinfunction "VCAP_1_49") (pintype "power_in"))
    )
    (net (code "81") (name "Net-(C613-1)") (class "Default")
      (node (ref "C613") (pin "P$1") (pinfunction "1_P$1") (pintype "passive"))
      (node (ref "U101") (pin "73") (pinfunction "VCAP_2_73") (pintype "power_in"))
    )
    (net (code "82") (name "Net-(C703-1)") (class "Default")
      (node (ref "C703") (pin "P$1") (pinfunction "1_P$1") (pintype "passive"))
      (node (ref "J701") (pin "1") (pinfunction "1_1") (pintype "passive"))
      (node (ref "R703") (pin "P$1") (pinfunction "1_P$1") (pintype "passive"))
      (node (ref "U702") (pin "1") (pinfunction "OUT_1") (pintype "output"))
    )
    (net (code "83") (name "Net-(C704-1)") (class "Default")
      (node (ref "C704") (pin "P$1") (pinfunction "1_P$1") (pintype "passive"))
      (node (ref "R705") (pin "P$1") (pinfunction "1_P$1") (pintype "passive"))
      (node (ref "U702") (pin "6") (pinfunction "VCC_6") (pintype "bidirectional"))
    )
    (net (code "84") (name "Net-(C805-1)") (class "Default")
      (node (ref "C805") (pin "P$1") (pinfunction "1_P$1") (pintype "passive"))
      (node (ref "U801") (pin "5") (pinfunction "PD0/OSC<=_5") (pintype "bidirectional"))
      (node (ref "X801") (pin "3") (pinfunction "3_3") (pintype "bidirectional"))
    )
    (net (code "85") (name "Net-(C806-2)") (class "Default")
      (node (ref "C806") (pin "P$2") (pinfunction "2_P$2") (pintype "passive"))
      (node (ref "U801") (pin "6") (pinfunction "PD1/OSC=>_6") (pintype "bidirectional"))
      (node (ref "X801") (pin "1") (pinfunction "1_1") (pintype "bidirectional"))
    )
    (net (code "86") (name "Net-(C1002-1)") (class "Default")
      (node (ref "C1002") (pin "P$1") (pinfunction "1_P$1") (pintype "passive"))
      (node (ref "U1002") (pin "6") (pinfunction "CSET_6") (pintype "bidirectional"))
    )
    (net (code "87") (name "Net-(C1105-1)") (class "Default")
      (node (ref "C1105") (pin "P$1") (pinfunction "1_P$1") (pintype "passive"))
      (node (ref "U1101") (pin "P$18") (pinfunction "VS1_P$18") (pintype "bidirectional"))
      (node (ref "U1102") (pin "P$1") (pinfunction "S_P$1") (pintype "passive"))
      (node (ref "U1102") (pin "P$3") (pinfunction "S_P$3") (pintype "passive"))
    )
    (net (code "88") (name "Net-(C1106-1)") (class "Default")
      (node (ref "C1106") (pin "P$1") (pinfunction "1_P$1") (pintype "passive"))
      (node (ref "U1101") (pin "P$16") (pinfunction "VS2_P$16") (pintype "bidirectional"))
      (node (ref "U1103") (pin "P$1") (pinfunction "S_P$1") (pintype "passive"))
      (node (ref "U1103") (pin "P$3") (pinfunction "S_P$3") (pintype "passive"))
    )
    (net (code "89") (name "Net-(C1107-1)") (class "Default")
      (node (ref "C1107") (pin "P$1") (pinfunction "1_P$1") (pintype "passive"))
      (node (ref "U1101") (pin "P$14") (pinfunction "VS3_P$14") (pintype "bidirectional"))
      (node (ref "U1104") (pin "P$1") (pinfunction "S_P$1") (pintype "passive"))
      (node (ref "U1104") (pin "P$3") (pinfunction "S_P$3") (pintype "passive"))
    )
    (net (code "90") (name "Net-(C1108-1)") (class "Default")
      (node (ref "C1108") (pin "P$1") (pinfunction "1_P$1") (pintype "passive"))
      (node (ref "R1105") (pin "P$2") (pinfunction "2_P$2") (pintype "passive"))
      (node (ref "R1106") (pin "P$1") (pinfunction "1_P$1") (pintype "passive"))
      (node (ref "U1101") (pin "P$1") (pinfunction "UV1_P$1") (pintype "bidirectional"))
    )
    (net (code "91") (name "Net-(C1109-1)") (class "Default")
      (node (ref "C1109") (pin "P$1") (pinfunction "1_P$1") (pintype "passive"))
      (node (ref "R1109") (pin "P$2") (pinfunction "2_P$2") (pintype "passive"))
      (node (ref "R1110") (pin "P$1") (pinfunction "1_P$1") (pintype "passive"))
      (node (ref "U1101") (pin "P$3") (pinfunction "UV2_P$3") (pintype "bidirectional"))
    )
    (net (code "92") (name "Net-(C1110-1)") (class "Default")
      (node (ref "C1110") (pin "P$1") (pinfunction "1_P$1") (pintype "passive"))
      (node (ref "R1112") (pin "P$2") (pinfunction "2_P$2") (pintype "passive"))
      (node (ref "R1113") (pin "P$1") (pinfunction "1_P$1") (pintype "passive"))
      (node (ref "U1101") (pin "P$5") (pinfunction "UV3_P$5") (pintype "bidirectional"))
    )
    (net (code "93") (name "Net-(D201-PadC)") (class "Default")
      (node (ref "D201") (pin "C") (pinfunction "C_C") (pintype "passive"))
      (node (ref "J201") (pin "1") (pinfunction "1_1") (pintype "passive"))
      (node (ref "L201") (pin "P$2") (pinfunction "P$2_P$2") (pintype "bidirectional"))
    )
    (net (code "94") (name "Net-(D202-PadC)") (class "Default")
      (node (ref "D202") (pin "C") (pinfunction "C_C") (pintype "passive"))
      (node (ref "J202") (pin "1") (pinfunction "1_1") (pintype "passive"))
      (node (ref "L202") (pin "P$2") (pinfunction "P$2_P$2") (pintype "bidirectional"))
    )
    (net (code "95") (name "Net-(D203-PadC)") (class "Default")
      (node (ref "D203") (pin "C") (pinfunction "C_C") (pintype "passive"))
      (node (ref "J203") (pin "1") (pinfunction "1_1") (pintype "passive"))
      (node (ref "J204") (pin "1") (pinfunction "1_1") (pintype "passive"))
      (node (ref "L203") (pin "P$2") (pinfunction "P$2_P$2") (pintype "bidirectional"))
    )
    (net (code "96") (name "Net-(D401-PadC)") (class "Default")
      (node (ref "D401") (pin "C") (pinfunction "C_C") (pintype "passive"))
      (node (ref "J401") (pin "1") (pinfunction "1_1") (pintype "passive"))
      (node (ref "J402") (pin "1") (pinfunction "1_1") (pintype "passive"))
      (node (ref "L401") (pin "P$2") (pinfunction "P$2_P$2") (pintype "bidirectional"))
    )
    (net (code "97") (name "Net-(D402-PadC)") (class "Default")
      (node (ref "D402") (pin "C") (pinfunction "C_C") (pintype "passive"))
      (node (ref "J403") (pin "1") (pinfunction "1_1") (pintype "passive"))
      (node (ref "L402") (pin "P$2") (pinfunction "P$2_P$2") (pintype "bidirectional"))
    )
    (net (code "98") (name "Net-(D403-PadC)") (class "Default")
      (node (ref "D403") (pin "C") (pinfunction "C_C") (pintype "passive"))
      (node (ref "J404") (pin "1") (pinfunction "1_1") (pintype "passive"))
      (node (ref "L404") (pin "P$2") (pinfunction "P$2_P$2") (pintype "bidirectional"))
    )
    (net (code "99") (name "Net-(D404-PadC)") (class "Default")
      (node (ref "D404") (pin "C") (pinfunction "C_C") (pintype "passive"))
      (node (ref "J405") (pin "1") (pinfunction "1_1") (pintype "passive"))
      (node (ref "L403") (pin "P$2") (pinfunction "P$2_P$2") (pintype "bidirectional"))
    )
    (net (code "100") (name "Net-(D904-C)") (class "Default")
      (node (ref "D903") (pin "C") (pinfunction "C_C") (pintype "passive"))
      (node (ref "D904") (pin "CATHODE") (pinfunction "C_CATHODE") (pintype "passive"))
      (node (ref "L901") (pin "P$1") (pinfunction "P$1_P$1") (pintype "bidirectional"))
    )
    (net (code "101") (name "Net-(D1001-A2)") (class "Default")
      (node (ref "D1001") (pin "2") (pinfunction "A2_2") (pintype "passive"))
      (node (ref "D1002") (pin "2") (pinfunction "A2_2") (pintype "passive"))
      (node (ref "U1001") (pin "8") (pinfunction "OUT_8") (pintype "bidirectional"))
    )
    (net (code "102") (name "Net-(D1002-CC)") (class "Default")
      (node (ref "D1002") (pin "3") (pinfunction "CC_3") (pintype "passive"))
      (node (ref "F1001") (pin "2") (pinfunction "2_2") (pintype "bidirectional"))
    )
    (net (code "103") (name "Net-(J301-2)") (class "Default")
      (node (ref "J301") (pin "D-") (pinfunction "2_D-") (pintype "bidirectional"))
      (node (ref "J302") (pin "3") (pinfunction "3_3") (pintype "passive"))
      (node (ref "U302") (pin "1") (pinfunction "D1I_1") (pintype "bidirectional"))
    )
    (net (code "104") (name "Net-(J301-3)") (class "Default")
      (node (ref "J301") (pin "D+") (pinfunction "3_D+") (pintype "bidirectional"))
      (node (ref "J302") (pin "2") (pinfunction "2_2") (pintype "passive"))
      (node (ref "U302") (pin "3") (pinfunction "D2I_3") (pintype "bidirectional"))
    )
    (net (code "105") (name "Net-(J901A-S)") (class "Default")
      (node (ref "J901") (pin "1") (pinfunction "S_1") (pintype "passive"))
      (node (ref "R909") (pin "P$2") (pinfunction "2_P$2") (pintype "passive"))
    )
    (net (code "106") (name "Net-(J901B-S)") (class "Default")
      (node (ref "J901") (pin "10") (pinfunction "S_10") (pintype "passive"))
      (node (ref "R914") (pin "P$2") (pinfunction "2_P$2") (pintype "passive"))
    )
    (net (code "107") (name "Net-(J901C-S)") (class "Default")
      (node (ref "J901") (pin "13") (pinfunction "S_13") (pintype "passive"))
      (node (ref "R906") (pin "P$2") (pinfunction "2_P$2") (pintype "passive"))
    )
    (net (code "108") (name "Net-(J901D-S)") (class "Default")
      (node (ref "J901") (pin "16") (pinfunction "S_16") (pintype "passive"))
      (node (ref "R915") (pin "P$2") (pinfunction "2_P$2") (pintype "passive"))
    )
    (net (code "109") (name "Net-(J901E-S)") (class "Default")
      (node (ref "J901") (pin "19") (pinfunction "S_19") (pintype "passive"))
      (node (ref "R907") (pin "P$2") (pinfunction "2_P$2") (pintype "passive"))
    )
    (net (code "110") (name "Net-(J901G-S)") (class "Default")
      (node (ref "J901") (pin "22") (pinfunction "S_22") (pintype "passive"))
      (node (ref "R916") (pin "P$2") (pinfunction "2_P$2") (pintype "passive"))
    )
    (net (code "111") (name "Net-(J901H-S)") (class "Default")
      (node (ref "J901") (pin "25") (pinfunction "S_25") (pintype "passive"))
      (node (ref "R908") (pin "P$2") (pinfunction "2_P$2") (pintype "passive"))
    )
    (net (code "112") (name "Net-(J901I-S)") (class "Default")
      (node (ref "J901") (pin "28") (pinfunction "S_28") (pintype "passive"))
      (node (ref "R917") (pin "P$2") (pinfunction "2_P$2") (pintype "passive"))
    )
    (net (code "113") (name "Net-(J901J-S)") (class "Default")
      (node (ref "J901") (pin "31") (pinfunction "S_31") (pintype "passive"))
      (node (ref "R902") (pin "P$2") (pinfunction "2_P$2") (pintype "passive"))
    )
    (net (code "114") (name "Net-(J901K-S)") (class "Default")
      (node (ref "J901") (pin "34") (pinfunction "S_34") (pintype "passive"))
      (node (ref "R911") (pin "P$2") (pinfunction "2_P$2") (pintype "passive"))
    )
    (net (code "115") (name "Net-(J901L-S)") (class "Default")
      (node (ref "J901") (pin "37") (pinfunction "S_37") (pintype "passive"))
      (node (ref "R903") (pin "P$2") (pinfunction "2_P$2") (pintype "passive"))
    )
    (net (code "116") (name "Net-(J901M-S)") (class "Default")
      (node (ref "J901") (pin "4") (pinfunction "S_4") (pintype "passive"))
      (node (ref "R910") (pin "P$2") (pinfunction "2_P$2") (pintype "passive"))
    )
    (net (code "117") (name "Net-(J901N-S)") (class "Default")
      (node (ref "J901") (pin "40") (pinfunction "S_40") (pintype "passive"))
      (node (ref "R912") (pin "P$2") (pinfunction "2_P$2") (pintype "passive"))
    )
    (net (code "118") (name "Net-(J901O-S)") (class "Default")
      (node (ref "J901") (pin "43") (pinfunction "S_43") (pintype "passive"))
      (node (ref "R904") (pin "P$2") (pinfunction "2_P$2") (pintype "passive"))
    )
    (net (code "119") (name "Net-(J901P-S)") (class "Default")
      (node (ref "J901") (pin "46") (pinfunction "S_46") (pintype "passive"))
      (node (ref "R913") (pin "P$2") (pinfunction "2_P$2") (pintype "passive"))
    )
    (net (code "120") (name "Net-(J901Q-S)") (class "Default")
      (node (ref "J901") (pin "7") (pinfunction "S_7") (pintype "passive"))
      (node (ref "R905") (pin "P$2") (pinfunction "2_P$2") (pintype "passive"))
    )
    (net (code "121") (name "Net-(L701-2)") (class "Default")
      (node (ref "L701") (pin "P$2") (pinfunction "2_P$2") (pintype "passive"))
      (node (ref "U702") (pin "5") (pinfunction "SW_5") (pintype "passive"))
    )
    (net (code "122") (name "Net-(Q601-PadC)") (class "Default")
      (node (ref "Q601") (pin "C") (pinfunction "C_C") (pintype "passive"))
      (node (ref "R621") (pin "2") (pinfunction "2_2") (pintype "passive"))
    )
    (net (code "123") (name "Net-(R101-1)") (class "Default")
      (node (ref "R101") (pin "P$1") (pinfunction "1_P$1") (pintype "passive"))
      (node (ref "U101") (pin "69") (pinfunction "PA10_69") (pintype "bidirectional"))
    )
    (net (code "124") (name "Net-(R102-1)") (class "Default")
      (node (ref "R102") (pin "P$1") (pinfunction "1_P$1") (pintype "passive"))
      (node (ref "U101") (pin "37") (pinfunction "PB2_37") (pintype "bidirectional"))
    )
    (net (code "125") (name "Net-(R201-1)") (class "Default")
      (node (ref "R201") (pin "P$1") (pinfunction "1_P$1") (pintype "passive"))
      (node (ref "U201") (pin "20") (pinfunction "B1_20") (pintype "bidirectional"))
    )
    (net (code "126") (name "Net-(R202-1)") (class "Default")
      (node (ref "R202") (pin "P$1") (pinfunction "1_P$1") (pintype "passive"))
      (node (ref "U201") (pin "17") (pinfunction "B3_17") (pintype "bidirectional"))
    )
    (net (code "127") (name "Net-(R203-1)") (class "Default")
      (node (ref "R203") (pin "P$1") (pinfunction "1_P$1") (pintype "passive"))
      (node (ref "U201") (pin "15") (pinfunction "B5_15") (pintype "bidirectional"))
    )
    (net (code "128") (name "Net-(R204-1)") (class "Default")
      (node (ref "R204") (pin "P$1") (pinfunction "1_P$1") (pintype "passive"))
      (node (ref "U201") (pin "13") (pinfunction "B7_13") (pintype "bidirectional"))
    )
    (net (code "129") (name "Net-(R205-1)") (class "Default")
      (node (ref "R205") (pin "P$1") (pinfunction "1_P$1") (pintype "passive"))
      (node (ref "U202") (pin "17") (pinfunction "B3_17") (pintype "bidirectional"))
    )
    (net (code "130") (name "Net-(R206-1)") (class "Default")
      (node (ref "R206") (pin "P$1") (pinfunction "1_P$1") (pintype "passive"))
      (node (ref "U202") (pin "15") (pinfunction "B5_15") (pintype "bidirectional"))
    )
    (net (code "131") (name "Net-(R207-1)") (class "Default")
      (node (ref "R207") (pin "P$1") (pinfunction "1_P$1") (pintype "passive"))
      (node (ref "U202") (pin "13") (pinfunction "B7_13") (pintype "bidirectional"))
    )
    (net (code "132") (name "Net-(R208-1)") (class "Default")
      (node (ref "R208") (pin "P$1") (pinfunction "1_P$1") (pintype "passive"))
      (node (ref "U201") (pin "18") (pinfunction "B2_18") (pintype "bidirectional"))
    )
    (net (code "133") (name "Net-(R209-1)") (class "Default")
      (node (ref "R209") (pin "P$1") (pinfunction "1_P$1") (pintype "passive"))
      (node (ref "U201") (pin "16") (pinfunction "B4_16") (pintype "bidirectional"))
    )
    (net (code "134") (name "Net-(R210-1)") (class "Default")
      (node (ref "R210") (pin "P$1") (pinfunction "1_P$1") (pintype "passive"))
      (node (ref "U201") (pin "14") (pinfunction "B6_14") (pintype "bidirectional"))
    )
    (net (code "135") (name "Net-(R211-1)") (class "Default")
      (node (ref "R211") (pin "P$1") (pinfunction "1_P$1") (pintype "passive"))
      (node (ref "U201") (pin "12") (pinfunction "B8_12") (pintype "bidirectional"))
    )
    (net (code "136") (name "Net-(R212-1)") (class "Default")
      (node (ref "R212") (pin "P$1") (pinfunction "1_P$1") (pintype "passive"))
      (node (ref "U202") (pin "16") (pinfunction "B4_16") (pintype "bidirectional"))
    )
    (net (code "137") (name "Net-(R213-1)") (class "Default")
      (node (ref "R213") (pin "P$1") (pinfunction "1_P$1") (pintype "passive"))
      (node (ref "U202") (pin "14") (pinfunction "B6_14") (pintype "bidirectional"))
    )
    (net (code "138") (name "Net-(R214-1)") (class "Default")
      (node (ref "R214") (pin "P$1") (pinfunction "1_P$1") (pintype "passive"))
      (node (ref "U202") (pin "12") (pinfunction "B8_12") (pintype "bidirectional"))
    )
    (net (code "139") (name "Net-(R215-2)") (class "Default")
      (node (ref "J203") (pin "4") (pinfunction "4_4") (pintype "passive"))
      (node (ref "R215") (pin "P$2") (pinfunction "2_P$2") (pintype "passive"))
    )
    (net (code "140") (name "Net-(R216-2)") (class "Default")
      (node (ref "J203") (pin "5") (pinfunction "5_5") (pintype "passive"))
      (node (ref "R216") (pin "P$2") (pinfunction "2_P$2") (pintype "passive"))
    )
    (net (code "141") (name "Net-(R404-2)") (class "Default")
      (node (ref "J401") (pin "2") (pinfunction "2_2") (pintype "passive"))
      (node (ref "R404") (pin "P$2") (pinfunction "2_P$2") (pintype "passive"))
    )
    (net (code "142") (name "Net-(R405-2)") (class "Default")
      (node (ref "J401") (pin "3") (pinfunction "3_3") (pintype "passive"))
      (node (ref "R405") (pin "P$2") (pinfunction "2_P$2") (pintype "passive"))
    )
    (net (code "143") (name "Net-(R407-2)") (class "Default")
      (node (ref "J404") (pin "2") (pinfunction "2_2") (pintype "passive"))
      (node (ref "R407") (pin "P$2") (pinfunction "2_P$2") (pintype "passive"))
    )
    (net (code "144") (name "Net-(R408-2)") (class "Default")
      (node (ref "J404") (pin "4") (pinfunction "4_4") (pintype "passive"))
      (node (ref "R408") (pin "P$2") (pinfunction "2_P$2") (pintype "passive"))
    )
    (net (code "145") (name "Net-(R608-2)") (class "Default")
      (node (ref "D602") (pin "C") (pinfunction "C_C") (pintype "passive"))
      (node (ref "R608") (pin "P$2") (pinfunction "2_P$2") (pintype "passive"))
    )
    (net (code "146") (name "Net-(R616-1)") (class "Default")
      (node (ref "R616") (pin "P$1") (pinfunction "1_P$1") (pintype "passive"))
      (node (ref "U602") (pin "7") (pinfunction "ILIM_7") (pintype "bidirectional"))
    )
    (net (code "147") (name "Net-(R617-1)") (class "Default")
      (node (ref "R617") (pin "P$1") (pinfunction "1_P$1") (pintype "passive"))
      (node (ref "U601") (pin "7") (pinfunction "ILIM_7") (pintype "bidirectional"))
    )
    (net (code "148") (name "Net-(R620-1)") (class "Default")
      (node (ref "Q601") (pin "B") (pinfunction "B_B") (pintype "passive"))
      (node (ref "R620") (pin "P$1") (pinfunction "1_P$1") (pintype "passive"))
    )
    (net (code "149") (name "Net-(R701-1)") (class "Default")
      (node (ref "R701") (pin "P$1") (pinfunction "1_P$1") (pintype "passive"))
      (node (ref "U702") (pin "7") (pinfunction "+IN_7") (pintype "input"))
    )
    (net (code "150") (name "Net-(R702-1)") (class "Default")
      (node (ref "R702") (pin "P$1") (pinfunction "1_P$1") (pintype "passive"))
      (node (ref "R703") (pin "P$2") (pinfunction "2_P$2") (pintype "passive"))
      (node (ref "U702") (pin "8") (pinfunction "-IN_8") (pintype "input"))
    )
    (net (code "151") (name "Net-(R704-2)") (class "Default")
      (node (ref "R704") (pin "P$2") (pinfunction "2_P$2") (pintype "passive"))
      (node (ref "U701") (pin "6") (pinfunction "REXT_6") (pintype "bidirectional"))
    )
    (net (code "152") (name "Net-(R705-2)") (class "Default")
      (node (ref "R705") (pin "P$2") (pinfunction "2_P$2") (pintype "passive"))
      (node (ref "R706") (pin "P$1") (pinfunction "1_P$1") (pintype "passive"))
      (node (ref "U702") (pin "2") (pinfunction "FB_2") (pintype "bidirectional"))
    )
    (net (code "153") (name "Net-(R707-2)") (class "Default")
      (node (ref "R707") (pin "P$2") (pinfunction "2_P$2") (pintype "passive"))
      (node (ref "R735") (pin "P$1") (pinfunction "1_P$1") (pintype "passive"))
    )
    (net (code "154") (name "Net-(R708-2)") (class "Default")
      (node (ref "LED702") (pin "C") (pinfunction "C_C") (pintype "passive"))
      (node (ref "R708") (pin "P$2") (pinfunction "2_P$2") (pintype "passive"))
    )
    (net (code "155") (name "Net-(R709-2)") (class "Default")
      (node (ref "R709") (pin "P$2") (pinfunction "2_P$2") (pintype "passive"))
      (node (ref "R736") (pin "P$1") (pinfunction "1_P$1") (pintype "passive"))
    )
    (net (code "156") (name "Net-(R710-1)") (class "Default")
      (node (ref "J702") (pin "2") (pinfunction "2_2") (pintype "passive"))
      (node (ref "R710") (pin "P$1") (pinfunction "1_P$1") (pintype "passive"))
    )
    (net (code "157") (name "Net-(R711-2)") (class "Default")
      (node (ref "LED704") (pin "C") (pinfunction "C_C") (pintype "passive"))
      (node (ref "R711") (pin "P$2") (pinfunction "2_P$2") (pintype "passive"))
    )
    (net (code "158") (name "Net-(R712-2)") (class "Default")
      (node (ref "LED705") (pin "C") (pinfunction "C_C") (pintype "passive"))
      (node (ref "R712") (pin "P$2") (pinfunction "2_P$2") (pintype "passive"))
    )
    (net (code "159") (name "Net-(R735-2)") (class "Default")
      (node (ref "LED701") (pin "C") (pinfunction "C_C") (pintype "passive"))
      (node (ref "R735") (pin "P$2") (pinfunction "2_P$2") (pintype "passive"))
    )
    (net (code "160") (name "Net-(R736-2)") (class "Default")
      (node (ref "LED703") (pin "C") (pinfunction "C_C") (pintype "passive"))
      (node (ref "R736") (pin "P$2") (pinfunction "2_P$2") (pintype "passive"))
    )
    (net (code "161") (name "Net-(R802-1)") (class "Default")
      (node (ref "R802") (pin "P$1") (pinfunction "1_P$1") (pintype "passive"))
      (node (ref "U801") (pin "20") (pinfunction "PB2_20") (pintype "bidirectional"))
    )
    (net (code "162") (name "Net-(R803-1)") (class "Default")
      (node (ref "R803") (pin "P$1") (pinfunction "1_P$1") (pintype "passive"))
      (node (ref "U801") (pin "12") (pinfunction "PA2_12") (pintype "bidirectional"))
    )
    (net (code "163") (name "Net-(R804-1)") (class "Default")
      (node (ref "R804") (pin "P$1") (pinfunction "1_P$1") (pintype "passive"))
      (node (ref "U801") (pin "13") (pinfunction "PA3_13") (pintype "bidirectional"))
    )
    (net (code "164") (name "Net-(R901-2)") (class "Default")
      (node (ref "D902") (pin "C") (pinfunction "C_C") (pintype "passive"))
      (node (ref "R901") (pin "P$2") (pinfunction "2_P$2") (pintype "passive"))
      (node (ref "R910") (pin "P$1") (pinfunction "1_P$1") (pintype "passive"))
      (node (ref "U903") (pin "3") (pinfunction "2Y_3") (pintype "bidirectional"))
    )
    (net (code "165") (name "Net-(R902-1)") (class "Default")
      (node (ref "R902") (pin "P$1") (pinfunction "1_P$1") (pintype "passive"))
      (node (ref "U901") (pin "20") (pinfunction "B1_20") (pintype "bidirectional"))
    )
    (net (code "166") (name "Net-(R903-1)") (class "Default")
      (node (ref "R903") (pin "P$1") (pinfunction "1_P$1") (pintype "passive"))
      (node (ref "U901") (pin "17") (pinfunction "B3_17") (pintype "bidirectional"))
    )
    (net (code "167") (name "Net-(R904-1)") (class "Default")
      (node (ref "R904") (pin "P$1") (pinfunction "1_P$1") (pintype "passive"))
      (node (ref "U901") (pin "15") (pinfunction "B5_15") (pintype "bidirectional"))
    )
    (net (code "168") (name "Net-(R905-1)") (class "Default")
      (node (ref "R905") (pin "P$1") (pinfunction "1_P$1") (pintype "passive"))
      (node (ref "U902") (pin "20") (pinfunction "B1_20") (pintype "bidirectional"))
    )
    (net (code "169") (name "Net-(R906-1)") (class "Default")
      (node (ref "R906") (pin "P$1") (pinfunction "1_P$1") (pintype "passive"))
      (node (ref "U902") (pin "17") (pinfunction "B3_17") (pintype "bidirectional"))
    )
    (net (code "170") (name "Net-(R907-1)") (class "Default")
      (node (ref "R907") (pin "P$1") (pinfunction "1_P$1") (pintype "passive"))
      (node (ref "U902") (pin "15") (pinfunction "B5_15") (pintype "bidirectional"))
    )
    (net (code "171") (name "Net-(R908-1)") (class "Default")
      (node (ref "R908") (pin "P$1") (pinfunction "1_P$1") (pintype "passive"))
      (node (ref "U902") (pin "13") (pinfunction "B7_13") (pintype "bidirectional"))
    )
    (net (code "172") (name "Net-(R911-1)") (class "Default")
      (node (ref "R911") (pin "P$1") (pinfunction "1_P$1") (pintype "passive"))
      (node (ref "U901") (pin "18") (pinfunction "B2_18") (pintype "bidirectional"))
    )
    (net (code "173") (name "Net-(R912-1)") (class "Default")
      (node (ref "R912") (pin "P$1") (pinfunction "1_P$1") (pintype "passive"))
      (node (ref "U901") (pin "16") (pinfunction "B4_16") (pintype "bidirectional"))
    )
    (net (code "174") (name "Net-(R913-1)") (class "Default")
      (node (ref "R913") (pin "P$1") (pinfunction "1_P$1") (pintype "passive"))
      (node (ref "U901") (pin "14") (pinfunction "B6_14") (pintype "bidirectional"))
    )
    (net (code "175") (name "Net-(R914-1)") (class "Default")
      (node (ref "R914") (pin "P$1") (pinfunction "1_P$1") (pintype "passive"))
      (node (ref "U902") (pin "18") (pinfunction "B2_18") (pintype "bidirectional"))
    )
    (net (code "176") (name "Net-(R915-1)") (class "Default")
      (node (ref "R915") (pin "P$1") (pinfunction "1_P$1") (pintype "passive"))
      (node (ref "U902") (pin "16") (pinfunction "B4_16") (pintype "bidirectional"))
    )
    (net (code "177") (name "Net-(R916-1)") (class "Default")
      (node (ref "R916") (pin "P$1") (pinfunction "1_P$1") (pintype "passive"))
      (node (ref "U902") (pin "14") (pinfunction "B6_14") (pintype "bidirectional"))
    )
    (net (code "178") (name "Net-(R917-1)") (class "Default")
      (node (ref "R917") (pin "P$1") (pinfunction "1_P$1") (pintype "passive"))
      (node (ref "U902") (pin "12") (pinfunction "B8_12") (pintype "bidirectional"))
    )
    (net (code "179") (name "Net-(R918-2)") (class "Default")
      (node (ref "R918") (pin "P$2") (pinfunction "2_P$2") (pintype "passive"))
      (node (ref "R922") (pin "P$1") (pinfunction "1_P$1") (pintype "passive"))
    )
    (net (code "180") (name "Net-(R1001-2)") (class "Default")
      (node (ref "R1001") (pin "P$2") (pinfunction "2_P$2") (pintype "passive"))
      (node (ref "U1001") (pin "7") (pinfunction "ILIM_7") (pintype "bidirectional"))
    )
    (net (code "181") (name "Net-(R1101-2)") (class "Default")
      (node (ref "L1101") (pin "P$2") (pinfunction "P$2_P$2") (pintype "bidirectional"))
      (node (ref "R1101") (pin "P$2") (pinfunction "2_P$2") (pintype "passive"))
    )
    (net (code "182") (name "Net-(R1102-2)") (class "Default")
      (node (ref "L1102") (pin "P$2") (pinfunction "P$2_P$2") (pintype "bidirectional"))
      (node (ref "R1102") (pin "P$2") (pinfunction "2_P$2") (pintype "passive"))
    )
    (net (code "183") (name "Net-(R1103-1)") (class "Default")
      (node (ref "J601") (pin "4") (pinfunction "4_4") (pintype "passive"))
      (node (ref "L1102") (pin "P$1") (pinfunction "P$1_P$1") (pintype "bidirectional"))
      (node (ref "R1103") (pin "P$1") (pinfunction "1_P$1") (pintype "passive"))
    )
    (net (code "184") (name "Net-(R1104-1)") (class "Default")
      (node (ref "J601") (pin "3") (pinfunction "3_3") (pintype "passive"))
      (node (ref "L1101") (pin "P$1") (pinfunction "P$1_P$1") (pintype "bidirectional"))
      (node (ref "R1104") (pin "P$1") (pinfunction "1_P$1") (pintype "passive"))
    )
    (net (code "185") (name "Net-(R1106-2)") (class "Default")
      (node (ref "R1106") (pin "P$2") (pinfunction "2_P$2") (pintype "passive"))
      (node (ref "R1107") (pin "P$1") (pinfunction "1_P$1") (pintype "passive"))
      (node (ref "U1101") (pin "P$2") (pinfunction "OV1_P$2") (pintype "bidirectional"))
    )
    (net (code "186") (name "Net-(R1110-2)") (class "Default")
      (node (ref "R1110") (pin "P$2") (pinfunction "2_P$2") (pintype "passive"))
      (node (ref "R1111") (pin "P$1") (pinfunction "1_P$1") (pintype "passive"))
      (node (ref "U1101") (pin "P$4") (pinfunction "OV2_P$4") (pintype "bidirectional"))
    )
    (net (code "187") (name "Net-(R1113-2)") (class "Default")
      (node (ref "R1113") (pin "P$2") (pinfunction "2_P$2") (pintype "passive"))
      (node (ref "R1114") (pin "P$1") (pinfunction "1_P$1") (pintype "passive"))
      (node (ref "U1101") (pin "P$6") (pinfunction "OV3_P$6") (pintype "bidirectional"))
    )
    (net (code "188") (name "Net-(R1115-2)") (class "Default")
      (node (ref "R1115") (pin "P$2") (pinfunction "2_P$2") (pintype "passive"))
      (node (ref "U1101") (pin "P$24") (pinfunction "HYS_P$24") (pintype "bidirectional"))
    )
    (net (code "189") (name "Net-(U701-OUT0)") (class "Default")
      (node (ref "U701") (pin "9") (pinfunction "OUT0_9") (pintype "open_collector"))
      (node (ref "U703") (pin "C1") (pinfunction "C_C1") (pintype "passive"))
    )
    (net (code "190") (name "Net-(U701-OUT1)") (class "Default")
      (node (ref "U701") (pin "8") (pinfunction "OUT1_8") (pintype "open_collector"))
      (node (ref "U703") (pin "C2") (pinfunction "C_C2") (pintype "passive"))
    )
    (net (code "191") (name "Net-(U701-OUT2)") (class "Default")
      (node (ref "U701") (pin "7") (pinfunction "OUT2_7") (pintype "open_collector"))
      (node (ref "U703") (pin "C3") (pinfunction "C_C3") (pintype "passive"))
    )
    (net (code "192") (name "Net-(U1101-G1)") (class "Default")
      (node (ref "U1101") (pin "P$17") (pinfunction "G1_P$17") (pintype "bidirectional"))
      (node (ref "U1102") (pin "P$2") (pinfunction "G_P$2") (pintype "passive"))
      (node (ref "U1102") (pin "P$4") (pinfunction "G_P$4") (pintype "passive"))
    )
    (net (code "193") (name "Net-(U1101-G2)") (class "Default")
      (node (ref "U1101") (pin "P$15") (pinfunction "G2_P$15") (pintype "bidirectional"))
      (node (ref "U1103") (pin "P$2") (pinfunction "G_P$2") (pintype "passive"))
      (node (ref "U1103") (pin "P$4") (pinfunction "G_P$4") (pintype "passive"))
    )
    (net (code "194") (name "Net-(U1101-G3)") (class "Default")
      (node (ref "U1101") (pin "P$13") (pinfunction "G3_P$13") (pintype "bidirectional"))
      (node (ref "U1104") (pin "P$2") (pinfunction "G_P$2") (pintype "passive"))
      (node (ref "U1104") (pin "P$4") (pinfunction "G_P$4") (pintype "passive"))
    )
    (net (code "195") (name "OTG_FS_DM") (class "Default")
      (node (ref "U101") (pin "70") (pinfunction "PA11_70") (pintype "bidirectional"))
      (node (ref "U302") (pin "6") (pinfunction "D1O_6") (pintype "bidirectional"))
    )
    (net (code "196") (name "OTG_FS_DP") (class "Default")
      (node (ref "U101") (pin "71") (pinfunction "PA12_71") (pintype "bidirectional"))
      (node (ref "U302") (pin "4") (pinfunction "D2O_4") (pintype "bidirectional"))
    )
    (net (code "197") (name "PPM_INPUT") (class "Default")
      (node (ref "D901") (pin "C") (pinfunction "C_C") (pintype "passive"))
      (node (ref "R909") (pin "P$1") (pinfunction "1_P$1") (pintype "passive"))
      (node (ref "U801") (pin "29") (pinfunction "PA8_29") (pintype "bidirectional"))
      (node (ref "U903") (pin "2") (pinfunction "1A_2") (pintype "bidirectional"))
    )
    (net (code "198") (name "PRESSURE_SENS") (class "Default")
      (node (ref "C401") (pin "P$1") (pinfunction "1_P$1") (pintype "passive"))
      (node (ref "R403") (pin "P$2") (pinfunction "2_P$2") (pintype "passive"))
      (node (ref "R406") (pin "P$1") (pinfunction "1_P$1") (pintype "passive"))
      (node (ref "U101") (pin "34") (pinfunction "PC5_34") (pintype "bidirectional"))
    )
    (net (code "199") (name "PRESSURE_SENS_IN") (class "Default")
      (node (ref "ADC_PR") (pin "P$1") (pinfunction "P$1_P$1") (pintype "passive"))
      (node (ref "J402") (pin "2") (pinfunction "2_2") (pintype "passive"))
      (node (ref "R406") (pin "P$2") (pinfunction "2_P$2") (pintype "passive"))
    )
    (net (code "200") (name "RSSI_IN") (class "Default")
      (node (ref "R901") (pin "P$1") (pinfunction "1_P$1") (pintype "passive"))
      (node (ref "U801") (pin "15") (pinfunction "PA5_15") (pintype "bidirectional"))
      (node (ref "U801") (pin "33") (pinfunction "PA12_33") (pintype "bidirectional"))
    )
    (net (code "201") (name "RX-VDD_5V5") (class "Default")
      (node (ref "F1001") (pin "1") (pinfunction "1_1") (pintype "bidirectional"))
      (node (ref "J901") (pin "2") (pinfunction "S_2") (pintype "passive"))
    )
    (net (code "202") (name "SAFETY") (class "Default")
      (node (ref "J702") (pin "3") (pinfunction "3_3") (pintype "passive"))
      (node (ref "R713") (pin "P$1") (pinfunction "1_P$1") (pintype "passive"))
      (node (ref "U801") (pin "41") (pinfunction "PB5_41") (pintype "bidirectional"))
    )
    (net (code "203") (name "SBUS_INPUT") (class "Default")
      (node (ref "U801") (pin "22") (pinfunction "PB11_22") (pintype "bidirectional"))
      (node (ref "U903") (pin "6") (pinfunction "1Y_6") (pintype "bidirectional"))
    )
    (net (code "204") (name "SBUS_OUTPUT") (class "Default")
      (node (ref "U801") (pin "21") (pinfunction "PB10_21") (pintype "bidirectional"))
      (node (ref "U903") (pin "5") (pinfunction "2A_5") (pintype "bidirectional"))
    )
    (net (code "205") (name "SDIO_CK") (class "Default")
      (node (ref "U101") (pin "80") (pinfunction "PC12_80") (pintype "bidirectional"))
      (node (ref "U301") (pin "5") (pinfunction "CLK_5") (pintype "bidirectional"))
    )
    (net (code "206") (name "SDIO_CMD") (class "Default")
      (node (ref "R303") (pin "P$1") (pinfunction "1_P$1") (pintype "passive"))
      (node (ref "U101") (pin "83") (pinfunction "PD2_83") (pintype "bidirectional"))
      (node (ref "U301") (pin "3") (pinfunction "CMD_3") (pintype "bidirectional"))
    )
    (net (code "207") (name "SDIO_D0") (class "Default")
      (node (ref "R304") (pin "P$1") (pinfunction "1_P$1") (pintype "passive"))
      (node (ref "U101") (pin "65") (pinfunction "PC8_65") (pintype "bidirectional"))
      (node (ref "U301") (pin "7") (pinfunction "D0_7") (pintype "bidirectional"))
    )
    (net (code "208") (name "SDIO_D1") (class "Default")
      (node (ref "R305") (pin "P$1") (pinfunction "1_P$1") (pintype "passive"))
      (node (ref "U101") (pin "66") (pinfunction "PC9_66") (pintype "bidirectional"))
      (node (ref "U301") (pin "8") (pinfunction "D1_8") (pintype "bidirectional"))
    )
    (net (code "209") (name "SDIO_D2") (class "Default")
      (node (ref "R301") (pin "P$1") (pinfunction "1_P$1") (pintype "passive"))
      (node (ref "U101") (pin "78") (pinfunction "PC10_78") (pintype "bidirectional"))
      (node (ref "U301") (pin "1") (pinfunction "D2_1") (pintype "bidirectional"))
    )
    (net (code "210") (name "SDIO_D3") (class "Default")
      (node (ref "R302") (pin "P$1") (pinfunction "1_P$1") (pintype "passive"))
      (node (ref "U101") (pin "79") (pinfunction "PC11_79") (pintype "bidirectional"))
      (node (ref "U301") (pin "2") (pinfunction "D3_2") (pintype "bidirectional"))
    )
    (net (code "211") (name "SERIAL1_CTS") (class "Default")
      (node (ref "J201") (pin "4") (pinfunction "4_4") (pintype "passive"))
      (node (ref "R211") (pin "P$2") (pinfunction "2_P$2") (pintype "passive"))
    )
    (net (code "212") (name "SERIAL1_RTS") (class "Default")
      (node (ref "J201") (pin "5") (pinfunction "5_5") (pintype "passive"))
      (node (ref "R204") (pin "P$2") (pinfunction "2_P$2") (pintype "passive"))
    )
    (net (code "213") (name "SERIAL1_RX") (class "Default")
      (node (ref "J201") (pin "3") (pinfunction "3_3") (pintype "passive"))
      (node (ref "R203") (pin "P$2") (pinfunction "2_P$2") (pintype "passive"))
      (node (ref "S1RX") (pin "P$1") (pinfunction "P$1_P$1") (pintype "passive"))
    )
    (net (code "214") (name "SERIAL1_TX") (class "Default")
      (node (ref "J201") (pin "2") (pinfunction "2_2") (pintype "passive"))
      (node (ref "R210") (pin "P$2") (pinfunction "2_P$2") (pintype "passive"))
      (node (ref "S1TX") (pin "P$1") (pinfunction "P$1_P$1") (pintype "passive"))
    )
    (net (code "215") (name "SERIAL2_CTS") (class "Default")
      (node (ref "J202") (pin "4") (pinfunction "4_4") (pintype "passive"))
      (node (ref "R208") (pin "P$2") (pinfunction "2_P$2") (pintype "passive"))
    )
    (net (code "216") (name "SERIAL2_RTS") (class "Default")
      (node (ref "J202") (pin "5") (pinfunction "5_5") (pintype "passive"))
      (node (ref "R201") (pin "P$2") (pinfunction "2_P$2") (pintype "passive"))
    )
    (net (code "217") (name "SERIAL2_RX") (class "Default")
      (node (ref "J202") (pin "3") (pinfunction "3_3") (pintype "passive"))
      (node (ref "R202") (pin "P$2") (pinfunction "2_P$2") (pintype "passive"))
      (node (ref "S2RX") (pin "P$1") (pinfunction "P$1_P$1") (pintype "passive"))
    )
    (net (code "218") (name "SERIAL2_TX") (class "Default")
      (node (ref "J202") (pin "2") (pinfunction "2_2") (pintype "passive"))
      (node (ref "R209") (pin "P$2") (pinfunction "2_P$2") (pintype "passive"))
      (node (ref "S2TX") (pin "P$1") (pinfunction "P$1_P$1") (pintype "passive"))
    )
    (net (code "219") (name "SERIAL3_RX") (class "Default")
      (node (ref "J203") (pin "3") (pinfunction "3_3") (pintype "passive"))
      (node (ref "R207") (pin "P$2") (pinfunction "2_P$2") (pintype "passive"))
      (node (ref "S3RX") (pin "P$1") (pinfunction "P$1_P$1") (pintype "passive"))
    )
    (net (code "220") (name "SERIAL3_TX") (class "Default")
      (node (ref "J203") (pin "2") (pinfunction "2_2") (pintype "passive"))
      (node (ref "R214") (pin "P$2") (pinfunction "2_P$2") (pintype "passive"))
      (node (ref "S3TX") (pin "P$1") (pinfunction "P$1_P$1") (pintype "passive"))
    )
    (net (code "221") (name "SERIAL4_RX") (class "Default")
      (node (ref "J204") (pin "3") (pinfunction "3_3") (pintype "passive"))
      (node (ref "R206") (pin "P$2") (pinfunction "2_P$2") (pintype "passive"))
      (node (ref "S4RX") (pin "P$1") (pinfunction "P$1_P$1") (pintype "passive"))
    )
    (net (code "222") (name "SERIAL4_TX") (class "Default")
      (node (ref "J204") (pin "2") (pinfunction "2_2") (pintype "passive"))
      (node (ref "R213") (pin "P$2") (pinfunction "2_P$2") (pintype "passive"))
      (node (ref "S4TX") (pin "P$1") (pinfunction "P$1_P$1") (pintype "passive"))
    )
    (net (code "223") (name "SERIAL5_RX") (class "Default")
      (node (ref "J204") (pin "5") (pinfunction "5_5") (pintype "passive"))
      (node (ref "R205") (pin "P$2") (pinfunction "2_P$2") (pintype "passive"))
      (node (ref "S5_RX") (pin "P$1") (pinfunction "P$1_P$1") (pintype "passive"))
    )
    (net (code "224") (name "SERIAL5_TX") (class "Default")
      (node (ref "J204") (pin "4") (pinfunction "4_4") (pintype "passive"))
      (node (ref "R212") (pin "P$2") (pinfunction "2_P$2") (pintype "passive"))
      (node (ref "S5_TX") (pin "P$1") (pinfunction "P$1_P$1") (pintype "passive"))
    )
    (net (code "225") (name "SERIAL_FMU_TO_IO") (class "Default")
      (node (ref "R804") (pin "P$2") (pinfunction "2_P$2") (pintype "passive"))
      (node (ref "U101") (pin "63") (pinfunction "PC6_63") (pintype "bidirectional"))
    )
    (net (code "226") (name "SERIAL_IO_TO_FMU") (class "Default")
      (node (ref "R803") (pin "P$2") (pinfunction "2_P$2") (pintype "passive"))
      (node (ref "U101") (pin "64") (pinfunction "PC7_64") (pintype "bidirectional"))
    )
    (net (code "227") (name "SPI_EXT_MISO") (class "Default")
      (node (ref "J403") (pin "3") (pinfunction "3_3") (pintype "passive"))
      (node (ref "U101") (pin "4") (pinfunction "PE5_4") (pintype "bidirectional"))
    )
    (net (code "228") (name "SPI_EXT_MOSI") (class "Default")
      (node (ref "J403") (pin "4") (pinfunction "4_4") (pintype "passive"))
      (node (ref "U101") (pin "5") (pinfunction "PE6_5") (pintype "bidirectional"))
    )
    (net (code "229") (name "SPI_EXT_SCK") (class "Default")
      (node (ref "J403") (pin "2") (pinfunction "2_2") (pintype "passive"))
      (node (ref "U101") (pin "1") (pinfunction "PE2_1") (pintype "bidirectional"))
    )
    (net (code "230") (name "SPI_INT_MISO") (class "Default")
      (node (ref "U101") (pin "31") (pinfunction "PA6_31") (pintype "bidirectional"))
      (node (ref "U501") (pin "4") (pinfunction "SDO/SA0_4") (pintype "bidirectional"))
      (node (ref "U502") (pin "4") (pinfunction "SDO/SA0_4") (pintype "bidirectional"))
      (node (ref "U504") (pin "7") (pinfunction "SDO/SA0_7") (pintype "bidirectional"))
      (node (ref "U505") (pin "9") (pinfunction "AD0/SDO_9") (pintype "bidirectional"))
      (node (ref "U506") (pin "6") (pinfunction "SDO_6") (pintype "bidirectional"))
      (node (ref "X503") (pin "9") (pinfunction "S_9") (pintype "passive"))
    )
    (net (code "231") (name "SPI_INT_MOSI") (class "Default")
      (node (ref "U101") (pin "32") (pinfunction "PA7_32") (pintype "bidirectional"))
      (node (ref "U501") (pin "3") (pinfunction "SDA/SDI/SDO_3") (pintype "bidirectional"))
      (node (ref "U502") (pin "3") (pinfunction "SDA/SDI/SDO_3") (pintype "bidirectional"))
      (node (ref "U504") (pin "6") (pinfunction "SDA/SDI/SDO_6") (pintype "bidirectional"))
      (node (ref "U505") (pin "24") (pinfunction "SDA/SDI_24") (pintype "bidirectional"))
      (node (ref "U506") (pin "7") (pinfunction "SDI/SDA_7") (pintype "bidirectional"))
      (node (ref "X503") (pin "8") (pinfunction "S_8") (pintype "passive"))
    )
    (net (code "232") (name "SPI_INT_SCK") (class "Default")
      (node (ref "U101") (pin "30") (pinfunction "PA5_30") (pintype "bidirectional"))
      (node (ref "U501") (pin "2") (pinfunction "SCL/SPC_2") (pintype "input"))
      (node (ref "U502") (pin "2") (pinfunction "SCL/SPC_2") (pintype "bidirectional"))
      (node (ref "U504") (pin "4") (pinfunction "SCL/SPC_4") (pintype "bidirectional"))
      (node (ref "U505") (pin "23") (pinfunction "SCL/SCLK_23") (pintype "bidirectional"))
      (node (ref "U506") (pin "8") (pinfunction "SCLK_8") (pintype "bidirectional"))
      (node (ref "X503") (pin "10") (pinfunction "S_10") (pintype "passive"))
    )
    (net (code "233") (name "VBAT") (class "Default")
      (node (ref "B601") (pin "1") (pinfunction "POS_1") (pintype "bidirectional"))
      (node (ref "R608") (pin "P$1") (pinfunction "1_P$1") (pintype "passive"))
      (node (ref "U101") (pin "6") (pinfunction "VBAT_6") (pintype "power_in"))
      (node (ref "U801") (pin "1") (pinfunction "VBAT_1") (pintype "power_in"))
    )
    (net (code "234") (name "VBUS") (class "Default")
      (node (ref "C1103") (pin "P$1") (pinfunction "1_P$1") (pintype "passive"))
      (node (ref "J301") (pin "VBUS") (pinfunction "1_VBUS") (pintype "power_in"))
      (node (ref "J302") (pin "1") (pinfunction "1_1") (pintype "passive"))
      (node (ref "R1112") (pin "P$1") (pinfunction "1_P$1") (pintype "passive"))
      (node (ref "U101") (pin "68") (pinfunction "PA9_68") (pintype "bidirectional"))
      (node (ref "U1101") (pin "P$19") (pinfunction "V3_P$19") (pintype "bidirectional"))
      (node (ref "U1104") (pin "P$7") (pinfunction "D_P$7") (pintype "passive"))
      (node (ref "U1104") (pin "P$8") (pinfunction "D_P$8") (pintype "passive"))
      (node (ref "U302") (pin "5") (pinfunction "VBUS_5") (pintype "bidirectional"))
      (node (ref "VBUS") (pin "P$1") (pinfunction "P$1_P$1") (pintype "passive"))
    )
    (net (code "235") (name "VDD_3V3_SENSORS") (class "Default")
      (node (ref "C501") (pin "P$1") (pinfunction "1_P$1") (pintype "passive"))
      (node (ref "C502") (pin "P$1") (pinfunction "1_P$1") (pintype "passive"))
      (node (ref "C503") (pin "P$1") (pinfunction "1_P$1") (pintype "passive"))
      (node (ref "C506") (pin "P$1") (pinfunction "1_P$1") (pintype "passive"))
      (node (ref "C507") (pin "P$1") (pinfunction "1_P$1") (pintype "passive"))
      (node (ref "C508") (pin "P$1") (pinfunction "1_P$1") (pintype "passive"))
      (node (ref "C511") (pin "P$1") (pinfunction "1_P$1") (pintype "passive"))
      (node (ref "C513") (pin "P$1") (pinfunction "1_P$1") (pintype "passive"))
      (node (ref "C514") (pin "P$1") (pinfunction "1_P$1") (pintype "passive"))
      (node (ref "C605") (pin "P$1") (pinfunction "1_P$1") (pintype "passive"))
      (node (ref "C617") (pin "P$1") (pinfunction "1_P$1") (pintype "passive"))
      (node (ref "Q601") (pin "E") (pinfunction "E_E") (pintype "passive"))
      (node (ref "U501") (pin "1") (pinfunction "VDD_IO_1") (pintype "bidirectional"))
      (node (ref "U501") (pin "15") (pinfunction "RES_P15_VDD_15") (pintype "bidirectional"))
      (node (ref "U501") (pin "16") (pinfunction "VDD_16") (pintype "bidirectional"))
      (node (ref "U502") (pin "1") (pinfunction "VDD_IO_1") (pintype "bidirectional"))
      (node (ref "U502") (pin "15") (pinfunction "VDD_15") (pintype "bidirectional"))
      (node (ref "U502") (pin "16") (pinfunction "VDD_16") (pintype "bidirectional"))
      (node (ref "U504") (pin "1") (pinfunction "VDD_IO_1") (pintype "bidirectional"))
      (node (ref "U504") (pin "14") (pinfunction "VDD_14") (pintype "bidirectional"))
      (node (ref "U505") (pin "13") (pinfunction "VDD_13") (pintype "bidirectional"))
      (node (ref "U506") (pin "1") (pinfunction "VDD_1") (pintype "bidirectional"))
      (node (ref "U603") (pin "8") (pinfunction "VOUT1_8") (pintype "bidirectional"))
      (node (ref "VDDA_3V1101") (pin "P$1") (pinfunction "P$1_P$1") (pintype "passive"))
      (node (ref "X503") (pin "1") (pinfunction "S_1") (pintype "passive"))
    )
    (net (code "236") (name "VDD_3V3_SENSORS_EN") (class "Default")
      (node (ref "R603") (pin "P$2") (pinfunction "2_P$2") (pintype "passive"))
      (node (ref "R620") (pin "P$2") (pinfunction "2_P$2") (pintype "passive"))
      (node (ref "R635") (pin "P$2") (pinfunction "2_P$2") (pintype "passive"))
      (node (ref "U101") (pin "2") (pinfunction "PE3_2") (pintype "bidirectional"))
      (node (ref "U603") (pin "5") (pinfunction "EN1_5") (pintype "bidirectional"))
    )
    (net (code "237") (name "VDD_3V3_SPEKTRUM") (class "Default")
      (node (ref "C1008") (pin "P$1") (pinfunction "1_P$1") (pintype "passive"))
      (node (ref "D801") (pin "C") (pinfunction "C_C") (pintype "passive"))
      (node (ref "J801") (pin "P$1") (pinfunction "P$1_P$1") (pintype "bidirectional"))
      (node (ref "U1002") (pin "8") (pinfunction "VOUT1_8") (pintype "bidirectional"))
    )
    (net (code "238") (name "VDD_3V3_SPEKTRUM_EN") (class "Default")
      (node (ref "R1002") (pin "P$2") (pinfunction "2_P$2") (pintype "passive"))
      (node (ref "U1002") (pin "5") (pinfunction "EN1_5") (pintype "bidirectional"))
      (node (ref "U801") (pin "2") (pinfunction "PC13_2") (pintype "bidirectional"))
    )
    (net (code "239") (name "VDD_5V_BRICK") (class "Default")
      (node (ref "C1101") (pin "P$1") (pinfunction "1_P$1") (pintype "passive"))
      (node (ref "J601") (pin "1") (pinfunction "1_1") (pintype "passive"))
      (node (ref "J601") (pin "2") (pinfunction "2_2") (pintype "passive"))
      (node (ref "R1105") (pin "P$1") (pinfunction "1_P$1") (pintype "passive"))
      (node (ref "U1101") (pin "P$21") (pinfunction "V1_P$21") (pintype "bidirectional"))
      (node (ref "U1102") (pin "P$7") (pinfunction "D_P$7") (pintype "passive"))
      (node (ref "U1102") (pin "P$8") (pinfunction "D_P$8") (pintype "passive"))
      (node (ref "VDD_5V_BRICK") (pin "P$1") (pinfunction "P$1_P$1") (pintype "passive"))
    )
    (net (code "240") (name "VDD_5V_HIPOWER") (class "Default")
      (node (ref "C614") (pin "P$1") (pinfunction "1_P$1") (pintype "passive"))
      (node (ref "L201") (pin "P$1") (pinfunction "P$1_P$1") (pintype "bidirectional"))
      (node (ref "U601") (pin "8") (pinfunction "OUT_8") (pintype "bidirectional"))
    )
    (net (code "241") (name "VDD_5V_IN") (class "Default")
      (node (ref "C1104") (pin "P$1") (pinfunction "1_P$1") (pintype "passive"))
      (node (ref "C702") (pin "P$1") (pinfunction "1_P$1") (pintype "passive"))
      (node (ref "D1001") (pin "1") (pinfunction "A1_1") (pintype "passive"))
      (node (ref "D1002") (pin "1") (pinfunction "A1_1") (pintype "passive"))
      (node (ref "L603") (pin "P$1") (pinfunction "P$1_P$1") (pintype "bidirectional"))
      (node (ref "L701") (pin "P$1") (pinfunction "1_P$1") (pintype "passive"))
      (node (ref "LED701") (pin "A") (pinfunction "A_A") (pintype "passive"))
      (node (ref "LED704") (pin "A") (pinfunction "A_A") (pintype "passive"))
      (node (ref "R609") (pin "P$2") (pinfunction "2_P$2") (pintype "passive"))
      (node (ref "RN1101") (pin "5") (pinfunction "2_5") (pintype "passive"))
      (node (ref "RN1101") (pin "6") (pinfunction "2_6") (pintype "passive"))
      (node (ref "RN1101") (pin "7") (pinfunction "2_7") (pintype "passive"))
      (node (ref "U1101") (pin "P$12") (pinfunction "VOUT_P$12") (pintype "bidirectional"))
      (node (ref "U1102") (pin "P$5") (pinfunction "D_P$5") (pintype "passive"))
      (node (ref "U1102") (pin "P$6") (pinfunction "D_P$6") (pintype "passive"))
      (node (ref "U1103") (pin "P$5") (pinfunction "D_P$5") (pintype "passive"))
      (node (ref "U1103") (pin "P$6") (pinfunction "D_P$6") (pintype "passive"))
      (node (ref "U1104") (pin "P$5") (pinfunction "D_P$5") (pintype "passive"))
      (node (ref "U1104") (pin "P$6") (pinfunction "D_P$6") (pintype "passive"))
      (node (ref "U601") (pin "1") (pinfunction "IN_1") (pintype "bidirectional"))
      (node (ref "U602") (pin "1") (pinfunction "IN_1") (pintype "bidirectional"))
      (node (ref "U702") (pin "3") (pinfunction "VIN_3") (pintype "power_in"))
      (node (ref "U703") (pin "A1") (pinfunction "A_A1") (pintype "passive"))
      (node (ref "U703") (pin "A2") (pinfunction "A_A2") (pintype "passive"))
      (node (ref "U703") (pin "A3") (pinfunction "A_A3") (pintype "passive"))
      (node (ref "VDD_5V_IN") (pin "P$1") (pinfunction "P$1_P$1") (pintype "passive"))
    )
    (net (code "242") (name "VDD_5V_PERIPH") (class "Default")
      (node (ref "C618") (pin "P$1") (pinfunction "1_P$1") (pintype "passive"))
      (node (ref "L202") (pin "P$1") (pinfunction "P$1_P$1") (pintype "bidirectional"))
      (node (ref "L203") (pin "P$1") (pinfunction "P$1_P$1") (pintype "bidirectional"))
      (node (ref "L401") (pin "P$1") (pinfunction "P$1_P$1") (pintype "bidirectional"))
      (node (ref "L402") (pin "P$1") (pinfunction "P$1_P$1") (pintype "bidirectional"))
      (node (ref "L403") (pin "P$1") (pinfunction "P$1_P$1") (pintype "bidirectional"))
      (node (ref "L404") (pin "P$1") (pinfunction "P$1_P$1") (pintype "bidirectional"))
      (node (ref "U602") (pin "8") (pinfunction "OUT_8") (pintype "bidirectional"))
    )
    (net (code "243") (name "VDD_5V_SENS") (class "Default")
      (node (ref "R609") (pin "P$1") (pinfunction "1_P$1") (pintype "passive"))
      (node (ref "R610") (pin "P$1") (pinfunction "1_P$1") (pintype "passive"))
      (node (ref "U101") (pin "29") (pinfunction "PA4_29") (pintype "bidirectional"))
    )
    (net (code "244") (name "VDD_SERVO") (class "Default")
      (node (ref "C1102") (pin "P$1") (pinfunction "1_P$1") (pintype "passive"))
      (node (ref "D904") (pin "ANODE") (pinfunction "A_ANODE") (pintype "passive"))
      (node (ref "J901") (pin "11") (pinfunction "S_11") (pintype "passive"))
      (node (ref "J901") (pin "14") (pinfunction "S_14") (pintype "passive"))
      (node (ref "J901") (pin "17") (pinfunction "S_17") (pintype "passive"))
      (node (ref "J901") (pin "20") (pinfunction "S_20") (pintype "passive"))
      (node (ref "J901") (pin "23") (pinfunction "S_23") (pintype "passive"))
      (node (ref "J901") (pin "26") (pinfunction "S_26") (pintype "passive"))
      (node (ref "J901") (pin "29") (pinfunction "S_29") (pintype "passive"))
      (node (ref "J901") (pin "32") (pinfunction "S_32") (pintype "passive"))
      (node (ref "J901") (pin "35") (pinfunction "S_35") (pintype "passive"))
      (node (ref "J901") (pin "38") (pinfunction "S_38") (pintype "passive"))
      (node (ref "J901") (pin "41") (pinfunction "S_41") (pintype "passive"))
      (node (ref "J901") (pin "44") (pinfunction "S_44") (pintype "passive"))
      (node (ref "J901") (pin "47") (pinfunction "S_47") (pintype "passive"))
      (node (ref "J901") (pin "5") (pinfunction "S_5") (pintype "passive"))
      (node (ref "J901") (pin "8") (pinfunction "S_8") (pintype "passive"))
      (node (ref "R1109") (pin "P$1") (pinfunction "1_P$1") (pintype "passive"))
      (node (ref "R922") (pin "P$2") (pinfunction "2_P$2") (pintype "passive"))
      (node (ref "U1101") (pin "P$20") (pinfunction "V2_P$20") (pintype "bidirectional"))
      (node (ref "U1103") (pin "P$7") (pinfunction "D_P$7") (pintype "passive"))
      (node (ref "U1103") (pin "P$8") (pinfunction "D_P$8") (pintype "passive"))
      (node (ref "VDD_SERVO") (pin "P$1") (pinfunction "P$1_P$1") (pintype "passive"))
    )
    (net (code "245") (name "VDD_SERVO_IN") (class "Default")
      (node (ref "L901") (pin "P$2") (pinfunction "P$2_P$2") (pintype "bidirectional"))
      (node (ref "U1001") (pin "1") (pinfunction "IN_1") (pintype "bidirectional"))
    )
    (net (code "246") (name "VDD_SERVO_SENS") (class "Default")
      (node (ref "R918") (pin "P$1") (pinfunction "1_P$1") (pintype "passive"))
      (node (ref "R919") (pin "P$2") (pinfunction "2_P$2") (pintype "passive"))
      (node (ref "U801") (pin "14") (pinfunction "PA4_14") (pintype "bidirectional"))
    )
    (net (code "247") (name "unconnected-(J301-4-PadID)") (class "Default")
      (node (ref "J301") (pin "ID") (pinfunction "4_ID") (pintype "passive"))
    )
    (net (code "248") (name "unconnected-(JX301A-S-Pad10)") (class "Default")
      (node (ref "JX301") (pin "10") (pinfunction "S_10") (pintype "passive"))
    )
    (net (code "249") (name "unconnected-(JX301F-S-Pad8)") (class "Default")
      (node (ref "JX301") (pin "8") (pinfunction "S_8") (pintype "passive"))
    )
    (net (code "250") (name "unconnected-(JX802A-S-Pad10)") (class "Default")
      (node (ref "JX802") (pin "10") (pinfunction "S_10") (pintype "passive"))
    )
    (net (code "251") (name "unconnected-(JX802F-S-Pad8)") (class "Default")
      (node (ref "JX802") (pin "8") (pinfunction "S_8") (pintype "passive"))
    )
    (net (code "252") (name "unconnected-(U101I-PC1-Pad16)") (class "Default")
      (node (ref "U101") (pin "16") (pinfunction "PC1_16") (pintype "bidirectional"))
    )
    (net (code "253") (name "unconnected-(U202-A1-Pad1)") (class "Default")
      (node (ref "U202") (pin "1") (pinfunction "A1_1") (pintype "bidirectional"))
    )
    (net (code "254") (name "unconnected-(U202-A2-Pad3)") (class "Default")
      (node (ref "U202") (pin "3") (pinfunction "A2_3") (pintype "bidirectional"))
    )
    (net (code "255") (name "unconnected-(U202-B1-Pad20)") (class "Default")
      (node (ref "U202") (pin "20") (pinfunction "B1_20") (pintype "bidirectional"))
    )
    (net (code "256") (name "unconnected-(U202-B2-Pad18)") (class "Default")
      (node (ref "U202") (pin "18") (pinfunction "B2_18") (pintype "bidirectional"))
    )
    (net (code "257") (name "unconnected-(U501-INT1-Pad7)") (class "Default")
      (node (ref "U501") (pin "7") (pinfunction "INT1_7") (pintype "output"))
    )
    (net (code "258") (name "unconnected-(U502-DEN-Pad8)") (class "Default")
      (node (ref "U502") (pin "8") (pinfunction "DEN_8") (pintype "bidirectional"))
    )
    (net (code "259") (name "unconnected-(U502-INT1-Pad7)") (class "Default")
      (node (ref "U502") (pin "7") (pinfunction "INT1_7") (pintype "bidirectional"))
    )
    (net (code "260") (name "unconnected-(U505-AUX_CL-Pad7)") (class "Default")
      (node (ref "U505") (pin "7") (pinfunction "AUX_CL_7") (pintype "bidirectional"))
    )
    (net (code "261") (name "unconnected-(U505-AUX_DA-Pad6)") (class "Default")
      (node (ref "U505") (pin "6") (pinfunction "AUX_DA_6") (pintype "bidirectional"))
    )
    (net (code "262") (name "unconnected-(U505-CLKOUT-Pad22)") (class "Default")
      (node (ref "U505") (pin "22") (pinfunction "CLKOUT_22") (pintype "bidirectional"))
    )
    (net (code "263") (name "unconnected-(U505-FSYNC-Pad11)") (class "Default")
      (node (ref "U505") (pin "11") (pinfunction "FSYNC_11") (pintype "bidirectional"))
    )
    (net (code "264") (name "unconnected-(U505-NC1-Pad2)") (class "Default")
      (node (ref "U505") (pin "2") (pinfunction "NC1_2") (pintype "bidirectional"))
    )
    (net (code "265") (name "unconnected-(U505-NC2-Pad3)") (class "Default")
      (node (ref "U505") (pin "3") (pinfunction "NC2_3") (pintype "bidirectional"))
    )
    (net (code "266") (name "unconnected-(U505-NC3-Pad4)") (class "Default")
      (node (ref "U505") (pin "4") (pinfunction "NC3_4") (pintype "bidirectional"))
    )
    (net (code "267") (name "unconnected-(U505-NC4-Pad5)") (class "Default")
      (node (ref "U505") (pin "5") (pinfunction "NC4_5") (pintype "bidirectional"))
    )
    (net (code "268") (name "unconnected-(U505-NC5-Pad14)") (class "Default")
      (node (ref "U505") (pin "14") (pinfunction "NC5_14") (pintype "bidirectional"))
    )
    (net (code "269") (name "unconnected-(U505-NC6-Pad15)") (class "Default")
      (node (ref "U505") (pin "15") (pinfunction "NC6_15") (pintype "bidirectional"))
    )
    (net (code "270") (name "unconnected-(U505-NC7-Pad16)") (class "Default")
      (node (ref "U505") (pin "16") (pinfunction "NC7_16") (pintype "bidirectional"))
    )
    (net (code "271") (name "unconnected-(U505-NC8-Pad17)") (class "Default")
      (node (ref "U505") (pin "17") (pinfunction "NC8_17") (pintype "bidirectional"))
    )
    (net (code "272") (name "unconnected-(U505-RESV1-Pad19)") (class "Default")
      (node (ref "U505") (pin "19") (pinfunction "RESV1_19") (pintype "bidirectional"))
    )
    (net (code "273") (name "unconnected-(U505-RESV2-Pad21)") (class "Default")
      (node (ref "U505") (pin "21") (pinfunction "RESV2_21") (pintype "bidirectional"))
    )
    (net (code "274") (name "unconnected-(U506-CSB1-Pad4)") (class "Default")
      (node (ref "U506") (pin "4") (pinfunction "CSB1_4") (pintype "bidirectional"))
    )
    (net (code "275") (name "unconnected-(U801B-PA11-Pad32)") (class "Default")
      (node (ref "U801") (pin "32") (pinfunction "PA11_32") (pintype "bidirectional"))
    )
    (net (code "276") (name "unconnected-(U801D-PB12-Pad25)") (class "Default")
      (node (ref "U801") (pin "25") (pinfunction "PB12_25") (pintype "bidirectional"))
    )
    (net (code "277") (name "unconnected-(U801E-PB6-Pad42)") (class "Default")
      (node (ref "U801") (pin "42") (pinfunction "PB6_42") (pintype "bidirectional"))
    )
    (net (code "278") (name "unconnected-(U801E-PB7-Pad43)") (class "Default")
      (node (ref "U801") (pin "43") (pinfunction "PB7_43") (pintype "bidirectional"))
    )
    (net (code "279") (name "unconnected-(U801F-PC14-Pad3)") (class "Default")
      (node (ref "U801") (pin "3") (pinfunction "PC14_3") (pintype "bidirectional"))
    )
    (net (code "280") (name "unconnected-(U801F-PC15-Pad4)") (class "Default")
      (node (ref "U801") (pin "4") (pinfunction "PC15_4") (pintype "bidirectional"))
    )
    (net (code "281") (name "unconnected-(U901-A7-Pad8)") (class "Default")
      (node (ref "U901") (pin "8") (pinfunction "A7_8") (pintype "bidirectional"))
    )
    (net (code "282") (name "unconnected-(U901-A8-Pad9)") (class "Default")
      (node (ref "U901") (pin "9") (pinfunction "A8_9") (pintype "bidirectional"))
    )
    (net (code "283") (name "unconnected-(U901-B7-Pad13)") (class "Default")
      (node (ref "U901") (pin "13") (pinfunction "B7_13") (pintype "bidirectional"))
    )
    (net (code "284") (name "unconnected-(U901-B8-Pad12)") (class "Default")
      (node (ref "U901") (pin "12") (pinfunction "B8_12") (pintype "bidirectional"))
    )
    (net (code "285") (name "unconnected-(U1101-CAS-PadP$11)") (class "Default")
      (node (ref "U1101") (pin "P$11") (pinfunction "CAS_P$11") (pintype "bidirectional"))
    )
    (net (code "286") (name "unconnected-(U1101-EN-PadP$22)") (class "Default")
      (node (ref "U1101") (pin "P$22") (pinfunction "EN_P$22") (pintype "bidirectional"))
    )
    (net (code "287") (name "unconnected-(U1101-~{SHDN}-PadP$23)") (class "Default")
      (node (ref "U1101") (pin "P$23") (pinfunction "~{SHDN}_P$23") (pintype "bidirectional"))
    )
    (net (code "288") (name "~{ACCEL_MAG_CS}") (class "Default")
      (node (ref "U101") (pin "9") (pinfunction "PC15_9") (pintype "bidirectional"))
      (node (ref "U504") (pin "8") (pinfunction "CS_8") (pintype "bidirectional"))
      (node (ref "X503") (pin "6") (pinfunction "S_6") (pintype "passive"))
    )
    (net (code "289") (name "~{BARO_CS}") (class "Default")
      (node (ref "U101") (pin "88") (pinfunction "PD7_88") (pintype "bidirectional"))
      (node (ref "U506") (pin "5") (pinfunction "CSB2_5") (pintype "bidirectional"))
    )
    (net (code "290") (name "~{FMU-LED_AMBER}") (class "Default")
      (node (ref "R707") (pin "P$1") (pinfunction "1_P$1") (pintype "passive"))
      (node (ref "U101") (pin "43") (pinfunction "PE12_43") (pintype "bidirectional"))
    )
    (net (code "291") (name "~{FRAM_CS}") (class "Default")
      (node (ref "U101") (pin "57") (pinfunction "PD10_57") (pintype "bidirectional"))
      (node (ref "U102") (pin "1") (pinfunction "~{S}_1") (pintype "bidirectional"))
    )
    (net (code "292") (name "~{GYRO_CS}") (class "Default")
      (node (ref "U101") (pin "7") (pinfunction "PC13_7") (pintype "bidirectional"))
      (node (ref "U501") (pin "5") (pinfunction "CS_5") (pintype "input"))
      (node (ref "U502") (pin "5") (pinfunction "CS_5") (pintype "bidirectional"))
      (node (ref "X503") (pin "7") (pinfunction "S_7") (pintype "passive"))
    )
    (net (code "293") (name "~{IO-LED_AMBER}") (class "Default")
      (node (ref "R709") (pin "P$1") (pinfunction "1_P$1") (pintype "passive"))
      (node (ref "U801") (pin "28") (pinfunction "PB15_28") (pintype "bidirectional"))
    )
    (net (code "294") (name "~{IO-LED_BLUE}") (class "Default")
      (node (ref "R712") (pin "P$1") (pinfunction "1_P$1") (pintype "passive"))
      (node (ref "U801") (pin "27") (pinfunction "PB14_27") (pintype "bidirectional"))
    )
    (net (code "295") (name "~{IO-LED_SAFETY}") (class "Default")
      (node (ref "R710") (pin "P$2") (pinfunction "2_P$2") (pintype "passive"))
      (node (ref "U801") (pin "26") (pinfunction "PB13_26") (pintype "bidirectional"))
    )
    (net (code "296") (name "~{MPU_CS}") (class "Default")
      (node (ref "U101") (pin "17") (pinfunction "PC2_17") (pintype "bidirectional"))
      (node (ref "U505") (pin "8") (pinfunction "/CS_8") (pintype "bidirectional"))
    )
    (net (code "297") (name "~{SBUS_OUTPUT_EN}") (class "Default")
      (node (ref "U801") (pin "40") (pinfunction "PB4_40") (pintype "bidirectional"))
      (node (ref "U903") (pin "7") (pinfunction "~{2OE}_7") (pintype "input"))
    )
    (net (code "298") (name "~{SPI_EXT_NSS}") (class "Default")
      (node (ref "J403") (pin "5") (pinfunction "5_5") (pintype "passive"))
      (node (ref "U101") (pin "3") (pinfunction "PE4_3") (pintype "bidirectional"))
    )
    (net (code "299") (name "~{VBUS_VALID}") (class "Default")
      (node (ref "!VBUS_VALID") (pin "P$1") (pinfunction "P$1_P$1") (pintype "passive"))
      (node (ref "RN1101") (pin "2") (pinfunction "1_2") (pintype "passive"))
      (node (ref "U101") (pin "15") (pinfunction "PC0_15") (pintype "bidirectional"))
      (node (ref "U1101") (pin "P$9") (pinfunction "~{VALID3}_P$9") (pintype "bidirectional"))
    )
    (net (code "300") (name "~{VDD_5V_HIPOWER_OC}") (class "Default")
      (node (ref "R602") (pin "P$1") (pinfunction "1_P$1") (pintype "passive"))
      (node (ref "U101") (pin "41") (pinfunction "PE10_41") (pintype "bidirectional"))
      (node (ref "U601") (pin "4") (pinfunction "~{FAULT}_4") (pintype "bidirectional"))
    )
    (net (code "301") (name "~{VDD_5V_PERIPH_EN}") (class "Default")
      (node (ref "R615") (pin "P$1") (pinfunction "1_P$1") (pintype "passive"))
      (node (ref "U101") (pin "67") (pinfunction "PA8_67") (pintype "bidirectional"))
      (node (ref "U601") (pin "5") (pinfunction "~{CE}_5") (pintype "bidirectional"))
      (node (ref "U602") (pin "5") (pinfunction "~{CE}_5") (pintype "bidirectional"))
    )
    (net (code "302") (name "~{VDD_5V_PERIPH_OC}") (class "Default")
      (node (ref "R604") (pin "P$1") (pinfunction "1_P$1") (pintype "passive"))
      (node (ref "U101") (pin "46") (pinfunction "PE15_46") (pintype "bidirectional"))
      (node (ref "U602") (pin "4") (pinfunction "~{FAULT}_4") (pintype "bidirectional"))
    )
    (net (code "303") (name "~{VDD_BRICK_VALID}") (class "Default")
      (node (ref "!VDD_BRICK_VALID") (pin "P$1") (pinfunction "P$1_P$1") (pintype "passive"))
      (node (ref "RN1101") (pin "4") (pinfunction "1_4") (pintype "passive"))
      (node (ref "U101") (pin "91") (pinfunction "PB5_91") (pintype "bidirectional"))
      (node (ref "U1101") (pin "P$7") (pinfunction "~{VALID1}_P$7") (pintype "bidirectional"))
    )
    (net (code "304") (name "~{VDD_SERVO_VALID}") (class "Default")
      (node (ref "!VDD_SERVO_VALID") (pin "P$1") (pinfunction "P$1_P$1") (pintype "passive"))
      (node (ref "RN1101") (pin "3") (pinfunction "1_3") (pintype "passive"))
      (node (ref "U101") (pin "93") (pinfunction "PB7_93") (pintype "bidirectional"))
      (node (ref "U1101") (pin "P$8") (pinfunction "~{VALID2}_P$8") (pintype "bidirectional"))
    )
  )
)
